# BeagleBone_Blue_3D.net
KiCad netlist of a schematic drawn in EAGLE
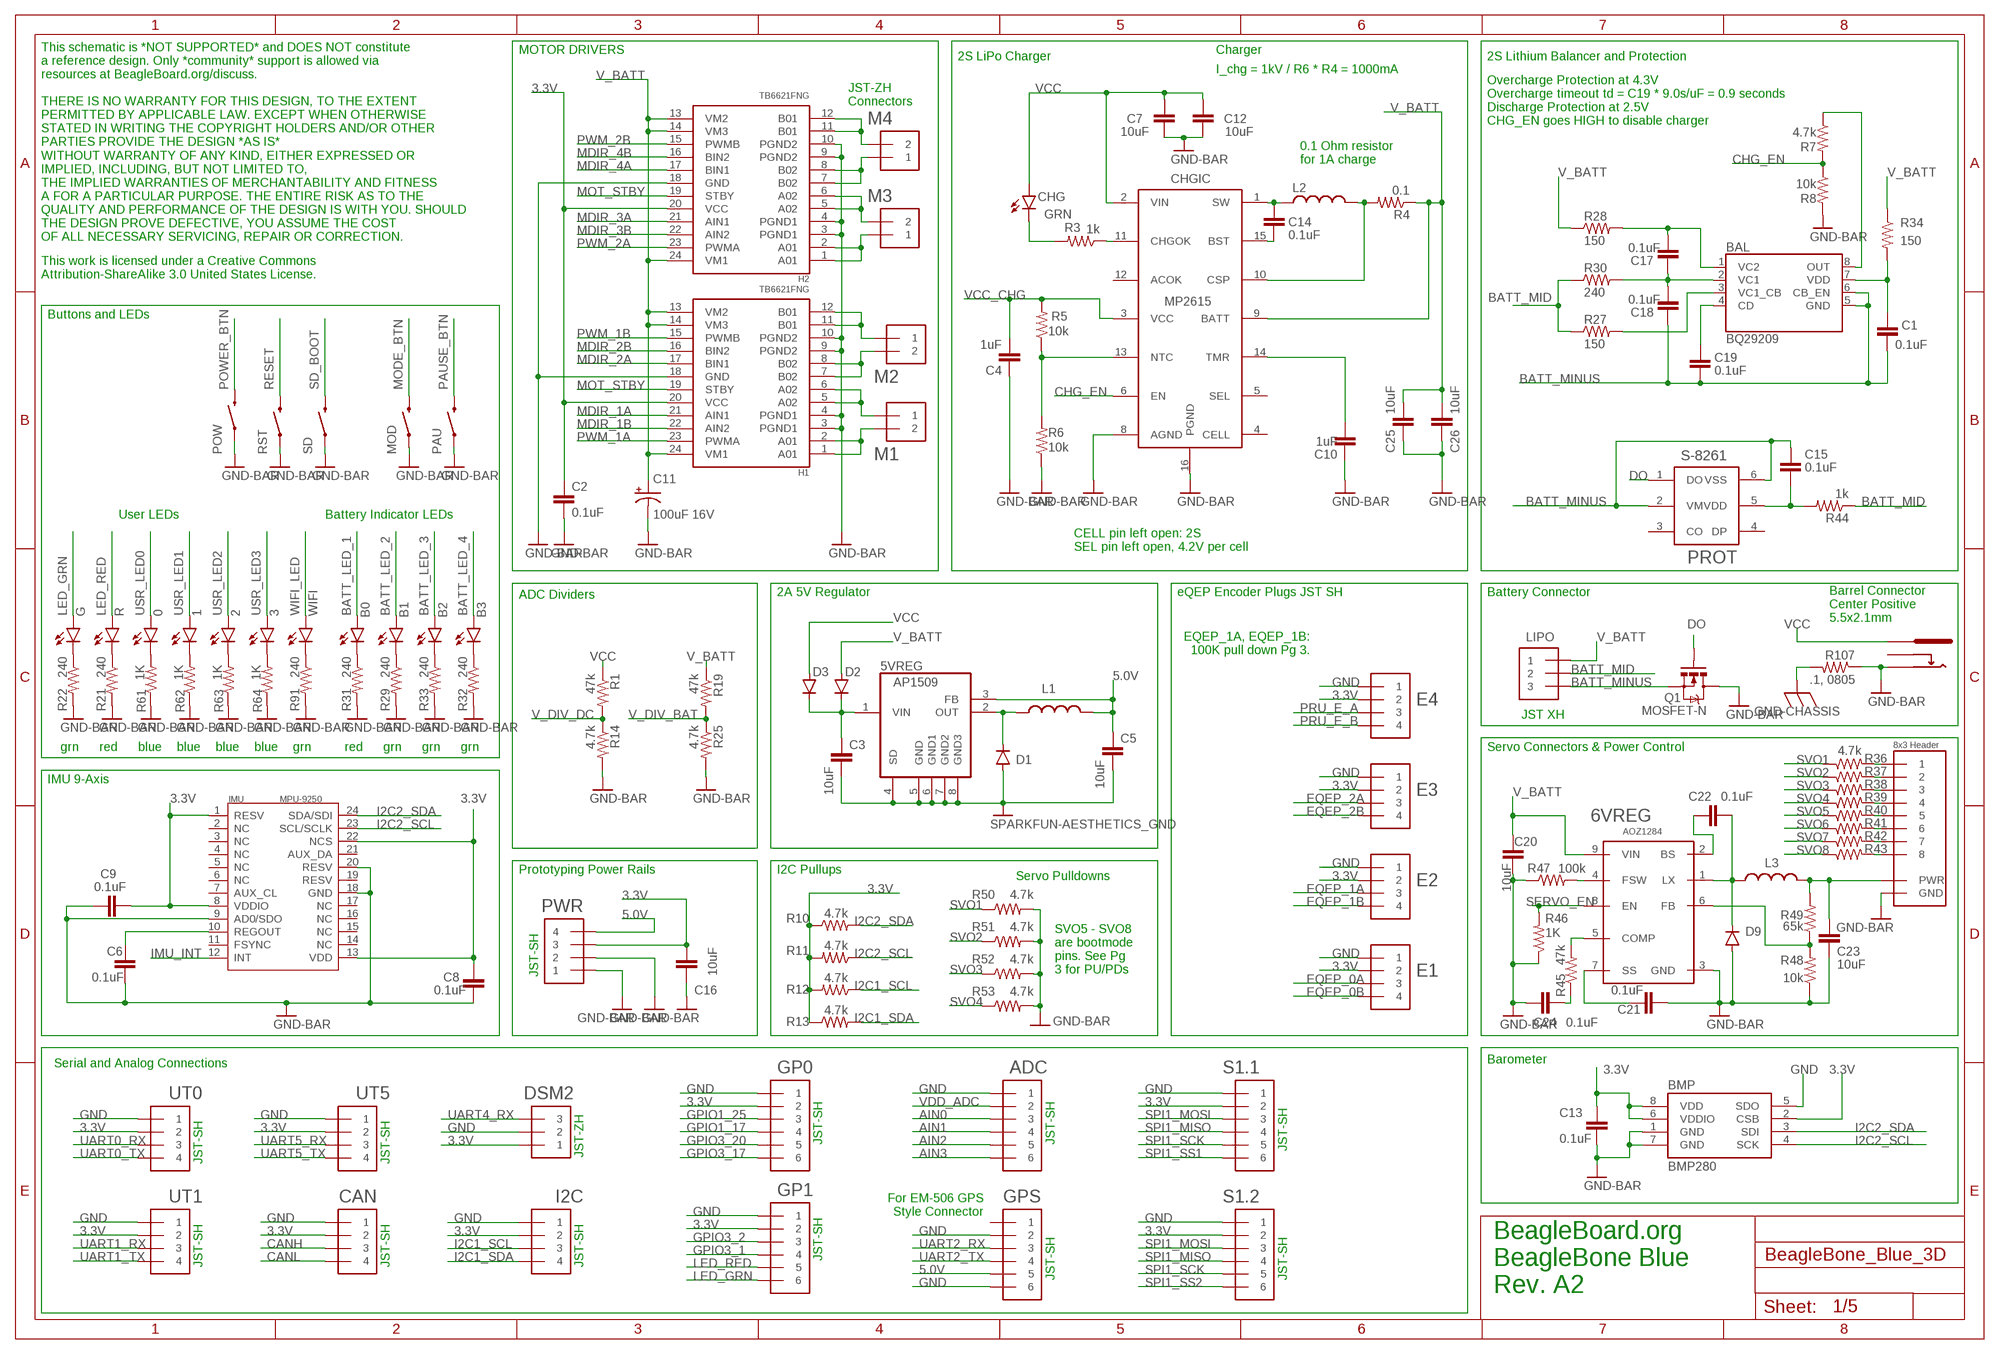
[diagram p0: schematic, sheet 1]
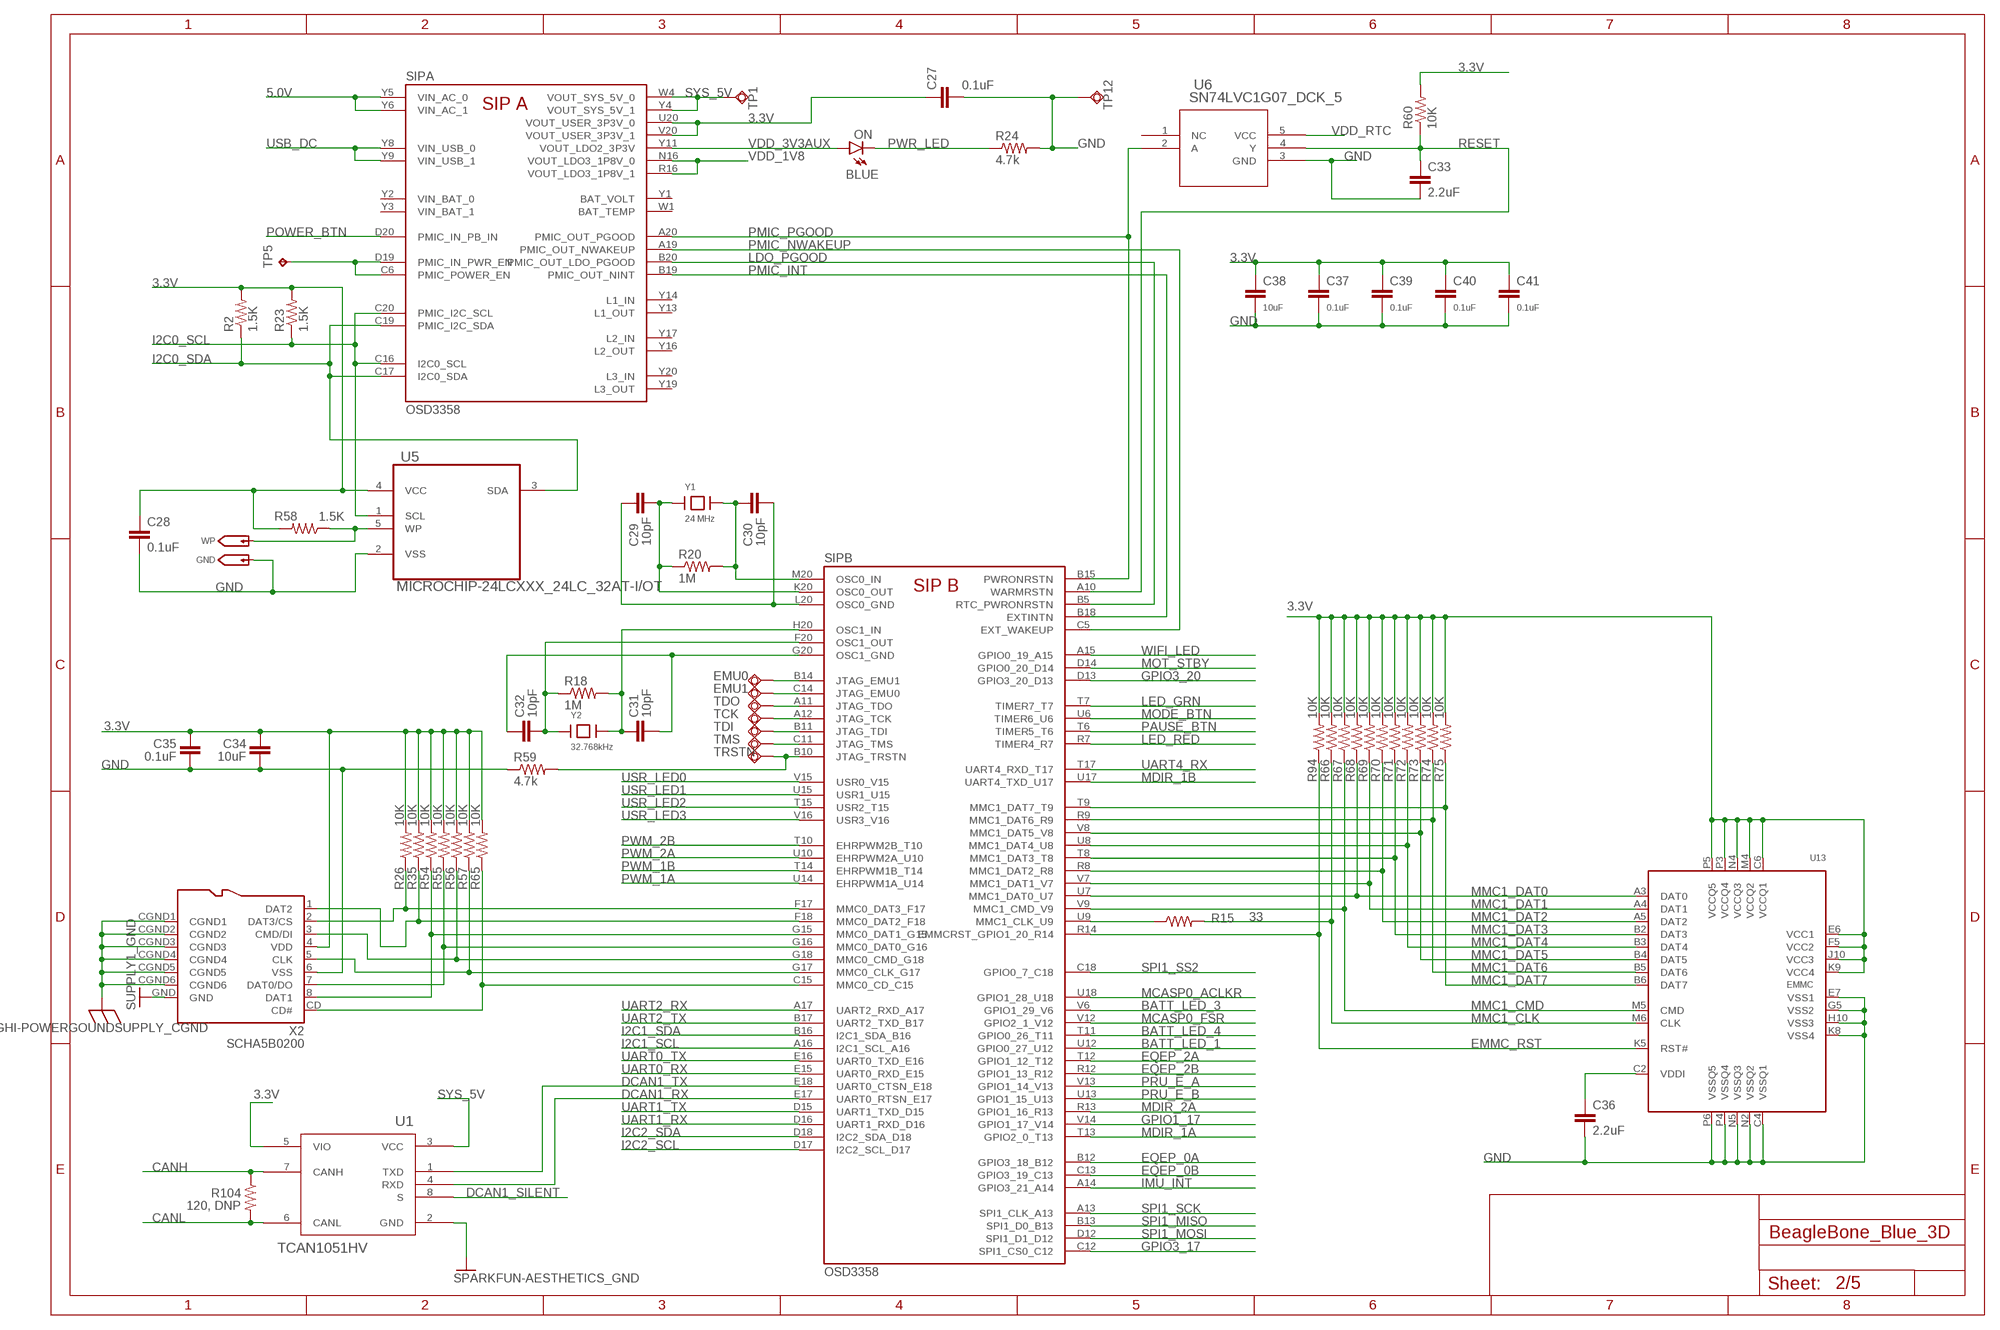
[diagram p1: schematic, sheet 2]
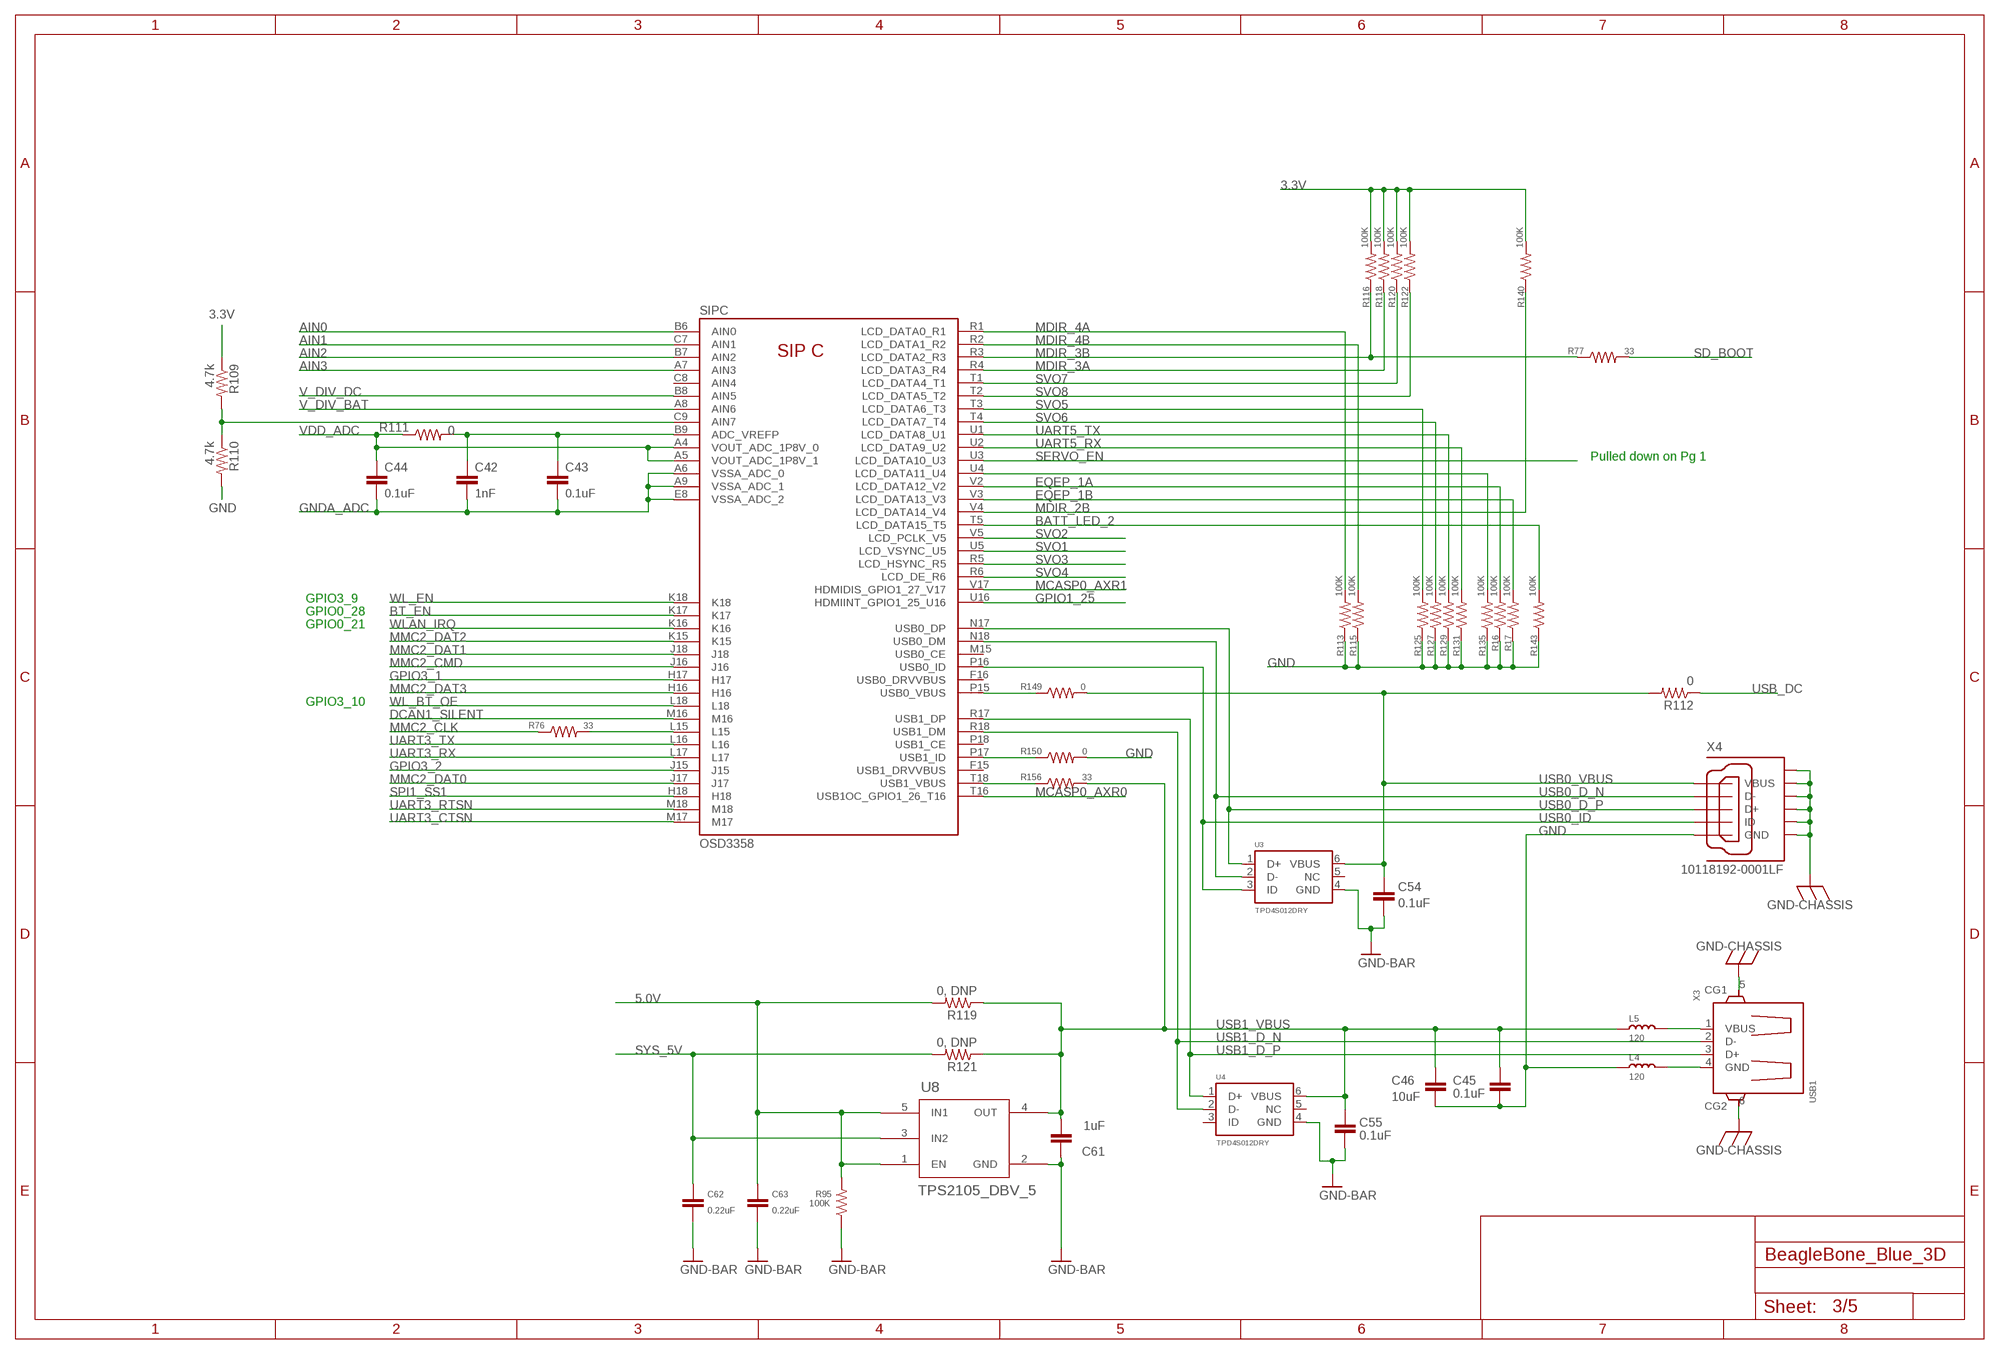
[diagram p2: schematic, sheet 3]
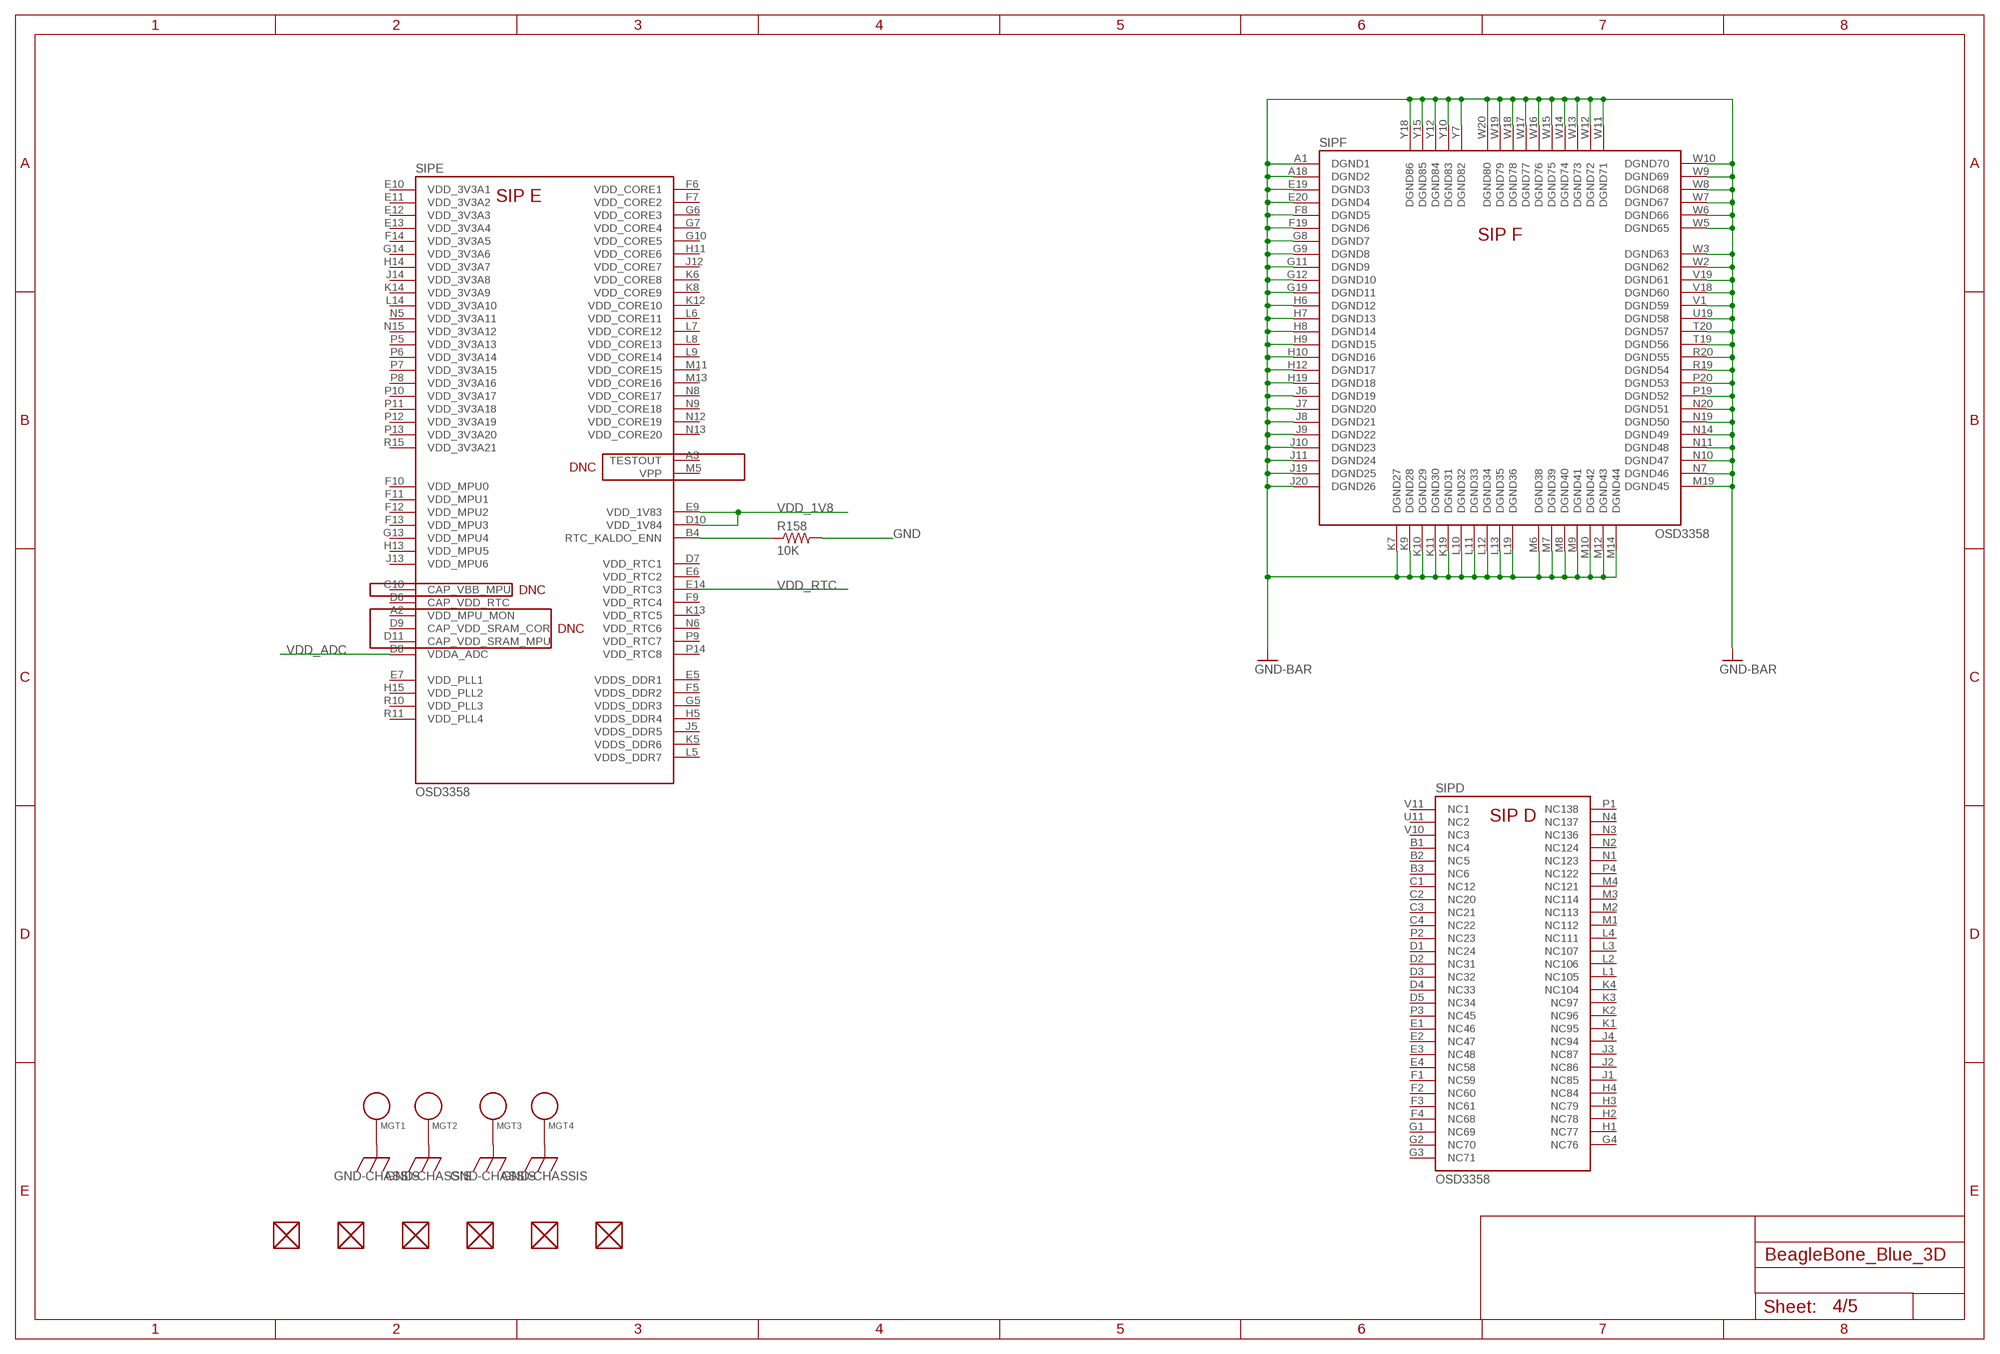
[diagram p3: schematic, sheet 4]
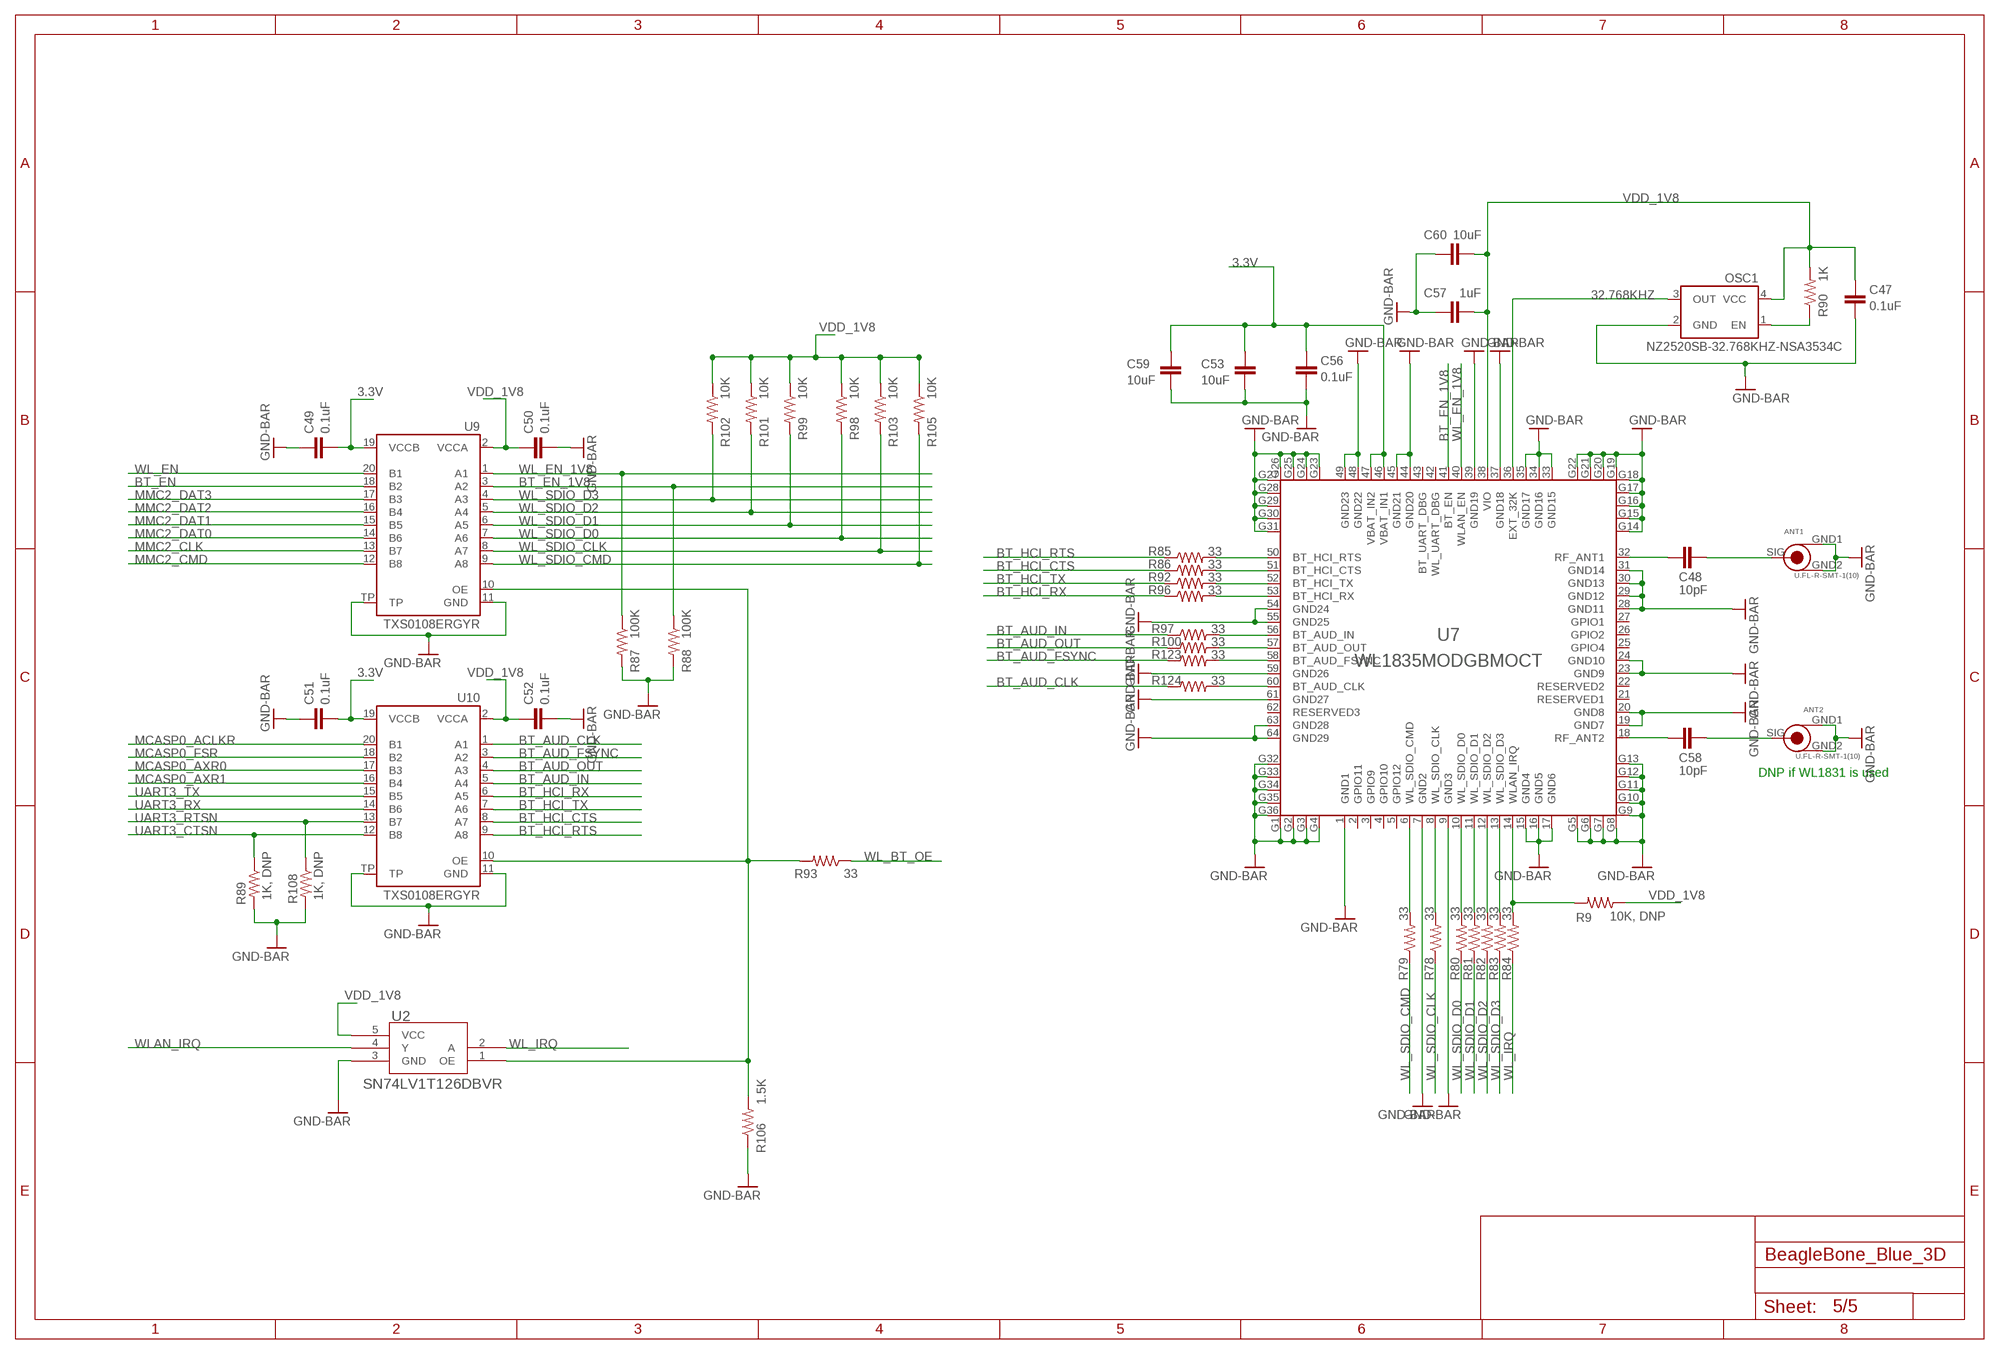
[diagram p4: schematic, sheet 5]

(export (version "E")
  (design (tool "Eeschema 10.0.6"))
  (components
    (comp (ref "ANT1")
      (value "U.FL-R-SMT-1(10)")
      (footprint "eagle-import:GHI-CONNECTORS_U.FL-R-SMT-1")
      (libsource (lib "eagle-import") (part "U.FL-R-SMT-1"))
    )
    (comp (ref "ANT2")
      (value "U.FL-R-SMT-1(10)")
      (footprint "eagle-import:GHI-CONNECTORS_U.FL-R-SMT-1")
      (libsource (lib "eagle-import") (part "U.FL-R-SMT-1"))
    )
    (comp (ref "C47")
      (value "0.1uF")
      (footprint "eagle-import:0402-CAP")
      (libsource (lib "eagle-import") (part "CAPACITOR-N0402"))
    )
    (comp (ref "C48")
      (value "10pF")
      (footprint "eagle-import:0402-CAP")
      (libsource (lib "eagle-import") (part "CAPACITOR-N0402"))
    )
    (comp (ref "C49")
      (value "0.1uF")
      (footprint "eagle-import:0402-CAP")
      (libsource (lib "eagle-import") (part "CAPACITOR-N0402"))
    )
    (comp (ref "C50")
      (value "0.1uF")
      (footprint "eagle-import:0402-CAP")
      (libsource (lib "eagle-import") (part "CAPACITOR-N0402"))
    )
    (comp (ref "C51")
      (value "0.1uF")
      (footprint "eagle-import:0402-CAP")
      (libsource (lib "eagle-import") (part "CAPACITOR-N0402"))
    )
    (comp (ref "C52")
      (value "0.1uF")
      (footprint "eagle-import:0402-CAP")
      (libsource (lib "eagle-import") (part "CAPACITOR-N0402"))
    )
    (comp (ref "C53")
      (value "10uF")
      (footprint "eagle-import:0805")
      (libsource (lib "eagle-import") (part "CAPACITOR-N0805"))
    )
    (comp (ref "C56")
      (value "0.1uF")
      (footprint "eagle-import:0402-CAP")
      (libsource (lib "eagle-import") (part "CAPACITOR-N0402"))
    )
    (comp (ref "C57")
      (value "1uF")
      (footprint "eagle-import:0402-CAP")
      (libsource (lib "eagle-import") (part "CAPACITOR-N0402"))
    )
    (comp (ref "C58")
      (value "10pF")
      (footprint "eagle-import:0402-CAP")
      (libsource (lib "eagle-import") (part "CAPACITOR-N0402"))
    )
    (comp (ref "C59")
      (value "10uF")
      (footprint "eagle-import:0805")
      (libsource (lib "eagle-import") (part "CAPACITOR-N0805"))
    )
    (comp (ref "C60")
      (value "10uF")
      (footprint "eagle-import:0805")
      (libsource (lib "eagle-import") (part "CAPACITOR-N0805"))
    )
    (comp (ref "OSC1")
      (value "NZ2520SB-32.768KHZ-NSA3534C")
      (footprint "eagle-import:NZ2520S")
      (libsource (lib "eagle-import") (part "OSCILLATOR"))
    )
    (comp (ref "R9")
      (value "10K, DNP")
      (footprint "eagle-import:0402-RES")
      (libsource (lib "eagle-import") (part "RESISTOR0402"))
    )
    (comp (ref "R78")
      (value "33")
      (footprint "eagle-import:0402-RES")
      (libsource (lib "eagle-import") (part "RESISTOR0402"))
    )
    (comp (ref "R79")
      (value "33")
      (footprint "eagle-import:0402-RES")
      (libsource (lib "eagle-import") (part "RESISTOR0402"))
    )
    (comp (ref "R80")
      (value "33")
      (footprint "eagle-import:0402-RES")
      (libsource (lib "eagle-import") (part "RESISTOR0402"))
    )
    (comp (ref "R81")
      (value "33")
      (footprint "eagle-import:0402-RES")
      (libsource (lib "eagle-import") (part "RESISTOR0402"))
    )
    (comp (ref "R82")
      (value "33")
      (footprint "eagle-import:0402-RES")
      (libsource (lib "eagle-import") (part "RESISTOR0402"))
    )
    (comp (ref "R83")
      (value "33")
      (footprint "eagle-import:0402-RES")
      (libsource (lib "eagle-import") (part "RESISTOR0402"))
    )
    (comp (ref "R84")
      (value "33")
      (footprint "eagle-import:0402-RES")
      (libsource (lib "eagle-import") (part "RESISTOR0402"))
    )
    (comp (ref "R85")
      (value "33")
      (footprint "eagle-import:0402-RES")
      (libsource (lib "eagle-import") (part "RESISTOR0402"))
    )
    (comp (ref "R86")
      (value "33")
      (footprint "eagle-import:0402-RES")
      (libsource (lib "eagle-import") (part "RESISTOR0402"))
    )
    (comp (ref "R87")
      (value "100K")
      (footprint "eagle-import:0402-RES")
      (libsource (lib "eagle-import") (part "RESISTOR0402"))
    )
    (comp (ref "R88")
      (value "100K")
      (footprint "eagle-import:0402-RES")
      (libsource (lib "eagle-import") (part "RESISTOR0402"))
    )
    (comp (ref "R89")
      (value "1K, DNP")
      (footprint "eagle-import:0402-RES")
      (libsource (lib "eagle-import") (part "RESISTOR0402"))
    )
    (comp (ref "R90")
      (value "1K")
      (footprint "eagle-import:0402-RES")
      (libsource (lib "eagle-import") (part "RESISTOR0402"))
    )
    (comp (ref "R92")
      (value "33")
      (footprint "eagle-import:0402-RES")
      (libsource (lib "eagle-import") (part "RESISTOR0402"))
    )
    (comp (ref "R93")
      (value "33")
      (footprint "eagle-import:0402-RES")
      (libsource (lib "eagle-import") (part "RESISTOR0402"))
    )
    (comp (ref "R96")
      (value "33")
      (footprint "eagle-import:0402-RES")
      (libsource (lib "eagle-import") (part "RESISTOR0402"))
    )
    (comp (ref "R97")
      (value "33")
      (footprint "eagle-import:0402-RES")
      (libsource (lib "eagle-import") (part "RESISTOR0402"))
    )
    (comp (ref "R98")
      (value "10K")
      (footprint "eagle-import:0402-RES")
      (libsource (lib "eagle-import") (part "RESISTOR0402"))
    )
    (comp (ref "R99")
      (value "10K")
      (footprint "eagle-import:0402-RES")
      (libsource (lib "eagle-import") (part "RESISTOR0402"))
    )
    (comp (ref "R100")
      (value "33")
      (footprint "eagle-import:0402-RES")
      (libsource (lib "eagle-import") (part "RESISTOR0402"))
    )
    (comp (ref "R101")
      (value "10K")
      (footprint "eagle-import:0402-RES")
      (libsource (lib "eagle-import") (part "RESISTOR0402"))
    )
    (comp (ref "R102")
      (value "10K")
      (footprint "eagle-import:0402-RES")
      (libsource (lib "eagle-import") (part "RESISTOR0402"))
    )
    (comp (ref "R103")
      (value "10K")
      (footprint "eagle-import:0402-RES")
      (libsource (lib "eagle-import") (part "RESISTOR0402"))
    )
    (comp (ref "R105")
      (value "10K")
      (footprint "eagle-import:0402-RES")
      (libsource (lib "eagle-import") (part "RESISTOR0402"))
    )
    (comp (ref "R106")
      (value "1.5K")
      (footprint "eagle-import:0402-RES")
      (libsource (lib "eagle-import") (part "RESISTOR0402"))
    )
    (comp (ref "R108")
      (value "1K, DNP")
      (footprint "eagle-import:0402-RES")
      (libsource (lib "eagle-import") (part "RESISTOR0402"))
    )
    (comp (ref "R123")
      (value "33")
      (footprint "eagle-import:0402-RES")
      (libsource (lib "eagle-import") (part "RESISTOR0402"))
    )
    (comp (ref "R124")
      (value "33")
      (footprint "eagle-import:0402-RES")
      (libsource (lib "eagle-import") (part "RESISTOR0402"))
    )
    (comp (ref "U2")
      (value "SN74LV1T126DBVR")
      (footprint "eagle-import:SOT95P280X145-5")
      (libsource (lib "eagle-import") (part "SN74LV1T126DBVR"))
    )
    (comp (ref "U7")
      (value "WL1835MODGBMOCT")
      (footprint "eagle-import:MOC-100(TI)")
      (libsource (lib "eagle-import") (part "WL1835MOD"))
    )
    (comp (ref "U9")
      (value "TXS0108ERGYR")
      (footprint "eagle-import:R-PVQFN-N20(TI)")
      (libsource (lib "eagle-import") (part "TXS0108ERGYR"))
    )
    (comp (ref "U10")
      (value "TXS0108ERGYR")
      (footprint "eagle-import:R-PVQFN-N20(TI)")
      (libsource (lib "eagle-import") (part "TXS0108ERGYR"))
    )
    (comp (ref "FUD1")
      (value "FIDUCIAL")
      (footprint "eagle-import:GHI_FIDUCIAL_40MIL")
      (libsource (lib "eagle-import") (part "FIDUCIAL"))
    )
    (comp (ref "FUD2")
      (value "FIDUCIAL")
      (footprint "eagle-import:GHI_FIDUCIAL_40MIL")
      (libsource (lib "eagle-import") (part "FIDUCIAL"))
    )
    (comp (ref "FUD3")
      (value "FIDUCIAL")
      (footprint "eagle-import:GHI_FIDUCIAL_40MIL")
      (libsource (lib "eagle-import") (part "FIDUCIAL"))
    )
    (comp (ref "FUD4")
      (value "FIDUCIAL")
      (footprint "eagle-import:GHI_FIDUCIAL_40MIL")
      (libsource (lib "eagle-import") (part "FIDUCIAL"))
    )
    (comp (ref "FUD5")
      (value "FIDUCIAL")
      (footprint "eagle-import:GHI_FIDUCIAL_40MIL")
      (libsource (lib "eagle-import") (part "FIDUCIAL"))
    )
    (comp (ref "FUD6")
      (value "FIDUCIAL")
      (footprint "eagle-import:GHI_FIDUCIAL_40MIL")
      (libsource (lib "eagle-import") (part "FIDUCIAL"))
    )
    (comp (ref "MGT1")
      (value "MOUNTING_HOLE")
      (footprint "eagle-import:BEAGLEBONEBLACK_MOUNTING_HOLE")
      (libsource (lib "eagle-import") (part "MOUNTING_HOLE"))
    )
    (comp (ref "MGT2")
      (value "MOUNTING_HOLE")
      (footprint "eagle-import:BEAGLEBONEBLACK_MOUNTING_HOLE")
      (libsource (lib "eagle-import") (part "MOUNTING_HOLE"))
    )
    (comp (ref "MGT3")
      (value "MOUNTING_HOLE")
      (footprint "eagle-import:BEAGLEBONEBLACK_MOUNTING_HOLE")
      (libsource (lib "eagle-import") (part "MOUNTING_HOLE"))
    )
    (comp (ref "MGT4")
      (value "MOUNTING_HOLE")
      (footprint "eagle-import:BEAGLEBONEBLACK_MOUNTING_HOLE")
      (libsource (lib "eagle-import") (part "MOUNTING_HOLE"))
    )
    (comp (ref "R158")
      (value "10K")
      (footprint "eagle-import:0402-RES")
      (libsource (lib "eagle-import") (part "RESISTOR0402"))
    )
    (comp (ref "SIP")
      (value "OSD3358")
      (footprint "eagle-import:OSD3358")
      (libsource (lib "eagle-import") (part "OSD3358"))
    )
    (comp (ref "0")
      (value "BLUE")
      (footprint "eagle-import:0603-BLUE")
      (libsource (lib "eagle-import") (part "LED-BLUE0603"))
    )
    (comp (ref "1")
      (value "BLUE")
      (footprint "eagle-import:0603-BLUE")
      (libsource (lib "eagle-import") (part "LED-BLUE0603"))
    )
    (comp (ref "2")
      (value "BLUE")
      (footprint "eagle-import:0603-BLUE")
      (libsource (lib "eagle-import") (part "LED-BLUE0603"))
    )
    (comp (ref "3")
      (value "BLUE")
      (footprint "eagle-import:0603-BLUE")
      (libsource (lib "eagle-import") (part "LED-BLUE0603"))
    )
    (comp (ref "5VREG")
      (value "AP1509SOIC-8-TIGHT")
      (footprint "eagle-import:SO08-H")
      (libsource (lib "eagle-import") (part "AP1509SOIC-8-TIGHT"))
    )
    (comp (ref "6VREG")
      (value "AOZ1284")
      (footprint "eagle-import:SO08-EXPOSED")
      (libsource (lib "eagle-import") (part "AOZ1284"))
    )
    (comp (ref "12V")
      (value "PJ-102B_POWER_CON")
      (footprint "eagle-import:GHI_PJ-102B_POWER_CON")
      (libsource (lib "eagle-import") (part "PJ-102B_POWER_CON"))
    )
    (comp (ref "ADC")
      (value "JST_SH_6")
      (footprint "eagle-import:JST_SH_6")
      (libsource (lib "eagle-import") (part "JST_SH_6"))
    )
    (comp (ref "B0")
      (value "RED")
      (footprint "eagle-import:LED-0603")
      (libsource (lib "eagle-import") (part "BLUE_LED0603"))
    )
    (comp (ref "B1")
      (value "GREEN")
      (footprint "eagle-import:LED-0603")
      (libsource (lib "eagle-import") (part "BLUE_LED0603"))
    )
    (comp (ref "B2")
      (value "GREEN")
      (footprint "eagle-import:LED-0603")
      (libsource (lib "eagle-import") (part "BLUE_LED0603"))
    )
    (comp (ref "B3")
      (value "GREEN")
      (footprint "eagle-import:LED-0603")
      (libsource (lib "eagle-import") (part "BLUE_LED0603"))
    )
    (comp (ref "BAL")
      (value "BQ29209")
      (footprint "eagle-import:8-SON_3X3MM")
      (libsource (lib "eagle-import") (part "BQ29209"))
    )
    (comp (ref "BMP")
      (value "BMP280")
      (footprint "eagle-import:BMP280")
      (libsource (lib "eagle-import") (part "BMP280"))
    )
    (comp (ref "C1")
      (value "0.1uF")
      (footprint "eagle-import:0402-CAP")
      (libsource (lib "eagle-import") (part "CAPACITOR-N0402"))
    )
    (comp (ref "C2")
      (value "0.1uF")
      (footprint "eagle-import:0402-CAP")
      (libsource (lib "eagle-import") (part "CAPACITOR-N0402"))
    )
    (comp (ref "C3")
      (value "10uF")
      (footprint "eagle-import:0805")
      (libsource (lib "eagle-import") (part "CAPACITOR-N0805"))
    )
    (comp (ref "C4")
      (value "1uF")
      (footprint "eagle-import:0402-CAP")
      (libsource (lib "eagle-import") (part "CAPACITOR-N0402"))
    )
    (comp (ref "C5")
      (value "10uF")
      (footprint "eagle-import:0805")
      (libsource (lib "eagle-import") (part "CAPACITOR-N0805"))
    )
    (comp (ref "C6")
      (value "0.1uF")
      (footprint "eagle-import:0402-CAP")
      (libsource (lib "eagle-import") (part "CAPACITOR-N0402"))
    )
    (comp (ref "C7")
      (value "10uF")
      (footprint "eagle-import:0805")
      (libsource (lib "eagle-import") (part "CAPACITOR-N0805"))
    )
    (comp (ref "C8")
      (value "0.1uF")
      (footprint "eagle-import:0402-CAP")
      (libsource (lib "eagle-import") (part "CAPACITOR-N0402"))
    )
    (comp (ref "C9")
      (value "0.1uF")
      (footprint "eagle-import:0402-CAP")
      (libsource (lib "eagle-import") (part "CAPACITOR-N0402"))
    )
    (comp (ref "C10")
      (value "1uF")
      (footprint "eagle-import:0402-CAP")
      (libsource (lib "eagle-import") (part "CAPACITOR-N0402"))
    )
    (comp (ref "C11")
      (value "100uF 16V")
      (footprint "eagle-import:PANASONIC_D")
      (libsource (lib "eagle-import") (part "CAPACITOR-PD"))
    )
    (comp (ref "C12")
      (value "10uF")
      (footprint "eagle-import:0805")
      (libsource (lib "eagle-import") (part "CAPACITOR-N0805"))
    )
    (comp (ref "C13")
      (value "0.1uF")
      (footprint "eagle-import:0402-CAP")
      (libsource (lib "eagle-import") (part "CAPACITOR-N0402"))
    )
    (comp (ref "C14")
      (value "0.1uF")
      (footprint "eagle-import:0402-CAP")
      (libsource (lib "eagle-import") (part "CAPACITOR-N0402"))
    )
    (comp (ref "C15")
      (value "0.1uF")
      (footprint "eagle-import:0402-CAP")
      (libsource (lib "eagle-import") (part "CAPACITOR-N0402"))
    )
    (comp (ref "C16")
      (value "10uF")
      (footprint "eagle-import:0805")
      (libsource (lib "eagle-import") (part "CAPACITOR-N0805"))
    )
    (comp (ref "C17")
      (value "0.1uF")
      (footprint "eagle-import:0402-CAP")
      (libsource (lib "eagle-import") (part "CAPACITOR-N0402"))
    )
    (comp (ref "C18")
      (value "0.1uF")
      (footprint "eagle-import:0402-CAP")
      (libsource (lib "eagle-import") (part "CAPACITOR-N0402"))
    )
    (comp (ref "C19")
      (value "0.1uF")
      (footprint "eagle-import:0402-CAP")
      (libsource (lib "eagle-import") (part "CAPACITOR-N0402"))
    )
    (comp (ref "C20")
      (value "10uF")
      (footprint "eagle-import:0805")
      (libsource (lib "eagle-import") (part "CAPACITOR-N0805"))
    )
    (comp (ref "C21")
      (value "0.1uF")
      (footprint "eagle-import:0402-CAP")
      (libsource (lib "eagle-import") (part "CAPACITOR-N0402"))
    )
    (comp (ref "C22")
      (value "0.1uF")
      (footprint "eagle-import:0402-CAP")
      (libsource (lib "eagle-import") (part "CAPACITOR-N0402"))
    )
    (comp (ref "C23")
      (value "10uF")
      (footprint "eagle-import:0805")
      (libsource (lib "eagle-import") (part "CAPACITOR-N0805"))
    )
    (comp (ref "C24")
      (value "0.1uF")
      (footprint "eagle-import:0402-CAP")
      (libsource (lib "eagle-import") (part "CAPACITOR-N0402"))
    )
    (comp (ref "C25")
      (value "10uF")
      (footprint "eagle-import:0805")
      (libsource (lib "eagle-import") (part "CAPACITOR-N0805"))
    )
    (comp (ref "C26")
      (value "10uF")
      (footprint "eagle-import:0805")
      (libsource (lib "eagle-import") (part "CAPACITOR-N0805"))
    )
    (comp (ref "CAN")
      (value "JST_SH_4")
      (footprint "eagle-import:JST_SH_4_SMD")
      (libsource (lib "eagle-import") (part "JST_SH_4"))
    )
    (comp (ref "CHG")
      (value "GRN")
      (footprint "eagle-import:LED-0603")
      (libsource (lib "eagle-import") (part "BLUE_LED0603"))
    )
    (comp (ref "CHGIC")
      (value "MP2615")
      (footprint "eagle-import:QFN50P300X300X100-16")
      (libsource (lib "eagle-import") (part "MP2615"))
    )
    (comp (ref "D1")
      (value "DIODEDIODE-123FL")
      (footprint "eagle-import:DIODE_SOD-123FL")
      (libsource (lib "eagle-import") (part "DIODEDIODE-123FL"))
    )
    (comp (ref "D2")
      (value "DIODEDIODE-123FL")
      (footprint "eagle-import:DIODE_SOD-123FL")
      (libsource (lib "eagle-import") (part "DIODEDIODE-123FL"))
    )
    (comp (ref "D3")
      (value "DIODEDIODE-123FL")
      (footprint "eagle-import:DIODE_SOD-123FL")
      (libsource (lib "eagle-import") (part "DIODEDIODE-123FL"))
    )
    (comp (ref "D9")
      (value "DIODEDO214AA")
      (footprint "eagle-import:DO-214AA")
      (libsource (lib "eagle-import") (part "DIODEDO214AA"))
    )
    (comp (ref "DSM2")
      (value "JST_ZH_3")
      (footprint "eagle-import:JST_ZH_3")
      (libsource (lib "eagle-import") (part "JST_ZH_3"))
    )
    (comp (ref "E1")
      (value "JST_SH_4")
      (footprint "eagle-import:JST_SH_4_SMD")
      (libsource (lib "eagle-import") (part "JST_SH_4"))
    )
    (comp (ref "E2")
      (value "JST_SH_4")
      (footprint "eagle-import:JST_SH_4_SMD")
      (libsource (lib "eagle-import") (part "JST_SH_4"))
    )
    (comp (ref "E3")
      (value "JST_SH_4")
      (footprint "eagle-import:JST_SH_4_SMD")
      (libsource (lib "eagle-import") (part "JST_SH_4"))
    )
    (comp (ref "E4")
      (value "JST_SH_4")
      (footprint "eagle-import:JST_SH_4_SMD")
      (libsource (lib "eagle-import") (part "JST_SH_4"))
    )
    (comp (ref "G")
      (value "GREEN")
      (footprint "eagle-import:0603-GREEN")
      (libsource (lib "eagle-import") (part "LED-GREEN0603"))
    )
    (comp (ref "GP0")
      (value "JST_SH_6")
      (footprint "eagle-import:JST_SH_6")
      (libsource (lib "eagle-import") (part "JST_SH_6"))
    )
    (comp (ref "GP1")
      (value "JST_SH_6")
      (footprint "eagle-import:JST_SH_6")
      (libsource (lib "eagle-import") (part "JST_SH_6"))
    )
    (comp (ref "GPS")
      (value "JST_SH_6")
      (footprint "eagle-import:JST_SH_6")
      (libsource (lib "eagle-import") (part "JST_SH_6"))
    )
    (comp (ref "H1")
      (value "TB6621FNG")
      (footprint "eagle-import:SOP65P760X140-24")
      (libsource (lib "eagle-import") (part "TB6621FNG"))
    )
    (comp (ref "H2")
      (value "TB6621FNG")
      (footprint "eagle-import:SOP65P760X140-24")
      (libsource (lib "eagle-import") (part "TB6621FNG"))
    )
    (comp (ref "I2C")
      (value "JST_SH_4")
      (footprint "eagle-import:JST_SH_4_SMD")
      (libsource (lib "eagle-import") (part "JST_SH_4"))
    )
    (comp (ref "IMU")
      (value "MPU-9250")
      (footprint "eagle-import:QFN24G-0.4-3X3MM")
      (libsource (lib "eagle-import") (part "MPU-9250"))
    )
    (comp (ref "J2")
      (value "SERVO_HEADERS_8X")
      (footprint "eagle-import:DIODE_3X8_0.1__HEADER")
      (libsource (lib "eagle-import") (part "SERVO_HEADERS_8X"))
    )
    (comp (ref "L1")
      (value "6.8uH")
      (footprint "eagle-import:SRN6045")
      (libsource (lib "eagle-import") (part "INDUCTORSRN6045"))
    )
    (comp (ref "L2")
      (value "6.8uH")
      (footprint "eagle-import:SRN6045")
      (libsource (lib "eagle-import") (part "INDUCTORSRN6045"))
    )
    (comp (ref "L3")
      (value "3.6 uH")
      (footprint "eagle-import:INDUCTOR-8X8MM")
      (libsource (lib "eagle-import") (part "INDUCTOR8X8MM"))
    )
    (comp (ref "LIPO")
      (value "BATTERY")
      (footprint "eagle-import:JST_XH_3-PIN")
      (libsource (lib "eagle-import") (part "JST_XH_3-PIN"))
    )
    (comp (ref "M1")
      (value "JST_ZH_2")
      (footprint "eagle-import:JST_ZH_2")
      (libsource (lib "eagle-import") (part "JST_ZH_2"))
    )
    (comp (ref "M2")
      (value "JST_ZH_2")
      (footprint "eagle-import:JST_ZH_2")
      (libsource (lib "eagle-import") (part "JST_ZH_2"))
    )
    (comp (ref "M3")
      (value "JST_ZH_2")
      (footprint "eagle-import:JST_ZH_2")
      (libsource (lib "eagle-import") (part "JST_ZH_2"))
    )
    (comp (ref "M4")
      (value "JST_ZH_2")
      (footprint "eagle-import:JST_ZH_2")
      (libsource (lib "eagle-import") (part "JST_ZH_2"))
    )
    (comp (ref "MOD")
      (value "RS032G05A3SM-SPST-MOMENTARY-SWSMD-1101NE")
      (footprint "eagle-import:TACTILE-SWITCH-1101NE")
      (libsource (lib "eagle-import") (part "RS032G05A3SM-SPST-MOMENTARY-SWSMD-1101NE"))
    )
    (comp (ref "PAU")
      (value "RS032G05A3SM-SPST-MOMENTARY-SWSMD-1101NE")
      (footprint "eagle-import:TACTILE-SWITCH-1101NE")
      (libsource (lib "eagle-import") (part "RS032G05A3SM-SPST-MOMENTARY-SWSMD-1101NE"))
    )
    (comp (ref "POW")
      (value "RS032G05A3SM-SPST-MOMENTARY-SWSMD-1101NE")
      (footprint "eagle-import:TACTILE-SWITCH-1101NE")
      (libsource (lib "eagle-import") (part "RS032G05A3SM-SPST-MOMENTARY-SWSMD-1101NE"))
    )
    (comp (ref "PROT")
      (value "S-8261")
      (footprint "eagle-import:SOT-236")
      (libsource (lib "eagle-import") (part "S-8261"))
    )
    (comp (ref "PWR")
      (value "JST_SH_4")
      (footprint "eagle-import:JST_SH_4_SMD")
      (libsource (lib "eagle-import") (part "JST_SH_4"))
    )
    (comp (ref "Q1")
      (value "MOSFET-N")
      (footprint "eagle-import:SO08-TIGHT")
      (libsource (lib "eagle-import") (part "MOSFET-NCHANNEL"))
    )
    (comp (ref "R")
      (value "RED")
      (footprint "eagle-import:0603-RED")
      (libsource (lib "eagle-import") (part "LED-RED0603"))
    )
    (comp (ref "R1")
      (value "47k")
      (footprint "eagle-import:0402-RES")
      (libsource (lib "eagle-import") (part "RESISTOR0402"))
    )
    (comp (ref "R3")
      (value "1k")
      (footprint "eagle-import:0402-RES")
      (libsource (lib "eagle-import") (part "RESISTOR0402"))
    )
    (comp (ref "R4")
      (value "0.1")
      (footprint "eagle-import:0402-RES")
      (libsource (lib "eagle-import") (part "RESISTOR0402"))
    )
    (comp (ref "R5")
      (value "10k")
      (footprint "eagle-import:0402-RES")
      (libsource (lib "eagle-import") (part "RESISTOR0402"))
    )
    (comp (ref "R6")
      (value "10k")
      (footprint "eagle-import:0402-RES")
      (libsource (lib "eagle-import") (part "RESISTOR0402"))
    )
    (comp (ref "R7")
      (value "4.7k")
      (footprint "eagle-import:0402-RES")
      (libsource (lib "eagle-import") (part "RESISTOR0402"))
    )
    (comp (ref "R8")
      (value "10k")
      (footprint "eagle-import:0402-RES")
      (libsource (lib "eagle-import") (part "RESISTOR0402"))
    )
    (comp (ref "R10")
      (value "4.7k")
      (footprint "eagle-import:0402-RES")
      (libsource (lib "eagle-import") (part "RESISTOR0402"))
    )
    (comp (ref "R11")
      (value "4.7k")
      (footprint "eagle-import:0402-RES")
      (libsource (lib "eagle-import") (part "RESISTOR0402"))
    )
    (comp (ref "R12")
      (value "4.7k")
      (footprint "eagle-import:0402-RES")
      (libsource (lib "eagle-import") (part "RESISTOR0402"))
    )
    (comp (ref "R13")
      (value "4.7k")
      (footprint "eagle-import:0402-RES")
      (libsource (lib "eagle-import") (part "RESISTOR0402"))
    )
    (comp (ref "R14")
      (value "4.7k")
      (footprint "eagle-import:0402-RES")
      (libsource (lib "eagle-import") (part "RESISTOR0402"))
    )
    (comp (ref "R19")
      (value "47k")
      (footprint "eagle-import:0402-RES")
      (libsource (lib "eagle-import") (part "RESISTOR0402"))
    )
    (comp (ref "R21")
      (value "240")
      (footprint "eagle-import:0402-RES")
      (libsource (lib "eagle-import") (part "RESISTOR0402"))
    )
    (comp (ref "R22")
      (value "240")
      (footprint "eagle-import:0402-RES")
      (libsource (lib "eagle-import") (part "RESISTOR0402"))
    )
    (comp (ref "R25")
      (value "4.7k")
      (footprint "eagle-import:0402-RES")
      (libsource (lib "eagle-import") (part "RESISTOR0402"))
    )
    (comp (ref "R27")
      (value "150")
      (footprint "eagle-import:0402-RES")
      (libsource (lib "eagle-import") (part "RESISTOR0402"))
    )
    (comp (ref "R28")
      (value "150")
      (footprint "eagle-import:0402-RES")
      (libsource (lib "eagle-import") (part "RESISTOR0402"))
    )
    (comp (ref "R29")
      (value "240")
      (footprint "eagle-import:0402-RES")
      (libsource (lib "eagle-import") (part "RESISTOR0402"))
    )
    (comp (ref "R30")
      (value "240")
      (footprint "eagle-import:0402-RES")
      (libsource (lib "eagle-import") (part "RESISTOR0402"))
    )
    (comp (ref "R31")
      (value "240")
      (footprint "eagle-import:0402-RES")
      (libsource (lib "eagle-import") (part "RESISTOR0402"))
    )
    (comp (ref "R32")
      (value "240")
      (footprint "eagle-import:0402-RES")
      (libsource (lib "eagle-import") (part "RESISTOR0402"))
    )
    (comp (ref "R33")
      (value "240")
      (footprint "eagle-import:0402-RES")
      (libsource (lib "eagle-import") (part "RESISTOR0402"))
    )
    (comp (ref "R34")
      (value "150")
      (footprint "eagle-import:0402-RES")
      (libsource (lib "eagle-import") (part "RESISTOR0402"))
    )
    (comp (ref "R36")
      (value "4.7k")
      (footprint "eagle-import:0402-RES")
      (libsource (lib "eagle-import") (part "RESISTOR0402"))
    )
    (comp (ref "R37")
      (value "4.7k")
      (footprint "eagle-import:0402-RES")
      (libsource (lib "eagle-import") (part "RESISTOR0402"))
    )
    (comp (ref "R38")
      (value "4.7k")
      (footprint "eagle-import:0402-RES")
      (libsource (lib "eagle-import") (part "RESISTOR0402"))
    )
    (comp (ref "R39")
      (value "4.7k")
      (footprint "eagle-import:0402-RES")
      (libsource (lib "eagle-import") (part "RESISTOR0402"))
    )
    (comp (ref "R40")
      (value "4.7k")
      (footprint "eagle-import:0402-RES")
      (libsource (lib "eagle-import") (part "RESISTOR0402"))
    )
    (comp (ref "R41")
      (value "4.7k")
      (footprint "eagle-import:0402-RES")
      (libsource (lib "eagle-import") (part "RESISTOR0402"))
    )
    (comp (ref "R42")
      (value "4.7k")
      (footprint "eagle-import:0402-RES")
      (libsource (lib "eagle-import") (part "RESISTOR0402"))
    )
    (comp (ref "R43")
      (value "4.7k")
      (footprint "eagle-import:0402-RES")
      (libsource (lib "eagle-import") (part "RESISTOR0402"))
    )
    (comp (ref "R44")
      (value "1k")
      (footprint "eagle-import:0402-RES")
      (libsource (lib "eagle-import") (part "RESISTOR0402"))
    )
    (comp (ref "R45")
      (value "47k")
      (footprint "eagle-import:0402-RES")
      (libsource (lib "eagle-import") (part "RESISTOR0402"))
    )
    (comp (ref "R46")
      (value "1K")
      (footprint "eagle-import:0402-RES")
      (libsource (lib "eagle-import") (part "RESISTOR0402"))
    )
    (comp (ref "R47")
      (value "100k")
      (footprint "eagle-import:0402-RES")
      (libsource (lib "eagle-import") (part "RESISTOR0402"))
    )
    (comp (ref "R48")
      (value "10k")
      (footprint "eagle-import:0402-RES")
      (libsource (lib "eagle-import") (part "RESISTOR0402"))
    )
    (comp (ref "R49")
      (value "65k")
      (footprint "eagle-import:0402-RES")
      (libsource (lib "eagle-import") (part "RESISTOR0402"))
    )
    (comp (ref "R50")
      (value "4.7k")
      (footprint "eagle-import:0402-RES")
      (libsource (lib "eagle-import") (part "RESISTOR0402"))
    )
    (comp (ref "R51")
      (value "4.7k")
      (footprint "eagle-import:0402-RES")
      (libsource (lib "eagle-import") (part "RESISTOR0402"))
    )
    (comp (ref "R52")
      (value "4.7k")
      (footprint "eagle-import:0402-RES")
      (libsource (lib "eagle-import") (part "RESISTOR0402"))
    )
    (comp (ref "R53")
      (value "4.7k")
      (footprint "eagle-import:0402-RES")
      (libsource (lib "eagle-import") (part "RESISTOR0402"))
    )
    (comp (ref "R61")
      (value "1K")
      (footprint "eagle-import:0402-RES")
      (libsource (lib "eagle-import") (part "RESISTOR0402"))
    )
    (comp (ref "R62")
      (value "1K")
      (footprint "eagle-import:0402-RES")
      (libsource (lib "eagle-import") (part "RESISTOR0402"))
    )
    (comp (ref "R63")
      (value "1K")
      (footprint "eagle-import:0402-RES")
      (libsource (lib "eagle-import") (part "RESISTOR0402"))
    )
    (comp (ref "R64")
      (value "1K")
      (footprint "eagle-import:0402-RES")
      (libsource (lib "eagle-import") (part "RESISTOR0402"))
    )
    (comp (ref "R91")
      (value "240")
      (footprint "eagle-import:0402-RES")
      (libsource (lib "eagle-import") (part "RESISTOR0402"))
    )
    (comp (ref "R107")
      (value ".1, 0805")
      (footprint "eagle-import:R0805")
      (libsource (lib "eagle-import") (part "RESISTOR0805"))
    )
    (comp (ref "RST")
      (value "RS032G05A3SM-SPST-MOMENTARY-SWSMD-1101NE")
      (footprint "eagle-import:TACTILE-SWITCH-1101NE")
      (libsource (lib "eagle-import") (part "RS032G05A3SM-SPST-MOMENTARY-SWSMD-1101NE"))
    )
    (comp (ref "S1.1")
      (value "JST_SH_6")
      (footprint "eagle-import:JST_SH_6")
      (libsource (lib "eagle-import") (part "JST_SH_6"))
    )
    (comp (ref "S1.2")
      (value "JST_SH_6")
      (footprint "eagle-import:JST_SH_6")
      (libsource (lib "eagle-import") (part "JST_SH_6"))
    )
    (comp (ref "SD")
      (value "RS032G05A3SM-SPST-MOMENTARY-SWSMD-1101NE")
      (footprint "eagle-import:TACTILE-SWITCH-1101NE")
      (libsource (lib "eagle-import") (part "RS032G05A3SM-SPST-MOMENTARY-SWSMD-1101NE"))
    )
    (comp (ref "UT0")
      (value "JST_SH_4")
      (footprint "eagle-import:JST_SH_4_SMD")
      (libsource (lib "eagle-import") (part "JST_SH_4"))
    )
    (comp (ref "UT1")
      (value "JST_SH_4")
      (footprint "eagle-import:JST_SH_4_SMD")
      (libsource (lib "eagle-import") (part "JST_SH_4"))
    )
    (comp (ref "UT5")
      (value "JST_SH_4")
      (footprint "eagle-import:JST_SH_4_SMD")
      (libsource (lib "eagle-import") (part "JST_SH_4"))
    )
    (comp (ref "WIFI")
      (value "GREEN")
      (footprint "eagle-import:0603-GREEN")
      (libsource (lib "eagle-import") (part "LED-GREEN0603"))
    )
    (comp (ref "C27")
      (value "0.1uF")
      (footprint "eagle-import:0402-CAP")
      (libsource (lib "eagle-import") (part "CAPACITOR-N0402"))
    )
    (comp (ref "C28")
      (value "0.1uF")
      (footprint "eagle-import:0402-CAP")
      (libsource (lib "eagle-import") (part "CAPACITOR-N0402"))
    )
    (comp (ref "C29")
      (value "10pF")
      (footprint "eagle-import:0402-CAP")
      (libsource (lib "eagle-import") (part "CAPACITOR-N0402"))
    )
    (comp (ref "C30")
      (value "10pF")
      (footprint "eagle-import:0402-CAP")
      (libsource (lib "eagle-import") (part "CAPACITOR-N0402"))
    )
    (comp (ref "C31")
      (value "10pF")
      (footprint "eagle-import:0402-CAP")
      (libsource (lib "eagle-import") (part "CAPACITOR-N0402"))
    )
    (comp (ref "C32")
      (value "10pF")
      (footprint "eagle-import:0402-CAP")
      (libsource (lib "eagle-import") (part "CAPACITOR-N0402"))
    )
    (comp (ref "C33")
      (value "2.2uF")
      (footprint "eagle-import:0402-CAP")
      (libsource (lib "eagle-import") (part "CAPACITOR-N0402"))
    )
    (comp (ref "C34")
      (value "10uF")
      (footprint "eagle-import:0805")
      (libsource (lib "eagle-import") (part "CAPACITOR-N0805"))
    )
    (comp (ref "C35")
      (value "0.1uF")
      (footprint "eagle-import:0402-CAP")
      (libsource (lib "eagle-import") (part "CAPACITOR-N0402"))
    )
    (comp (ref "C36")
      (value "2.2uF")
      (footprint "eagle-import:0402-CAP")
      (libsource (lib "eagle-import") (part "CAPACITOR-N0402"))
    )
    (comp (ref "C37")
      (value "0.1uF")
      (footprint "eagle-import:0402-CAP")
      (libsource (lib "eagle-import") (part "CAPACITOR-N0402"))
    )
    (comp (ref "C38")
      (value "10uF")
      (footprint "eagle-import:0805")
      (libsource (lib "eagle-import") (part "CAPACITOR-N0805"))
    )
    (comp (ref "C39")
      (value "0.1uF")
      (footprint "eagle-import:0402-CAP")
      (libsource (lib "eagle-import") (part "CAPACITOR-N0402"))
    )
    (comp (ref "C40")
      (value "0.1uF")
      (footprint "eagle-import:0402-CAP")
      (libsource (lib "eagle-import") (part "CAPACITOR-N0402"))
    )
    (comp (ref "C41")
      (value "0.1uF")
      (footprint "eagle-import:0402-CAP")
      (libsource (lib "eagle-import") (part "CAPACITOR-N0402"))
    )
    (comp (ref "EMU0")
      (value "TESTPAD_TPSQB1,27")
      (footprint "eagle-import:TESTPAD_B1,27")
      (libsource (lib "eagle-import") (part "TESTPAD_TPSQB1,27"))
    )
    (comp (ref "EMU1")
      (value "TESTPAD_TPSQB1,27")
      (footprint "eagle-import:TESTPAD_B1,27")
      (libsource (lib "eagle-import") (part "TESTPAD_TPSQB1,27"))
    )
    (comp (ref "GND")
      (value "TESTPAD/W_HOLE_1X1")
      (footprint "eagle-import:DIODE_GHI2_TESTPAD_W_HOLE_1X1")
      (libsource (lib "eagle-import") (part "TESTPAD/W_HOLE_1X1"))
    )
    (comp (ref "ON")
      (value "BLUE")
      (footprint "eagle-import:BEAGLEBONE_BLUE_BEAGLEBONE_BLUE_LED-0603")
      (libsource (lib "eagle-import") (part "BEAGLEBONE_BLUE_LED0603"))
    )
    (comp (ref "R2")
      (value "1.5K")
      (footprint "eagle-import:0402-RES")
      (libsource (lib "eagle-import") (part "RESISTOR0402"))
    )
    (comp (ref "R15")
      (value "33")
      (footprint "eagle-import:0402-RES")
      (libsource (lib "eagle-import") (part "RESISTOR0402"))
    )
    (comp (ref "R18")
      (value "1M")
      (footprint "eagle-import:0402-RES")
      (libsource (lib "eagle-import") (part "RESISTOR0402"))
    )
    (comp (ref "R20")
      (value "1M")
      (footprint "eagle-import:0402-RES")
      (libsource (lib "eagle-import") (part "RESISTOR0402"))
    )
    (comp (ref "R23")
      (value "1.5K")
      (footprint "eagle-import:0402-RES")
      (libsource (lib "eagle-import") (part "RESISTOR0402"))
    )
    (comp (ref "R24")
      (value "4.7k")
      (footprint "eagle-import:0402-RES")
      (libsource (lib "eagle-import") (part "RESISTOR0402"))
    )
    (comp (ref "R26")
      (value "10K")
      (footprint "eagle-import:0402-RES")
      (libsource (lib "eagle-import") (part "RESISTOR0402"))
    )
    (comp (ref "R35")
      (value "10K")
      (footprint "eagle-import:0402-RES")
      (libsource (lib "eagle-import") (part "RESISTOR0402"))
    )
    (comp (ref "R54")
      (value "10K")
      (footprint "eagle-import:0402-RES")
      (libsource (lib "eagle-import") (part "RESISTOR0402"))
    )
    (comp (ref "R55")
      (value "10K")
      (footprint "eagle-import:0402-RES")
      (libsource (lib "eagle-import") (part "RESISTOR0402"))
    )
    (comp (ref "R56")
      (value "10K")
      (footprint "eagle-import:0402-RES")
      (libsource (lib "eagle-import") (part "RESISTOR0402"))
    )
    (comp (ref "R57")
      (value "10K")
      (footprint "eagle-import:0402-RES")
      (libsource (lib "eagle-import") (part "RESISTOR0402"))
    )
    (comp (ref "R58")
      (value "1.5K")
      (footprint "eagle-import:0402-RES")
      (libsource (lib "eagle-import") (part "RESISTOR0402"))
    )
    (comp (ref "R59")
      (value "4.7k")
      (footprint "eagle-import:0402-RES")
      (libsource (lib "eagle-import") (part "RESISTOR0402"))
    )
    (comp (ref "R60")
      (value "10K")
      (footprint "eagle-import:0402-RES")
      (libsource (lib "eagle-import") (part "RESISTOR0402"))
    )
    (comp (ref "R65")
      (value "10K")
      (footprint "eagle-import:0402-RES")
      (libsource (lib "eagle-import") (part "RESISTOR0402"))
    )
    (comp (ref "R66")
      (value "10K")
      (footprint "eagle-import:0402-RES")
      (libsource (lib "eagle-import") (part "RESISTOR0402"))
    )
    (comp (ref "R67")
      (value "10K")
      (footprint "eagle-import:0402-RES")
      (libsource (lib "eagle-import") (part "RESISTOR0402"))
    )
    (comp (ref "R68")
      (value "10K")
      (footprint "eagle-import:0402-RES")
      (libsource (lib "eagle-import") (part "RESISTOR0402"))
    )
    (comp (ref "R69")
      (value "10K")
      (footprint "eagle-import:0402-RES")
      (libsource (lib "eagle-import") (part "RESISTOR0402"))
    )
    (comp (ref "R70")
      (value "10K")
      (footprint "eagle-import:0402-RES")
      (libsource (lib "eagle-import") (part "RESISTOR0402"))
    )
    (comp (ref "R71")
      (value "10K")
      (footprint "eagle-import:0402-RES")
      (libsource (lib "eagle-import") (part "RESISTOR0402"))
    )
    (comp (ref "R72")
      (value "10K")
      (footprint "eagle-import:0402-RES")
      (libsource (lib "eagle-import") (part "RESISTOR0402"))
    )
    (comp (ref "R73")
      (value "10K")
      (footprint "eagle-import:0402-RES")
      (libsource (lib "eagle-import") (part "RESISTOR0402"))
    )
    (comp (ref "R74")
      (value "10K")
      (footprint "eagle-import:0402-RES")
      (libsource (lib "eagle-import") (part "RESISTOR0402"))
    )
    (comp (ref "R75")
      (value "10K")
      (footprint "eagle-import:0402-RES")
      (libsource (lib "eagle-import") (part "RESISTOR0402"))
    )
    (comp (ref "R94")
      (value "10K")
      (footprint "eagle-import:0402-RES")
      (libsource (lib "eagle-import") (part "RESISTOR0402"))
    )
    (comp (ref "R104")
      (value "120, DNP")
      (footprint "eagle-import:R0603")
      (libsource (lib "eagle-import") (part "RESISTOR0603"))
    )
    (comp (ref "TCK")
      (value "TESTPAD_TPSQB1,27")
      (footprint "eagle-import:TESTPAD_B1,27")
      (libsource (lib "eagle-import") (part "TESTPAD_TPSQB1,27"))
    )
    (comp (ref "TDI")
      (value "TESTPAD_TPSQB1,27")
      (footprint "eagle-import:TESTPAD_B1,27")
      (libsource (lib "eagle-import") (part "TESTPAD_TPSQB1,27"))
    )
    (comp (ref "TDO")
      (value "TESTPAD_TPSQB1,27")
      (footprint "eagle-import:TESTPAD_B1,27")
      (libsource (lib "eagle-import") (part "TESTPAD_TPSQB1,27"))
    )
    (comp (ref "TMS")
      (value "TESTPAD_TPSQB1,27")
      (footprint "eagle-import:TESTPAD_B1,27")
      (libsource (lib "eagle-import") (part "TESTPAD_TPSQB1,27"))
    )
    (comp (ref "TP1")
      (value "TESTPAD_TPSQB1,27")
      (footprint "eagle-import:TESTPAD_B1,27")
      (libsource (lib "eagle-import") (part "TESTPAD_TPSQB1,27"))
    )
    (comp (ref "TP5")
      (value "TPB0,65")
      (footprint "eagle-import:B0,65")
      (libsource (lib "eagle-import") (part "TPB0,65"))
    )
    (comp (ref "TP12")
      (value "TESTPAD_TPSQB1,27")
      (footprint "eagle-import:TESTPAD_B1,27")
      (libsource (lib "eagle-import") (part "TESTPAD_TPSQB1,27"))
    )
    (comp (ref "TRSTN")
      (value "TESTPAD_TPSQB1,27")
      (footprint "eagle-import:TESTPAD_B1,27")
      (libsource (lib "eagle-import") (part "TESTPAD_TPSQB1,27"))
    )
    (comp (ref "U1")
      (value "TCAN1051HV")
      (footprint "eagle-import:D8")
      (fields
        (field (name "MANUFACTURER") "Texas Instruments")
        (field (name "MANUFACTURER_PART_NUMBER") "TCAN1051HVD")
      )
      (libsource (lib "eagle-import") (part "TCAN1051HV"))
    )
    (comp (ref "U5")
      (value "MICROCHIP-24LCXXX_24LC_32AT-I/OT")
      (footprint "eagle-import:MICROCHIP-24LCXXX_SOT95P290X145-5N")
      (fields (field (name "MPN") "24LC32AT-I/OT"))
      (libsource (lib "eagle-import") (part "MICROCHIP-24LCXXX_24LC_32AT-I/OT"))
    )
    (comp (ref "U6")
      (value "SN74LVC1G07_DCK_5")
      (footprint "eagle-import:DCK5")
      (fields
        (field (name "GENERIC_PART_NUMBER") "SN74LVC1G07")
        (field (name "MANUFACTURER") "Texas Instruments")
        (field (name "MANUFACTURER_PART_NUMBER") "sn74lvc1g07_dck_5")
      )
      (libsource (lib "eagle-import") (part "SN74LVC1G07_DCK_5"))
    )
    (comp (ref "U13")
      (value "EMMC")
      (footprint "eagle-import:MICRON_EMMC_153")
      (libsource (lib "eagle-import") (part "EMMC04G-S100-B08U"))
    )
    (comp (ref "WP")
      (value "TESTPAD/W_HOLE_1X1")
      (footprint "eagle-import:DIODE_GHI2_TESTPAD_W_HOLE_1X1")
      (libsource (lib "eagle-import") (part "TESTPAD/W_HOLE_1X1"))
    )
    (comp (ref "X2")
      (value "SCHA5B0200")
      (footprint "eagle-import:GHI-CONNECTORS_SCHA5B0200")
      (libsource (lib "eagle-import") (part "SCHA5B0200(ALPS_USD)"))
    )
    (comp (ref "Y1")
      (value "24 MHz")
      (footprint "eagle-import:GHI2_CRYSTAL_5X3.2MM")
      (libsource (lib "eagle-import") (part "CRYSTAL_5X3.2MM"))
    )
    (comp (ref "Y2")
      (value "32.768kHz")
      (footprint "eagle-import:GHI2_CRYSTAL_3.2X1.5")
      (libsource (lib "eagle-import") (part "CRYSTAL_3.2X1.5"))
    )
    (comp (ref "C42")
      (value "1nF")
      (footprint "eagle-import:0402-CAP")
      (libsource (lib "eagle-import") (part "CAPACITOR-N0402"))
    )
    (comp (ref "C43")
      (value "0.1uF")
      (footprint "eagle-import:0402-CAP")
      (libsource (lib "eagle-import") (part "CAPACITOR-N0402"))
    )
    (comp (ref "C44")
      (value "0.1uF")
      (footprint "eagle-import:0402-CAP")
      (libsource (lib "eagle-import") (part "CAPACITOR-N0402"))
    )
    (comp (ref "C45")
      (value "0.1uF")
      (footprint "eagle-import:0402-CAP")
      (libsource (lib "eagle-import") (part "CAPACITOR-N0402"))
    )
    (comp (ref "C46")
      (value "10uF")
      (footprint "eagle-import:0805")
      (libsource (lib "eagle-import") (part "CAPACITOR-N0805"))
    )
    (comp (ref "C54")
      (value "0.1uF")
      (footprint "eagle-import:0402-CAP")
      (libsource (lib "eagle-import") (part "CAPACITOR-N0402"))
    )
    (comp (ref "C55")
      (value "0.1uF")
      (footprint "eagle-import:0402-CAP")
      (libsource (lib "eagle-import") (part "CAPACITOR-N0402"))
    )
    (comp (ref "C61")
      (value "1uF")
      (footprint "eagle-import:0402-CAP")
      (libsource (lib "eagle-import") (part "CAPACITOR-N0402"))
    )
    (comp (ref "C62")
      (value "0.22uF")
      (footprint "eagle-import:0402-CAP")
      (libsource (lib "eagle-import") (part "CAPACITOR-N0402"))
    )
    (comp (ref "C63")
      (value "0.22uF")
      (footprint "eagle-import:0402-CAP")
      (libsource (lib "eagle-import") (part "CAPACITOR-N0402"))
    )
    (comp (ref "L4")
      (value "120")
      (footprint "eagle-import:INDUCTOR_L0603")
      (libsource (lib "eagle-import") (part "INDUCTOR/FERRITE-BEAD0603"))
    )
    (comp (ref "L5")
      (value "120")
      (footprint "eagle-import:INDUCTOR_L0603")
      (libsource (lib "eagle-import") (part "INDUCTOR/FERRITE-BEAD0603"))
    )
    (comp (ref "R16")
      (value "100K")
      (footprint "eagle-import:0402-RES")
      (libsource (lib "eagle-import") (part "RESISTOR0402"))
    )
    (comp (ref "R17")
      (value "100K")
      (footprint "eagle-import:0402-RES")
      (libsource (lib "eagle-import") (part "RESISTOR0402"))
    )
    (comp (ref "R76")
      (value "33")
      (footprint "eagle-import:0402-RES")
      (libsource (lib "eagle-import") (part "RESISTOR0402"))
    )
    (comp (ref "R77")
      (value "33")
      (footprint "eagle-import:0402-RES")
      (libsource (lib "eagle-import") (part "RESISTOR0402"))
    )
    (comp (ref "R95")
      (value "100K")
      (footprint "eagle-import:0402-RES")
      (libsource (lib "eagle-import") (part "RESISTOR0402"))
    )
    (comp (ref "R109")
      (value "4.7k")
      (footprint "eagle-import:0402-RES")
      (libsource (lib "eagle-import") (part "RESISTOR0402"))
    )
    (comp (ref "R110")
      (value "4.7k")
      (footprint "eagle-import:0402-RES")
      (libsource (lib "eagle-import") (part "RESISTOR0402"))
    )
    (comp (ref "R111")
      (value "0")
      (footprint "eagle-import:0402-RES")
      (libsource (lib "eagle-import") (part "RESISTOR0402"))
    )
    (comp (ref "R112")
      (value "0")
      (footprint "eagle-import:R0603")
      (libsource (lib "eagle-import") (part "RESISTOR0603"))
    )
    (comp (ref "R113")
      (value "100K")
      (footprint "eagle-import:0402-RES")
      (libsource (lib "eagle-import") (part "RESISTOR0402"))
    )
    (comp (ref "R115")
      (value "100K")
      (footprint "eagle-import:0402-RES")
      (libsource (lib "eagle-import") (part "RESISTOR0402"))
    )
    (comp (ref "R116")
      (value "100K")
      (footprint "eagle-import:0402-RES")
      (libsource (lib "eagle-import") (part "RESISTOR0402"))
    )
    (comp (ref "R118")
      (value "100K")
      (footprint "eagle-import:0402-RES")
      (libsource (lib "eagle-import") (part "RESISTOR0402"))
    )
    (comp (ref "R119")
      (value "0, DNP")
      (footprint "eagle-import:R0603")
      (libsource (lib "eagle-import") (part "RESISTOR0603"))
    )
    (comp (ref "R120")
      (value "100K")
      (footprint "eagle-import:0402-RES")
      (libsource (lib "eagle-import") (part "RESISTOR0402"))
    )
    (comp (ref "R121")
      (value "0, DNP")
      (footprint "eagle-import:R0603")
      (libsource (lib "eagle-import") (part "RESISTOR0603"))
    )
    (comp (ref "R122")
      (value "100K")
      (footprint "eagle-import:0402-RES")
      (libsource (lib "eagle-import") (part "RESISTOR0402"))
    )
    (comp (ref "R125")
      (value "100K")
      (footprint "eagle-import:0402-RES")
      (libsource (lib "eagle-import") (part "RESISTOR0402"))
    )
    (comp (ref "R127")
      (value "100K")
      (footprint "eagle-import:0402-RES")
      (libsource (lib "eagle-import") (part "RESISTOR0402"))
    )
    (comp (ref "R129")
      (value "100K")
      (footprint "eagle-import:0402-RES")
      (libsource (lib "eagle-import") (part "RESISTOR0402"))
    )
    (comp (ref "R131")
      (value "100K")
      (footprint "eagle-import:0402-RES")
      (libsource (lib "eagle-import") (part "RESISTOR0402"))
    )
    (comp (ref "R135")
      (value "100K")
      (footprint "eagle-import:0402-RES")
      (libsource (lib "eagle-import") (part "RESISTOR0402"))
    )
    (comp (ref "R140")
      (value "100K")
      (footprint "eagle-import:0402-RES")
      (libsource (lib "eagle-import") (part "RESISTOR0402"))
    )
    (comp (ref "R143")
      (value "100K")
      (footprint "eagle-import:0402-RES")
      (libsource (lib "eagle-import") (part "RESISTOR0402"))
    )
    (comp (ref "R149")
      (value "0")
      (footprint "eagle-import:0402-RES")
      (libsource (lib "eagle-import") (part "RESISTOR0402"))
    )
    (comp (ref "R150")
      (value "0")
      (footprint "eagle-import:0402-RES")
      (libsource (lib "eagle-import") (part "RESISTOR0402"))
    )
    (comp (ref "R156")
      (value "33")
      (footprint "eagle-import:0402-RES")
      (libsource (lib "eagle-import") (part "RESISTOR0402"))
    )
    (comp (ref "U3")
      (value "TPD4S012DRY")
      (footprint "eagle-import:SON-6(TI)-DRY")
      (libsource (lib "eagle-import") (part "TPD4S012DRYR"))
    )
    (comp (ref "U4")
      (value "TPD4S012DRY")
      (footprint "eagle-import:SON-6(TI)-DRY")
      (libsource (lib "eagle-import") (part "TPD4S012DRYR"))
    )
    (comp (ref "U8")
      (value "TPS2105_DBV_5")
      (footprint "eagle-import:DIODE_DBV5")
      (fields
        (field (name "GENERIC_PART_NUMBER") "TPS2105")
        (field (name "MANUFACTURER") "Texas Instruments")
        (field (name "MANUFACTURER_PART_NUMBER") "tps2105_dbv_5")
      )
      (libsource (lib "eagle-import") (part "TPS2105_DBV_5"))
    )
    (comp (ref "X3")
      (value "USB1")
      (footprint "eagle-import:GHI2_USB_HOST_HORIZONTAL_W_CHASSIS_GND")
      (libsource (lib "eagle-import") (part "USB_HOST_W/CHASSIS_GND"))
    )
    (comp (ref "X4")
      (value "10118192-0001LF")
      (footprint "eagle-import:GHI-CONNECTORS_10118192-0001LF(MICRO-USB-B-AMPHENOL-FCI)")
      (libsource (lib "eagle-import") (part "10118192-0001LF"))
    )
  )
  (nets
    (net (code "1") (name "3.3V") (class "Default")
      (node (ref "BMP") (pin "2") (pinfunction "CSB_2") (pintype "input"))
      (node (ref "BMP") (pin "6") (pinfunction "VDDIO_6") (pintype "input"))
      (node (ref "BMP") (pin "8") (pinfunction "VDD_8") (pintype "power_in"))
      (node (ref "C13") (pin "1") (pinfunction "1_1") (pintype "passive"))
      (node (ref "C16") (pin "1") (pinfunction "1_1") (pintype "passive"))
      (node (ref "C2") (pin "2") (pinfunction "2_2") (pintype "passive"))
      (node (ref "C27") (pin "1") (pinfunction "1_1") (pintype "passive"))
      (node (ref "C28") (pin "1") (pinfunction "1_1") (pintype "passive"))
      (node (ref "C34") (pin "2") (pinfunction "2_2") (pintype "passive"))
      (node (ref "C35") (pin "2") (pinfunction "2_2") (pintype "passive"))
      (node (ref "C37") (pin "1") (pinfunction "1_1") (pintype "passive"))
      (node (ref "C38") (pin "1") (pinfunction "1_1") (pintype "passive"))
      (node (ref "C39") (pin "1") (pinfunction "1_1") (pintype "passive"))
      (node (ref "C40") (pin "1") (pinfunction "1_1") (pintype "passive"))
      (node (ref "C41") (pin "1") (pinfunction "1_1") (pintype "passive"))
      (node (ref "C49") (pin "2") (pinfunction "2_2") (pintype "passive"))
      (node (ref "C51") (pin "2") (pinfunction "2_2") (pintype "passive"))
      (node (ref "C53") (pin "1") (pinfunction "1_1") (pintype "passive"))
      (node (ref "C56") (pin "1") (pinfunction "1_1") (pintype "passive"))
      (node (ref "C59") (pin "1") (pinfunction "1_1") (pintype "passive"))
      (node (ref "C8") (pin "1") (pinfunction "1_1") (pintype "passive"))
      (node (ref "C9") (pin "2") (pinfunction "2_2") (pintype "passive"))
      (node (ref "CAN") (pin "2") (pinfunction "2_2") (pintype "bidirectional"))
      (node (ref "DSM2") (pin "P$1") (pinfunction "1_P$1") (pintype "bidirectional"))
      (node (ref "E1") (pin "2") (pinfunction "2_2") (pintype "bidirectional"))
      (node (ref "E2") (pin "2") (pinfunction "2_2") (pintype "bidirectional"))
      (node (ref "E3") (pin "2") (pinfunction "2_2") (pintype "bidirectional"))
      (node (ref "E4") (pin "2") (pinfunction "2_2") (pintype "bidirectional"))
      (node (ref "GP0") (pin "2") (pinfunction "2_2") (pintype "bidirectional"))
      (node (ref "GP1") (pin "2") (pinfunction "2_2") (pintype "bidirectional"))
      (node (ref "H1") (pin "20") (pinfunction "VCC_20") (pintype "bidirectional"))
      (node (ref "H2") (pin "20") (pinfunction "VCC_20") (pintype "bidirectional"))
      (node (ref "I2C") (pin "2") (pinfunction "2_2") (pintype "bidirectional"))
      (node (ref "IMU") (pin "1") (pinfunction "RESV_1") (pintype "bidirectional"))
      (node (ref "IMU") (pin "13") (pinfunction "VDD_13") (pintype "bidirectional"))
      (node (ref "IMU") (pin "22") (pinfunction "NCS_22") (pintype "bidirectional"))
      (node (ref "IMU") (pin "8") (pinfunction "VDDIO_8") (pintype "bidirectional"))
      (node (ref "PWR") (pin "3") (pinfunction "3_3") (pintype "bidirectional"))
      (node (ref "R10") (pin "1") (pinfunction "1_1") (pintype "passive"))
      (node (ref "R109") (pin "1") (pinfunction "1_1") (pintype "passive"))
      (node (ref "R11") (pin "2") (pinfunction "2_2") (pintype "passive"))
      (node (ref "R116") (pin "2") (pinfunction "2_2") (pintype "passive"))
      (node (ref "R118") (pin "2") (pinfunction "2_2") (pintype "passive"))
      (node (ref "R12") (pin "2") (pinfunction "2_2") (pintype "passive"))
      (node (ref "R120") (pin "2") (pinfunction "2_2") (pintype "passive"))
      (node (ref "R122") (pin "2") (pinfunction "2_2") (pintype "passive"))
      (node (ref "R13") (pin "1") (pinfunction "1_1") (pintype "passive"))
      (node (ref "R140") (pin "2") (pinfunction "2_2") (pintype "passive"))
      (node (ref "R2") (pin "2") (pinfunction "2_2") (pintype "passive"))
      (node (ref "R23") (pin "2") (pinfunction "2_2") (pintype "passive"))
      (node (ref "R26") (pin "2") (pinfunction "2_2") (pintype "passive"))
      (node (ref "R35") (pin "2") (pinfunction "2_2") (pintype "passive"))
      (node (ref "R54") (pin "2") (pinfunction "2_2") (pintype "passive"))
      (node (ref "R55") (pin "2") (pinfunction "2_2") (pintype "passive"))
      (node (ref "R56") (pin "2") (pinfunction "2_2") (pintype "passive"))
      (node (ref "R57") (pin "2") (pinfunction "2_2") (pintype "passive"))
      (node (ref "R58") (pin "2") (pinfunction "2_2") (pintype "passive"))
      (node (ref "R60") (pin "2") (pinfunction "2_2") (pintype "passive"))
      (node (ref "R65") (pin "2") (pinfunction "2_2") (pintype "passive"))
      (node (ref "R66") (pin "2") (pinfunction "2_2") (pintype "passive"))
      (node (ref "R67") (pin "2") (pinfunction "2_2") (pintype "passive"))
      (node (ref "R68") (pin "2") (pinfunction "2_2") (pintype "passive"))
      (node (ref "R69") (pin "2") (pinfunction "2_2") (pintype "passive"))
      (node (ref "R70") (pin "2") (pinfunction "2_2") (pintype "passive"))
      (node (ref "R71") (pin "2") (pinfunction "2_2") (pintype "passive"))
      (node (ref "R72") (pin "2") (pinfunction "2_2") (pintype "passive"))
      (node (ref "R73") (pin "2") (pinfunction "2_2") (pintype "passive"))
      (node (ref "R74") (pin "2") (pinfunction "2_2") (pintype "passive"))
      (node (ref "R75") (pin "2") (pinfunction "2_2") (pintype "passive"))
      (node (ref "R94") (pin "2") (pinfunction "2_2") (pintype "passive"))
      (node (ref "S1.1") (pin "2") (pinfunction "2_2") (pintype "bidirectional"))
      (node (ref "S1.2") (pin "2") (pinfunction "2_2") (pintype "bidirectional"))
      (node (ref "SIP") (pin "U20") (pinfunction "VOUT_USER_3P3V_0_U20") (pintype "power_in"))
      (node (ref "SIP") (pin "V20") (pinfunction "VOUT_USER_3P3V_1_V20") (pintype "power_in"))
      (node (ref "U1") (pin "5") (pinfunction "VIO_5") (pintype "power_in"))
      (node (ref "U10") (pin "19") (pinfunction "VCCB_19") (pintype "bidirectional"))
      (node (ref "U13") (pin "C6") (pinfunction "VCCQ1_C6") (pintype "bidirectional"))
      (node (ref "U13") (pin "E6") (pinfunction "VCC1_E6") (pintype "bidirectional"))
      (node (ref "U13") (pin "F5") (pinfunction "VCC2_F5") (pintype "bidirectional"))
      (node (ref "U13") (pin "J10") (pinfunction "VCC3_J10") (pintype "bidirectional"))
      (node (ref "U13") (pin "K9") (pinfunction "VCC4_K9") (pintype "bidirectional"))
      (node (ref "U13") (pin "M4") (pinfunction "VCCQ2_M4") (pintype "bidirectional"))
      (node (ref "U13") (pin "N4") (pinfunction "VCCQ3_N4") (pintype "bidirectional"))
      (node (ref "U13") (pin "P3") (pinfunction "VCCQ4_P3") (pintype "bidirectional"))
      (node (ref "U13") (pin "P5") (pinfunction "VCCQ5_P5") (pintype "bidirectional"))
      (node (ref "U5") (pin "4") (pinfunction "VCC_4") (pintype "power_in"))
      (node (ref "U7") (pin "46") (pinfunction "VBAT_IN1_46") (pintype "bidirectional"))
      (node (ref "U7") (pin "47") (pinfunction "VBAT_IN2_47") (pintype "bidirectional"))
      (node (ref "U9") (pin "19") (pinfunction "VCCB_19") (pintype "bidirectional"))
      (node (ref "UT0") (pin "2") (pinfunction "2_2") (pintype "bidirectional"))
      (node (ref "UT1") (pin "2") (pinfunction "2_2") (pintype "bidirectional"))
      (node (ref "UT5") (pin "2") (pinfunction "2_2") (pintype "bidirectional"))
      (node (ref "X2") (pin "4") (pinfunction "VDD_4") (pintype "bidirectional"))
    )
    (net (code "2") (name "5.0V") (class "Default")
      (node (ref "5VREG") (pin "3") (pinfunction "FB_3") (pintype "power_in"))
      (node (ref "C5") (pin "1") (pinfunction "1_1") (pintype "passive"))
      (node (ref "C63") (pin "1") (pinfunction "1_1") (pintype "passive"))
      (node (ref "GPS") (pin "5") (pinfunction "5_5") (pintype "bidirectional"))
      (node (ref "L1") (pin "2") (pinfunction "2_2") (pintype "passive"))
      (node (ref "PWR") (pin "4") (pinfunction "4_4") (pintype "bidirectional"))
      (node (ref "R119") (pin "2") (pinfunction "2_2") (pintype "passive"))
      (node (ref "R95") (pin "2") (pinfunction "2_2") (pintype "passive"))
      (node (ref "SIP") (pin "Y5") (pinfunction "VIN_AC_0_Y5") (pintype "power_in"))
      (node (ref "SIP") (pin "Y6") (pinfunction "VIN_AC_1_Y6") (pintype "power_in"))
      (node (ref "U8") (pin "1") (pinfunction "EN_1") (pintype "input"))
      (node (ref "U8") (pin "5") (pinfunction "IN1_5") (pintype "input"))
    )
    (net (code "3") (name "32.768KHZ") (class "Default")
      (node (ref "OSC1") (pin "3") (pinfunction "OUT_3") (pintype "bidirectional"))
      (node (ref "U7") (pin "36") (pinfunction "EXT_32K_36") (pintype "bidirectional"))
    )
    (net (code "4") (name "AIN0") (class "Default")
      (node (ref "ADC") (pin "3") (pinfunction "3_3") (pintype "bidirectional"))
      (node (ref "SIP") (pin "B6") (pinfunction "AIN0_B6") (pintype "bidirectional"))
    )
    (net (code "5") (name "AIN1") (class "Default")
      (node (ref "ADC") (pin "4") (pinfunction "4_4") (pintype "bidirectional"))
      (node (ref "SIP") (pin "C7") (pinfunction "AIN1_C7") (pintype "bidirectional"))
    )
    (net (code "6") (name "AIN2") (class "Default")
      (node (ref "ADC") (pin "5") (pinfunction "5_5") (pintype "bidirectional"))
      (node (ref "SIP") (pin "B7") (pinfunction "AIN2_B7") (pintype "bidirectional"))
    )
    (net (code "7") (name "AIN3") (class "Default")
      (node (ref "ADC") (pin "6") (pinfunction "6_6") (pintype "bidirectional"))
      (node (ref "SIP") (pin "A7") (pinfunction "AIN3_A7") (pintype "bidirectional"))
    )
    (net (code "8") (name "BATT_LED_1") (class "Default")
      (node (ref "B0") (pin "A") (pinfunction "A_A") (pintype "passive"))
      (node (ref "SIP") (pin "U12") (pinfunction "GPIO0_27_U12_U12") (pintype "bidirectional"))
    )
    (net (code "9") (name "BATT_LED_2") (class "Default")
      (node (ref "B1") (pin "A") (pinfunction "A_A") (pintype "passive"))
      (node (ref "R143") (pin "2") (pinfunction "2_2") (pintype "passive"))
      (node (ref "SIP") (pin "T5") (pinfunction "LCD_DATA15_T5_T5") (pintype "bidirectional"))
    )
    (net (code "10") (name "BATT_LED_3") (class "Default")
      (node (ref "B2") (pin "A") (pinfunction "A_A") (pintype "passive"))
      (node (ref "SIP") (pin "V6") (pinfunction "GPIO1_29_V6_V6") (pintype "bidirectional"))
    )
    (net (code "11") (name "BATT_LED_4") (class "Default")
      (node (ref "B3") (pin "A") (pinfunction "A_A") (pintype "passive"))
      (node (ref "SIP") (pin "T11") (pinfunction "GPIO0_26_T11_T11") (pintype "bidirectional"))
    )
    (net (code "12") (name "BATT_MID") (class "Default")
      (node (ref "LIPO") (pin "P$2") (pinfunction "2_P$2") (pintype "passive"))
      (node (ref "R27") (pin "1") (pinfunction "1_1") (pintype "passive"))
      (node (ref "R30") (pin "1") (pinfunction "1_1") (pintype "passive"))
      (node (ref "R44") (pin "1") (pinfunction "1_1") (pintype "passive"))
    )
    (net (code "13") (name "BATT_MINUS") (class "Default")
      (node (ref "BAL") (pin "5") (pinfunction "GND_5") (pintype "bidirectional"))
      (node (ref "BAL") (pin "6") (pinfunction "CB_EN_6") (pintype "bidirectional"))
      (node (ref "C1") (pin "2") (pinfunction "2_2") (pintype "passive"))
      (node (ref "C15") (pin "1") (pinfunction "1_1") (pintype "passive"))
      (node (ref "C18") (pin "1") (pinfunction "1_1") (pintype "passive"))
      (node (ref "C19") (pin "2") (pinfunction "2_2") (pintype "passive"))
      (node (ref "LIPO") (pin "P$3") (pinfunction "3_P$3") (pintype "passive"))
      (node (ref "PROT") (pin "2") (pinfunction "VM_2") (pintype "bidirectional"))
      (node (ref "PROT") (pin "6") (pinfunction "VSS_6") (pintype "bidirectional"))
      (node (ref "Q1") (pin "1") (pinfunction "S_1") (pintype "passive"))
      (node (ref "Q1") (pin "2") (pinfunction "S_2") (pintype "passive"))
      (node (ref "Q1") (pin "3") (pinfunction "S_3") (pintype "passive"))
    )
    (net (code "14") (name "BT_AUD_CLK") (class "Default")
      (node (ref "R124") (pin "1") (pinfunction "1_1") (pintype "passive"))
      (node (ref "U10") (pin "1") (pinfunction "A1_1") (pintype "bidirectional"))
    )
    (net (code "15") (name "BT_AUD_FSYNC") (class "Default")
      (node (ref "R123") (pin "1") (pinfunction "1_1") (pintype "passive"))
      (node (ref "U10") (pin "3") (pinfunction "A2_3") (pintype "bidirectional"))
    )
    (net (code "16") (name "BT_AUD_IN") (class "Default")
      (node (ref "R97") (pin "1") (pinfunction "1_1") (pintype "passive"))
      (node (ref "U10") (pin "5") (pinfunction "A4_5") (pintype "bidirectional"))
    )
    (net (code "17") (name "BT_AUD_OUT") (class "Default")
      (node (ref "R100") (pin "1") (pinfunction "1_1") (pintype "passive"))
      (node (ref "U10") (pin "4") (pinfunction "A3_4") (pintype "bidirectional"))
    )
    (net (code "18") (name "BT_EN") (class "Default")
      (node (ref "SIP") (pin "K17") (pinfunction "K17_K17") (pintype "bidirectional"))
      (node (ref "U9") (pin "18") (pinfunction "B2_18") (pintype "bidirectional"))
    )
    (net (code "19") (name "BT_EN_1V8") (class "Default")
      (node (ref "R88") (pin "1") (pinfunction "1_1") (pintype "passive"))
      (node (ref "U7") (pin "41") (pinfunction "BT_EN_41") (pintype "bidirectional"))
      (node (ref "U9") (pin "3") (pinfunction "A2_3") (pintype "bidirectional"))
    )
    (net (code "20") (name "BT_HCI_CTS") (class "Default")
      (node (ref "R86") (pin "1") (pinfunction "1_1") (pintype "passive"))
      (node (ref "U10") (pin "8") (pinfunction "A7_8") (pintype "bidirectional"))
    )
    (net (code "21") (name "BT_HCI_RTS") (class "Default")
      (node (ref "R85") (pin "1") (pinfunction "1_1") (pintype "passive"))
      (node (ref "U10") (pin "9") (pinfunction "A8_9") (pintype "bidirectional"))
    )
    (net (code "22") (name "BT_HCI_RX") (class "Default")
      (node (ref "R96") (pin "1") (pinfunction "1_1") (pintype "passive"))
      (node (ref "U10") (pin "6") (pinfunction "A5_6") (pintype "bidirectional"))
    )
    (net (code "23") (name "BT_HCI_TX") (class "Default")
      (node (ref "R92") (pin "1") (pinfunction "1_1") (pintype "passive"))
      (node (ref "U10") (pin "7") (pinfunction "A6_7") (pintype "bidirectional"))
    )
    (net (code "24") (name "CANH") (class "Default")
      (node (ref "CAN") (pin "3") (pinfunction "3_3") (pintype "bidirectional"))
      (node (ref "R104") (pin "1") (pinfunction "1_1") (pintype "passive"))
      (node (ref "U1") (pin "7") (pinfunction "CANH_7") (pintype "bidirectional"))
    )
    (net (code "25") (name "CANL") (class "Default")
      (node (ref "CAN") (pin "4") (pinfunction "4_4") (pintype "bidirectional"))
      (node (ref "R104") (pin "2") (pinfunction "2_2") (pintype "passive"))
      (node (ref "U1") (pin "6") (pinfunction "CANL_6") (pintype "bidirectional"))
    )
    (net (code "26") (name "CGND") (class "Default")
      (node (ref "MGT1") (pin "P$1") (pinfunction "P$1_P$1") (pintype "bidirectional"))
      (node (ref "MGT2") (pin "P$1") (pinfunction "P$1_P$1") (pintype "bidirectional"))
      (node (ref "MGT3") (pin "P$1") (pinfunction "P$1_P$1") (pintype "bidirectional"))
      (node (ref "MGT4") (pin "P$1") (pinfunction "P$1_P$1") (pintype "bidirectional"))
      (node (ref "R107") (pin "2") (pinfunction "2_2") (pintype "passive"))
      (node (ref "X2") (pin "CGND1") (pinfunction "CGND1_CGND1") (pintype "bidirectional"))
      (node (ref "X2") (pin "CGND2") (pinfunction "CGND2_CGND2") (pintype "bidirectional"))
      (node (ref "X2") (pin "CGND3") (pinfunction "CGND3_CGND3") (pintype "bidirectional"))
      (node (ref "X2") (pin "CGND4") (pinfunction "CGND4_CGND4") (pintype "bidirectional"))
      (node (ref "X2") (pin "CGND5") (pinfunction "CGND5_CGND5") (pintype "bidirectional"))
      (node (ref "X2") (pin "CGND6") (pinfunction "CGND6_CGND6") (pintype "bidirectional"))
      (node (ref "X3") (pin "5") (pinfunction "CG1_5") (pintype "bidirectional"))
      (node (ref "X3") (pin "6") (pinfunction "CG2_6") (pintype "bidirectional"))
      (node (ref "X4") (pin "CGND1") (pinfunction "SGND1_CGND1") (pintype "bidirectional"))
      (node (ref "X4") (pin "CGND2") (pinfunction "SGND2_CGND2") (pintype "bidirectional"))
      (node (ref "X4") (pin "CGND3") (pinfunction "SGND3_CGND3") (pintype "bidirectional"))
      (node (ref "X4") (pin "CGND4") (pinfunction "SGND4_CGND4") (pintype "bidirectional"))
      (node (ref "X4") (pin "CGND5") (pinfunction "SGND5_CGND5") (pintype "bidirectional"))
      (node (ref "X4") (pin "CGND6") (pinfunction "SGND6_CGND6") (pintype "bidirectional"))
    )
    (net (code "27") (name "CHG_EN") (class "Default")
      (node (ref "CHGIC") (pin "6") (pinfunction "EN_6") (pintype "bidirectional"))
      (node (ref "R7") (pin "2") (pinfunction "2_2") (pintype "passive"))
      (node (ref "R8") (pin "1") (pinfunction "1_1") (pintype "passive"))
    )
    (net (code "28") (name "DCAN1_RX") (class "Default")
      (node (ref "SIP") (pin "E17") (pinfunction "UART0_RTSN_E17_E17") (pintype "bidirectional"))
      (node (ref "U1") (pin "4") (pinfunction "RXD_4") (pintype "output"))
    )
    (net (code "29") (name "DCAN1_SILENT") (class "Default")
      (node (ref "SIP") (pin "M16") (pinfunction "M16_M16") (pintype "bidirectional"))
      (node (ref "U1") (pin "8") (pinfunction "S_8") (pintype "input"))
    )
    (net (code "30") (name "DCAN1_TX") (class "Default")
      (node (ref "SIP") (pin "E18") (pinfunction "UART0_CTSN_E18_E18") (pintype "bidirectional"))
      (node (ref "U1") (pin "1") (pinfunction "TXD_1") (pintype "input"))
    )
    (net (code "31") (name "DO") (class "Default")
      (node (ref "PROT") (pin "1") (pinfunction "DO_1") (pintype "bidirectional"))
      (node (ref "Q1") (pin "4") (pinfunction "G_4") (pintype "passive"))
    )
    (net (code "32") (name "EMMC_RST") (class "Default")
      (node (ref "R94") (pin "1") (pinfunction "1_1") (pintype "passive"))
      (node (ref "SIP") (pin "R14") (pinfunction "EMMCRST_GPIO1_20_R14_R14") (pintype "bidirectional"))
      (node (ref "U13") (pin "K5") (pinfunction "RST#_K5") (pintype "bidirectional"))
    )
    (net (code "33") (name "EQEP_0A") (class "Default")
      (node (ref "E1") (pin "3") (pinfunction "3_3") (pintype "bidirectional"))
      (node (ref "SIP") (pin "B12") (pinfunction "GPIO3_18_B12_B12") (pintype "bidirectional"))
    )
    (net (code "34") (name "EQEP_0B") (class "Default")
      (node (ref "E1") (pin "4") (pinfunction "4_4") (pintype "bidirectional"))
      (node (ref "SIP") (pin "C13") (pinfunction "GPIO3_19_C13_C13") (pintype "bidirectional"))
    )
    (net (code "35") (name "EQEP_1A") (class "Default")
      (node (ref "E2") (pin "3") (pinfunction "3_3") (pintype "bidirectional"))
      (node (ref "R16") (pin "2") (pinfunction "2_2") (pintype "passive"))
      (node (ref "SIP") (pin "V2") (pinfunction "LCD_DATA12_V2_V2") (pintype "bidirectional"))
    )
    (net (code "36") (name "EQEP_1B") (class "Default")
      (node (ref "E2") (pin "4") (pinfunction "4_4") (pintype "bidirectional"))
      (node (ref "R17") (pin "2") (pinfunction "2_2") (pintype "passive"))
      (node (ref "SIP") (pin "V3") (pinfunction "LCD_DATA13_V3_V3") (pintype "bidirectional"))
    )
    (net (code "37") (name "EQEP_2A") (class "Default")
      (node (ref "E3") (pin "3") (pinfunction "3_3") (pintype "bidirectional"))
      (node (ref "SIP") (pin "T12") (pinfunction "GPIO1_12_T12_T12") (pintype "bidirectional"))
    )
    (net (code "38") (name "EQEP_2B") (class "Default")
      (node (ref "E3") (pin "4") (pinfunction "4_4") (pintype "bidirectional"))
      (node (ref "SIP") (pin "R12") (pinfunction "GPIO1_13_R12_R12") (pintype "bidirectional"))
    )
    (net (code "39") (name "GND") (class "Default")
      (node (ref "12V") (pin "OUT") (pinfunction "OUT_OUT") (pintype "bidirectional"))
      (node (ref "5VREG") (pin "4") (pinfunction "SD_4") (pintype "input"))
      (node (ref "5VREG") (pin "5") (pinfunction "GND_5") (pintype "power_in"))
      (node (ref "5VREG") (pin "6") (pinfunction "GND1_6") (pintype "input"))
      (node (ref "5VREG") (pin "7") (pinfunction "GND2_7") (pintype "passive"))
      (node (ref "5VREG") (pin "8") (pinfunction "GND3_8") (pintype "power_in"))
      (node (ref "6VREG") (pin "3") (pinfunction "GND_3") (pintype "bidirectional"))
      (node (ref "ADC") (pin "1") (pinfunction "1_1") (pintype "bidirectional"))
      (node (ref "ANT1") (pin "GND1") (pinfunction "GND1_GND1") (pintype "bidirectional"))
      (node (ref "ANT1") (pin "GND2") (pinfunction "GND2_GND2") (pintype "bidirectional"))
      (node (ref "ANT2") (pin "GND1") (pinfunction "GND1_GND1") (pintype "bidirectional"))
      (node (ref "ANT2") (pin "GND2") (pinfunction "GND2_GND2") (pintype "bidirectional"))
      (node (ref "BMP") (pin "1") (pinfunction "GND_1") (pintype "power_in"))
      (node (ref "BMP") (pin "5") (pinfunction "SDO_5") (pintype "bidirectional"))
      (node (ref "BMP") (pin "7") (pinfunction "GND_7") (pintype "power_in"))
      (node (ref "C10") (pin "1") (pinfunction "1_1") (pintype "passive"))
      (node (ref "C11") (pin "-") (pinfunction "-_-") (pintype "passive"))
      (node (ref "C12") (pin "2") (pinfunction "2_2") (pintype "passive"))
      (node (ref "C13") (pin "2") (pinfunction "2_2") (pintype "passive"))
      (node (ref "C16") (pin "2") (pinfunction "2_2") (pintype "passive"))
      (node (ref "C2") (pin "1") (pinfunction "1_1") (pintype "passive"))
      (node (ref "C20") (pin "1") (pinfunction "1_1") (pintype "passive"))
      (node (ref "C21") (pin "1") (pinfunction "1_1") (pintype "passive"))
      (node (ref "C23") (pin "1") (pinfunction "1_1") (pintype "passive"))
      (node (ref "C24") (pin "1") (pinfunction "1_1") (pintype "passive"))
      (node (ref "C25") (pin "2") (pinfunction "2_2") (pintype "passive"))
      (node (ref "C26") (pin "2") (pinfunction "2_2") (pintype "passive"))
      (node (ref "C27") (pin "2") (pinfunction "2_2") (pintype "passive"))
      (node (ref "C28") (pin "2") (pinfunction "2_2") (pintype "passive"))
      (node (ref "C3") (pin "2") (pinfunction "2_2") (pintype "passive"))
      (node (ref "C33") (pin "2") (pinfunction "2_2") (pintype "passive"))
      (node (ref "C34") (pin "1") (pinfunction "1_1") (pintype "passive"))
      (node (ref "C35") (pin "1") (pinfunction "1_1") (pintype "passive"))
      (node (ref "C36") (pin "2") (pinfunction "2_2") (pintype "passive"))
      (node (ref "C37") (pin "2") (pinfunction "2_2") (pintype "passive"))
      (node (ref "C38") (pin "2") (pinfunction "2_2") (pintype "passive"))
      (node (ref "C39") (pin "2") (pinfunction "2_2") (pintype "passive"))
      (node (ref "C4") (pin "1") (pinfunction "1_1") (pintype "passive"))
      (node (ref "C40") (pin "2") (pinfunction "2_2") (pintype "passive"))
      (node (ref "C41") (pin "2") (pinfunction "2_2") (pintype "passive"))
      (node (ref "C45") (pin "2") (pinfunction "2_2") (pintype "passive"))
      (node (ref "C46") (pin "2") (pinfunction "2_2") (pintype "passive"))
      (node (ref "C47") (pin "2") (pinfunction "2_2") (pintype "passive"))
      (node (ref "C49") (pin "1") (pinfunction "1_1") (pintype "passive"))
      (node (ref "C5") (pin "2") (pinfunction "2_2") (pintype "passive"))
      (node (ref "C50") (pin "2") (pinfunction "2_2") (pintype "passive"))
      (node (ref "C51") (pin "1") (pinfunction "1_1") (pintype "passive"))
      (node (ref "C52") (pin "2") (pinfunction "2_2") (pintype "passive"))
      (node (ref "C53") (pin "2") (pinfunction "2_2") (pintype "passive"))
      (node (ref "C54") (pin "2") (pinfunction "2_2") (pintype "passive"))
      (node (ref "C55") (pin "2") (pinfunction "2_2") (pintype "passive"))
      (node (ref "C56") (pin "2") (pinfunction "2_2") (pintype "passive"))
      (node (ref "C57") (pin "1") (pinfunction "1_1") (pintype "passive"))
      (node (ref "C59") (pin "2") (pinfunction "2_2") (pintype "passive"))
      (node (ref "C6") (pin "2") (pinfunction "2_2") (pintype "passive"))
      (node (ref "C60") (pin "1") (pinfunction "1_1") (pintype "passive"))
      (node (ref "C61") (pin "1") (pinfunction "1_1") (pintype "passive"))
      (node (ref "C62") (pin "2") (pinfunction "2_2") (pintype "passive"))
      (node (ref "C63") (pin "2") (pinfunction "2_2") (pintype "passive"))
      (node (ref "C7") (pin "2") (pinfunction "2_2") (pintype "passive"))
      (node (ref "C8") (pin "2") (pinfunction "2_2") (pintype "passive"))
      (node (ref "C9") (pin "1") (pinfunction "1_1") (pintype "passive"))
      (node (ref "CAN") (pin "1") (pinfunction "1_1") (pintype "bidirectional"))
      (node (ref "CHGIC") (pin "16") (pinfunction "PGND_16") (pintype "bidirectional"))
      (node (ref "CHGIC") (pin "8") (pinfunction "AGND_8") (pintype "bidirectional"))
      (node (ref "D1") (pin "A") (pinfunction "A_A") (pintype "passive"))
      (node (ref "D9") (pin "A") (pinfunction "A_A") (pintype "passive"))
      (node (ref "DSM2") (pin "P$2") (pinfunction "2_P$2") (pintype "bidirectional"))
      (node (ref "E1") (pin "1") (pinfunction "1_1") (pintype "bidirectional"))
      (node (ref "E2") (pin "1") (pinfunction "1_1") (pintype "bidirectional"))
      (node (ref "E3") (pin "1") (pinfunction "1_1") (pintype "bidirectional"))
      (node (ref "E4") (pin "1") (pinfunction "1_1") (pintype "bidirectional"))
      (node (ref "GND") (pin "P$1") (pinfunction "TP_P$1") (pintype "bidirectional"))
      (node (ref "GP0") (pin "1") (pinfunction "1_1") (pintype "bidirectional"))
      (node (ref "GP1") (pin "1") (pinfunction "1_1") (pintype "bidirectional"))
      (node (ref "GPS") (pin "2") (pinfunction "2_2") (pintype "bidirectional"))
      (node (ref "GPS") (pin "6") (pinfunction "6_6") (pintype "bidirectional"))
      (node (ref "H1") (pin "10") (pinfunction "PGND2_10") (pintype "bidirectional"))
      (node (ref "H1") (pin "18") (pinfunction "GND_18") (pintype "bidirectional"))
      (node (ref "H1") (pin "3") (pinfunction "PGND1_3") (pintype "bidirectional"))
      (node (ref "H1") (pin "4") (pinfunction "PGND1_4") (pintype "bidirectional"))
      (node (ref "H1") (pin "9") (pinfunction "PGND2_9") (pintype "bidirectional"))
      (node (ref "H2") (pin "10") (pinfunction "PGND2_10") (pintype "bidirectional"))
      (node (ref "H2") (pin "18") (pinfunction "GND_18") (pintype "bidirectional"))
      (node (ref "H2") (pin "3") (pinfunction "PGND1_3") (pintype "bidirectional"))
      (node (ref "H2") (pin "4") (pinfunction "PGND1_4") (pintype "bidirectional"))
      (node (ref "H2") (pin "9") (pinfunction "PGND2_9") (pintype "bidirectional"))
      (node (ref "I2C") (pin "1") (pinfunction "1_1") (pintype "bidirectional"))
      (node (ref "IMU") (pin "18") (pinfunction "GND_18") (pintype "bidirectional"))
      (node (ref "IMU") (pin "20") (pinfunction "RESV_20") (pintype "bidirectional"))
      (node (ref "IMU") (pin "9") (pinfunction "AD0/SDO_9") (pintype "bidirectional"))
      (node (ref "J2") (pin "P$13") (pinfunction "GND_P$13") (pintype "bidirectional"))
      (node (ref "J2") (pin "P$14") (pinfunction "GND_P$14") (pintype "bidirectional"))
      (node (ref "J2") (pin "P$15") (pinfunction "GND_P$15") (pintype "bidirectional"))
      (node (ref "J2") (pin "P$16") (pinfunction "GND_P$16") (pintype "bidirectional"))
      (node (ref "J2") (pin "P$17") (pinfunction "GND_P$17") (pintype "bidirectional"))
      (node (ref "J2") (pin "P$18") (pinfunction "GND_P$18") (pintype "bidirectional"))
      (node (ref "J2") (pin "P$23") (pinfunction "GND_P$23") (pintype "bidirectional"))
      (node (ref "J2") (pin "P$24") (pinfunction "GND_P$24") (pintype "bidirectional"))
      (node (ref "L4") (pin "1") (pinfunction "1_1") (pintype "passive"))
      (node (ref "MOD") (pin "1") (pinfunction "1_1") (pintype "passive"))
      (node (ref "OSC1") (pin "2") (pinfunction "GND_2") (pintype "bidirectional"))
      (node (ref "PAU") (pin "1") (pinfunction "1_1") (pintype "passive"))
      (node (ref "POW") (pin "1") (pinfunction "1_1") (pintype "passive"))
      (node (ref "PWR") (pin "1") (pinfunction "1_1") (pintype "bidirectional"))
      (node (ref "PWR") (pin "2") (pinfunction "2_2") (pintype "bidirectional"))
      (node (ref "Q1") (pin "5") (pinfunction "D_5") (pintype "passive"))
      (node (ref "Q1") (pin "6") (pinfunction "D_6") (pintype "passive"))
      (node (ref "Q1") (pin "7") (pinfunction "D_7") (pintype "passive"))
      (node (ref "Q1") (pin "8") (pinfunction "D_8") (pintype "passive"))
      (node (ref "R106") (pin "1") (pinfunction "1_1") (pintype "passive"))
      (node (ref "R107") (pin "1") (pinfunction "1_1") (pintype "passive"))
      (node (ref "R108") (pin "2") (pinfunction "2_2") (pintype "passive"))
      (node (ref "R110") (pin "2") (pinfunction "2_2") (pintype "passive"))
      (node (ref "R113") (pin "1") (pinfunction "1_1") (pintype "passive"))
      (node (ref "R115") (pin "1") (pinfunction "1_1") (pintype "passive"))
      (node (ref "R125") (pin "1") (pinfunction "1_1") (pintype "passive"))
      (node (ref "R127") (pin "1") (pinfunction "1_1") (pintype "passive"))
      (node (ref "R129") (pin "1") (pinfunction "1_1") (pintype "passive"))
      (node (ref "R131") (pin "1") (pinfunction "1_1") (pintype "passive"))
      (node (ref "R135") (pin "1") (pinfunction "1_1") (pintype "passive"))
      (node (ref "R14") (pin "2") (pinfunction "2_2") (pintype "passive"))
      (node (ref "R143") (pin "1") (pinfunction "1_1") (pintype "passive"))
      (node (ref "R150") (pin "2") (pinfunction "2_2") (pintype "passive"))
      (node (ref "R158") (pin "2") (pinfunction "2_2") (pintype "passive"))
      (node (ref "R16") (pin "1") (pinfunction "1_1") (pintype "passive"))
      (node (ref "R17") (pin "1") (pinfunction "1_1") (pintype "passive"))
      (node (ref "R21") (pin "2") (pinfunction "2_2") (pintype "passive"))
      (node (ref "R22") (pin "2") (pinfunction "2_2") (pintype "passive"))
      (node (ref "R24") (pin "2") (pinfunction "2_2") (pintype "passive"))
      (node (ref "R25") (pin "2") (pinfunction "2_2") (pintype "passive"))
      (node (ref "R29") (pin "2") (pinfunction "2_2") (pintype "passive"))
      (node (ref "R31") (pin "2") (pinfunction "2_2") (pintype "passive"))
      (node (ref "R32") (pin "2") (pinfunction "2_2") (pintype "passive"))
      (node (ref "R33") (pin "2") (pinfunction "2_2") (pintype "passive"))
      (node (ref "R46") (pin "1") (pinfunction "1_1") (pintype "passive"))
      (node (ref "R47") (pin "1") (pinfunction "1_1") (pintype "passive"))
      (node (ref "R48") (pin "1") (pinfunction "1_1") (pintype "passive"))
      (node (ref "R50") (pin "2") (pinfunction "2_2") (pintype "passive"))
      (node (ref "R51") (pin "2") (pinfunction "2_2") (pintype "passive"))
      (node (ref "R52") (pin "2") (pinfunction "2_2") (pintype "passive"))
      (node (ref "R53") (pin "2") (pinfunction "2_2") (pintype "passive"))
      (node (ref "R59") (pin "1") (pinfunction "1_1") (pintype "passive"))
      (node (ref "R6") (pin "1") (pinfunction "1_1") (pintype "passive"))
      (node (ref "R61") (pin "1") (pinfunction "1_1") (pintype "passive"))
      (node (ref "R62") (pin "1") (pinfunction "1_1") (pintype "passive"))
      (node (ref "R63") (pin "1") (pinfunction "1_1") (pintype "passive"))
      (node (ref "R64") (pin "1") (pinfunction "1_1") (pintype "passive"))
      (node (ref "R8") (pin "2") (pinfunction "2_2") (pintype "passive"))
      (node (ref "R87") (pin "2") (pinfunction "2_2") (pintype "passive"))
      (node (ref "R88") (pin "2") (pinfunction "2_2") (pintype "passive"))
      (node (ref "R89") (pin "2") (pinfunction "2_2") (pintype "passive"))
      (node (ref "R91") (pin "2") (pinfunction "2_2") (pintype "passive"))
      (node (ref "R95") (pin "1") (pinfunction "1_1") (pintype "passive"))
      (node (ref "RST") (pin "1") (pinfunction "1_1") (pintype "passive"))
      (node (ref "S1.1") (pin "1") (pinfunction "1_1") (pintype "bidirectional"))
      (node (ref "S1.2") (pin "1") (pinfunction "1_1") (pintype "bidirectional"))
      (node (ref "SD") (pin "1") (pinfunction "1_1") (pintype "passive"))
      (node (ref "SIP") (pin "A1") (pinfunction "DGND1_A1") (pintype "bidirectional"))
      (node (ref "SIP") (pin "A18") (pinfunction "DGND2_A18") (pintype "bidirectional"))
      (node (ref "SIP") (pin "E19") (pinfunction "DGND3_E19") (pintype "bidirectional"))
      (node (ref "SIP") (pin "E20") (pinfunction "DGND4_E20") (pintype "bidirectional"))
      (node (ref "SIP") (pin "F19") (pinfunction "DGND6_F19") (pintype "bidirectional"))
      (node (ref "SIP") (pin "F8") (pinfunction "DGND5_F8") (pintype "bidirectional"))
      (node (ref "SIP") (pin "G11") (pinfunction "DGND9_G11") (pintype "bidirectional"))
      (node (ref "SIP") (pin "G12") (pinfunction "DGND10_G12") (pintype "bidirectional"))
      (node (ref "SIP") (pin "G19") (pinfunction "DGND11_G19") (pintype "bidirectional"))
      (node (ref "SIP") (pin "G8") (pinfunction "DGND7_G8") (pintype "bidirectional"))
      (node (ref "SIP") (pin "G9") (pinfunction "DGND8_G9") (pintype "bidirectional"))
      (node (ref "SIP") (pin "H10") (pinfunction "DGND16_H10") (pintype "bidirectional"))
      (node (ref "SIP") (pin "H12") (pinfunction "DGND17_H12") (pintype "bidirectional"))
      (node (ref "SIP") (pin "H19") (pinfunction "DGND18_H19") (pintype "bidirectional"))
      (node (ref "SIP") (pin "H6") (pinfunction "DGND12_H6") (pintype "bidirectional"))
      (node (ref "SIP") (pin "H7") (pinfunction "DGND13_H7") (pintype "bidirectional"))
      (node (ref "SIP") (pin "H8") (pinfunction "DGND14_H8") (pintype "bidirectional"))
      (node (ref "SIP") (pin "H9") (pinfunction "DGND15_H9") (pintype "bidirectional"))
      (node (ref "SIP") (pin "J10") (pinfunction "DGND23_J10") (pintype "bidirectional"))
      (node (ref "SIP") (pin "J11") (pinfunction "DGND24_J11") (pintype "bidirectional"))
      (node (ref "SIP") (pin "J19") (pinfunction "DGND25_J19") (pintype "bidirectional"))
      (node (ref "SIP") (pin "J20") (pinfunction "DGND26_J20") (pintype "bidirectional"))
      (node (ref "SIP") (pin "J6") (pinfunction "DGND19_J6") (pintype "bidirectional"))
      (node (ref "SIP") (pin "J7") (pinfunction "DGND20_J7") (pintype "bidirectional"))
      (node (ref "SIP") (pin "J8") (pinfunction "DGND21_J8") (pintype "bidirectional"))
      (node (ref "SIP") (pin "J9") (pinfunction "DGND22_J9") (pintype "bidirectional"))
      (node (ref "SIP") (pin "K10") (pinfunction "DGND29_K10") (pintype "bidirectional"))
      (node (ref "SIP") (pin "K11") (pinfunction "DGND30_K11") (pintype "bidirectional"))
      (node (ref "SIP") (pin "K19") (pinfunction "DGND31_K19") (pintype "bidirectional"))
      (node (ref "SIP") (pin "K7") (pinfunction "DGND27_K7") (pintype "bidirectional"))
      (node (ref "SIP") (pin "K9") (pinfunction "DGND28_K9") (pintype "bidirectional"))
      (node (ref "SIP") (pin "L10") (pinfunction "DGND32_L10") (pintype "bidirectional"))
      (node (ref "SIP") (pin "L11") (pinfunction "DGND33_L11") (pintype "bidirectional"))
      (node (ref "SIP") (pin "L12") (pinfunction "DGND34_L12") (pintype "bidirectional"))
      (node (ref "SIP") (pin "L13") (pinfunction "DGND35_L13") (pintype "bidirectional"))
      (node (ref "SIP") (pin "L19") (pinfunction "DGND36_L19") (pintype "bidirectional"))
      (node (ref "SIP") (pin "M10") (pinfunction "DGND42_M10") (pintype "bidirectional"))
      (node (ref "SIP") (pin "M12") (pinfunction "DGND43_M12") (pintype "bidirectional"))
      (node (ref "SIP") (pin "M14") (pinfunction "DGND44_M14") (pintype "bidirectional"))
      (node (ref "SIP") (pin "M19") (pinfunction "DGND45_M19") (pintype "bidirectional"))
      (node (ref "SIP") (pin "M6") (pinfunction "DGND38_M6") (pintype "bidirectional"))
      (node (ref "SIP") (pin "M7") (pinfunction "DGND39_M7") (pintype "bidirectional"))
      (node (ref "SIP") (pin "M8") (pinfunction "DGND40_M8") (pintype "bidirectional"))
      (node (ref "SIP") (pin "M9") (pinfunction "DGND41_M9") (pintype "bidirectional"))
      (node (ref "SIP") (pin "N10") (pinfunction "DGND47_N10") (pintype "bidirectional"))
      (node (ref "SIP") (pin "N11") (pinfunction "DGND48_N11") (pintype "bidirectional"))
      (node (ref "SIP") (pin "N14") (pinfunction "DGND49_N14") (pintype "bidirectional"))
      (node (ref "SIP") (pin "N19") (pinfunction "DGND50_N19") (pintype "bidirectional"))
      (node (ref "SIP") (pin "N20") (pinfunction "DGND51_N20") (pintype "bidirectional"))
      (node (ref "SIP") (pin "N7") (pinfunction "DGND46_N7") (pintype "bidirectional"))
      (node (ref "SIP") (pin "P19") (pinfunction "DGND52_P19") (pintype "bidirectional"))
      (node (ref "SIP") (pin "P20") (pinfunction "DGND53_P20") (pintype "bidirectional"))
      (node (ref "SIP") (pin "R19") (pinfunction "DGND54_R19") (pintype "bidirectional"))
      (node (ref "SIP") (pin "R20") (pinfunction "DGND55_R20") (pintype "bidirectional"))
      (node (ref "SIP") (pin "T19") (pinfunction "DGND56_T19") (pintype "bidirectional"))
      (node (ref "SIP") (pin "T20") (pinfunction "DGND57_T20") (pintype "bidirectional"))
      (node (ref "SIP") (pin "U19") (pinfunction "DGND58_U19") (pintype "bidirectional"))
      (node (ref "SIP") (pin "V1") (pinfunction "DGND59_V1") (pintype "bidirectional"))
      (node (ref "SIP") (pin "V18") (pinfunction "DGND60_V18") (pintype "bidirectional"))
      (node (ref "SIP") (pin "V19") (pinfunction "DGND61_V19") (pintype "bidirectional"))
      (node (ref "SIP") (pin "W10") (pinfunction "DGND70_W10") (pintype "bidirectional"))
      (node (ref "SIP") (pin "W11") (pinfunction "DGND71_W11") (pintype "bidirectional"))
      (node (ref "SIP") (pin "W12") (pinfunction "DGND72_W12") (pintype "bidirectional"))
      (node (ref "SIP") (pin "W13") (pinfunction "DGND73_W13") (pintype "bidirectional"))
      (node (ref "SIP") (pin "W14") (pinfunction "DGND74_W14") (pintype "bidirectional"))
      (node (ref "SIP") (pin "W15") (pinfunction "DGND75_W15") (pintype "bidirectional"))
      (node (ref "SIP") (pin "W16") (pinfunction "DGND76_W16") (pintype "bidirectional"))
      (node (ref "SIP") (pin "W17") (pinfunction "DGND77_W17") (pintype "bidirectional"))
      (node (ref "SIP") (pin "W18") (pinfunction "DGND78_W18") (pintype "bidirectional"))
      (node (ref "SIP") (pin "W19") (pinfunction "DGND79_W19") (pintype "bidirectional"))
      (node (ref "SIP") (pin "W2") (pinfunction "DGND62_W2") (pintype "bidirectional"))
      (node (ref "SIP") (pin "W20") (pinfunction "DGND80_W20") (pintype "bidirectional"))
      (node (ref "SIP") (pin "W3") (pinfunction "DGND63_W3") (pintype "bidirectional"))
      (node (ref "SIP") (pin "W5") (pinfunction "DGND65_W5") (pintype "bidirectional"))
      (node (ref "SIP") (pin "W6") (pinfunction "DGND66_W6") (pintype "bidirectional"))
      (node (ref "SIP") (pin "W7") (pinfunction "DGND67_W7") (pintype "bidirectional"))
      (node (ref "SIP") (pin "W8") (pinfunction "DGND68_W8") (pintype "bidirectional"))
      (node (ref "SIP") (pin "W9") (pinfunction "DGND69_W9") (pintype "bidirectional"))
      (node (ref "SIP") (pin "Y10") (pinfunction "DGND83_Y10") (pintype "bidirectional"))
      (node (ref "SIP") (pin "Y12") (pinfunction "DGND84_Y12") (pintype "bidirectional"))
      (node (ref "SIP") (pin "Y15") (pinfunction "DGND85_Y15") (pintype "bidirectional"))
      (node (ref "SIP") (pin "Y18") (pinfunction "DGND86_Y18") (pintype "bidirectional"))
      (node (ref "SIP") (pin "Y7") (pinfunction "DGND82_Y7") (pintype "bidirectional"))
      (node (ref "TP12") (pin "TP") (pinfunction "TP_TP") (pintype "input"))
      (node (ref "U1") (pin "2") (pinfunction "GND_2") (pintype "power_in"))
      (node (ref "U10") (pin "11") (pinfunction "GND_11") (pintype "bidirectional"))
      (node (ref "U10") (pin "TP") (pinfunction "TP_TP") (pintype "bidirectional"))
      (node (ref "U13") (pin "C4") (pinfunction "VSSQ1_C4") (pintype "bidirectional"))
      (node (ref "U13") (pin "E7") (pinfunction "VSS1_E7") (pintype "bidirectional"))
      (node (ref "U13") (pin "G5") (pinfunction "VSS2_G5") (pintype "bidirectional"))
      (node (ref "U13") (pin "H10") (pinfunction "VSS3_H10") (pintype "bidirectional"))
      (node (ref "U13") (pin "K8") (pinfunction "VSS4_K8") (pintype "bidirectional"))
      (node (ref "U13") (pin "N2") (pinfunction "VSSQ2_N2") (pintype "bidirectional"))
      (node (ref "U13") (pin "N5") (pinfunction "VSSQ3_N5") (pintype "bidirectional"))
      (node (ref "U13") (pin "P4") (pinfunction "VSSQ4_P4") (pintype "bidirectional"))
      (node (ref "U13") (pin "P6") (pinfunction "VSSQ5_P6") (pintype "bidirectional"))
      (node (ref "U2") (pin "3") (pinfunction "GND_3") (pintype "power_in"))
      (node (ref "U3") (pin "4") (pinfunction "GND_4") (pintype "bidirectional"))
      (node (ref "U4") (pin "4") (pinfunction "GND_4") (pintype "bidirectional"))
      (node (ref "U5") (pin "2") (pinfunction "VSS_2") (pintype "passive"))
      (node (ref "U6") (pin "3") (pinfunction "GND_3") (pintype "power_in"))
      (node (ref "U7") (pin "1") (pinfunction "GND1_1") (pintype "bidirectional"))
      (node (ref "U7") (pin "15") (pinfunction "GND4_15") (pintype "bidirectional"))
      (node (ref "U7") (pin "16") (pinfunction "GND5_16") (pintype "bidirectional"))
      (node (ref "U7") (pin "17") (pinfunction "GND6_17") (pintype "bidirectional"))
      (node (ref "U7") (pin "19") (pinfunction "GND7_19") (pintype "bidirectional"))
      (node (ref "U7") (pin "20") (pinfunction "GND8_20") (pintype "bidirectional"))
      (node (ref "U7") (pin "23") (pinfunction "GND9_23") (pintype "bidirectional"))
      (node (ref "U7") (pin "24") (pinfunction "GND10_24") (pintype "bidirectional"))
      (node (ref "U7") (pin "28") (pinfunction "GND11_28") (pintype "bidirectional"))
      (node (ref "U7") (pin "29") (pinfunction "GND12_29") (pintype "bidirectional"))
      (node (ref "U7") (pin "30") (pinfunction "GND13_30") (pintype "bidirectional"))
      (node (ref "U7") (pin "31") (pinfunction "GND14_31") (pintype "bidirectional"))
      (node (ref "U7") (pin "33") (pinfunction "GND15_33") (pintype "bidirectional"))
      (node (ref "U7") (pin "34") (pinfunction "GND16_34") (pintype "bidirectional"))
      (node (ref "U7") (pin "35") (pinfunction "GND17_35") (pintype "bidirectional"))
      (node (ref "U7") (pin "37") (pinfunction "GND18_37") (pintype "bidirectional"))
      (node (ref "U7") (pin "39") (pinfunction "GND19_39") (pintype "bidirectional"))
      (node (ref "U7") (pin "44") (pinfunction "GND20_44") (pintype "bidirectional"))
      (node (ref "U7") (pin "45") (pinfunction "GND21_45") (pintype "bidirectional"))
      (node (ref "U7") (pin "48") (pinfunction "GND22_48") (pintype "bidirectional"))
      (node (ref "U7") (pin "49") (pinfunction "GND23_49") (pintype "bidirectional"))
      (node (ref "U7") (pin "54") (pinfunction "GND24_54") (pintype "bidirectional"))
      (node (ref "U7") (pin "55") (pinfunction "GND25_55") (pintype "bidirectional"))
      (node (ref "U7") (pin "59") (pinfunction "GND26_59") (pintype "bidirectional"))
      (node (ref "U7") (pin "61") (pinfunction "GND27_61") (pintype "bidirectional"))
      (node (ref "U7") (pin "63") (pinfunction "GND28_63") (pintype "bidirectional"))
      (node (ref "U7") (pin "64") (pinfunction "GND29_64") (pintype "bidirectional"))
      (node (ref "U7") (pin "7") (pinfunction "GND2_7") (pintype "bidirectional"))
      (node (ref "U7") (pin "9") (pinfunction "GND3_9") (pintype "bidirectional"))
      (node (ref "U7") (pin "G1") (pinfunction "G1_G1") (pintype "bidirectional"))
      (node (ref "U7") (pin "G10") (pinfunction "G10_G10") (pintype "bidirectional"))
      (node (ref "U7") (pin "G11") (pinfunction "G11_G11") (pintype "bidirectional"))
      (node (ref "U7") (pin "G12") (pinfunction "G12_G12") (pintype "bidirectional"))
      (node (ref "U7") (pin "G13") (pinfunction "G13_G13") (pintype "bidirectional"))
      (node (ref "U7") (pin "G14") (pinfunction "G14_G14") (pintype "bidirectional"))
      (node (ref "U7") (pin "G15") (pinfunction "G15_G15") (pintype "bidirectional"))
      (node (ref "U7") (pin "G16") (pinfunction "G16_G16") (pintype "bidirectional"))
      (node (ref "U7") (pin "G17") (pinfunction "G17_G17") (pintype "bidirectional"))
      (node (ref "U7") (pin "G18") (pinfunction "G18_G18") (pintype "bidirectional"))
      (node (ref "U7") (pin "G19") (pinfunction "G19_G19") (pintype "bidirectional"))
      (node (ref "U7") (pin "G2") (pinfunction "G2_G2") (pintype "bidirectional"))
      (node (ref "U7") (pin "G20") (pinfunction "G20_G20") (pintype "bidirectional"))
      (node (ref "U7") (pin "G21") (pinfunction "G21_G21") (pintype "bidirectional"))
      (node (ref "U7") (pin "G22") (pinfunction "G22_G22") (pintype "bidirectional"))
      (node (ref "U7") (pin "G23") (pinfunction "G23_G23") (pintype "bidirectional"))
      (node (ref "U7") (pin "G24") (pinfunction "G24_G24") (pintype "bidirectional"))
      (node (ref "U7") (pin "G25") (pinfunction "G25_G25") (pintype "bidirectional"))
      (node (ref "U7") (pin "G26") (pinfunction "G26_G26") (pintype "bidirectional"))
      (node (ref "U7") (pin "G27") (pinfunction "G27_G27") (pintype "bidirectional"))
      (node (ref "U7") (pin "G28") (pinfunction "G28_G28") (pintype "bidirectional"))
      (node (ref "U7") (pin "G29") (pinfunction "G29_G29") (pintype "bidirectional"))
      (node (ref "U7") (pin "G3") (pinfunction "G3_G3") (pintype "bidirectional"))
      (node (ref "U7") (pin "G30") (pinfunction "G30_G30") (pintype "bidirectional"))
      (node (ref "U7") (pin "G31") (pinfunction "G31_G31") (pintype "bidirectional"))
      (node (ref "U7") (pin "G32") (pinfunction "G32_G32") (pintype "bidirectional"))
      (node (ref "U7") (pin "G33") (pinfunction "G33_G33") (pintype "bidirectional"))
      (node (ref "U7") (pin "G34") (pinfunction "G34_G34") (pintype "bidirectional"))
      (node (ref "U7") (pin "G35") (pinfunction "G35_G35") (pintype "bidirectional"))
      (node (ref "U7") (pin "G36") (pinfunction "G36_G36") (pintype "bidirectional"))
      (node (ref "U7") (pin "G4") (pinfunction "G4_G4") (pintype "bidirectional"))
      (node (ref "U7") (pin "G5") (pinfunction "G5_G5") (pintype "bidirectional"))
      (node (ref "U7") (pin "G6") (pinfunction "G6_G6") (pintype "bidirectional"))
      (node (ref "U7") (pin "G7") (pinfunction "G7_G7") (pintype "bidirectional"))
      (node (ref "U7") (pin "G8") (pinfunction "G8_G8") (pintype "bidirectional"))
      (node (ref "U7") (pin "G9") (pinfunction "G9_G9") (pintype "bidirectional"))
      (node (ref "U8") (pin "2") (pinfunction "GND_2") (pintype "power_in"))
      (node (ref "U9") (pin "11") (pinfunction "GND_11") (pintype "bidirectional"))
      (node (ref "U9") (pin "TP") (pinfunction "TP_TP") (pintype "bidirectional"))
      (node (ref "UT0") (pin "1") (pinfunction "1_1") (pintype "bidirectional"))
      (node (ref "UT1") (pin "1") (pinfunction "1_1") (pintype "bidirectional"))
      (node (ref "UT5") (pin "1") (pinfunction "1_1") (pintype "bidirectional"))
      (node (ref "X2") (pin "6") (pinfunction "VSS_6") (pintype "bidirectional"))
      (node (ref "X2") (pin "GND") (pinfunction "GND_GND") (pintype "bidirectional"))
      (node (ref "X4") (pin "GND") (pinfunction "GND_GND") (pintype "input"))
    )
    (net (code "40") (name "GNDA_ADC") (class "Default")
      (node (ref "C42") (pin "2") (pinfunction "2_2") (pintype "passive"))
      (node (ref "C43") (pin "2") (pinfunction "2_2") (pintype "passive"))
      (node (ref "C44") (pin "2") (pinfunction "2_2") (pintype "passive"))
      (node (ref "SIP") (pin "A6") (pinfunction "VSSA_ADC_0_A6") (pintype "bidirectional"))
      (node (ref "SIP") (pin "A9") (pinfunction "VSSA_ADC_1_A9") (pintype "bidirectional"))
      (node (ref "SIP") (pin "E8") (pinfunction "VSSA_ADC_2_E8") (pintype "bidirectional"))
    )
    (net (code "41") (name "GPIO1_17") (class "Default")
      (node (ref "GP0") (pin "4") (pinfunction "4_4") (pintype "bidirectional"))
      (node (ref "SIP") (pin "V14") (pinfunction "GPIO1_17_V14_V14") (pintype "bidirectional"))
    )
    (net (code "42") (name "GPIO1_25") (class "Default")
      (node (ref "GP0") (pin "3") (pinfunction "3_3") (pintype "bidirectional"))
      (node (ref "SIP") (pin "U16") (pinfunction "HDMIINT_GPIO1_25_U16_U16") (pintype "bidirectional"))
    )
    (net (code "43") (name "GPIO3_1") (class "Default")
      (node (ref "GP1") (pin "4") (pinfunction "4_4") (pintype "bidirectional"))
      (node (ref "SIP") (pin "H17") (pinfunction "H17_H17") (pintype "bidirectional"))
    )
    (net (code "44") (name "GPIO3_2") (class "Default")
      (node (ref "GP1") (pin "3") (pinfunction "3_3") (pintype "bidirectional"))
      (node (ref "SIP") (pin "J15") (pinfunction "J15_J15") (pintype "bidirectional"))
    )
    (net (code "45") (name "GPIO3_17") (class "Default")
      (node (ref "GP0") (pin "6") (pinfunction "6_6") (pintype "bidirectional"))
      (node (ref "SIP") (pin "C12") (pinfunction "SPI1_CS0_C12_C12") (pintype "bidirectional"))
    )
    (net (code "46") (name "GPIO3_20") (class "Default")
      (node (ref "GP0") (pin "5") (pinfunction "5_5") (pintype "bidirectional"))
      (node (ref "SIP") (pin "D13") (pinfunction "GPIO3_20_D13_D13") (pintype "bidirectional"))
    )
    (net (code "47") (name "I2C0_SCL") (class "Default")
      (node (ref "R23") (pin "1") (pinfunction "1_1") (pintype "passive"))
      (node (ref "SIP") (pin "C16") (pinfunction "I2C0_SCL_C16") (pintype "bidirectional"))
      (node (ref "SIP") (pin "C20") (pinfunction "PMIC_I2C_SCL_C20") (pintype "bidirectional"))
      (node (ref "U5") (pin "1") (pinfunction "SCL_1") (pintype "input"))
    )
    (net (code "48") (name "I2C0_SDA") (class "Default")
      (node (ref "R2") (pin "1") (pinfunction "1_1") (pintype "passive"))
      (node (ref "SIP") (pin "C17") (pinfunction "I2C0_SDA_C17") (pintype "bidirectional"))
      (node (ref "SIP") (pin "C19") (pinfunction "PMIC_I2C_SDA_C19") (pintype "bidirectional"))
      (node (ref "U5") (pin "3") (pinfunction "SDA_3") (pintype "bidirectional"))
    )
    (net (code "49") (name "I2C1_SCL") (class "Default")
      (node (ref "I2C") (pin "3") (pinfunction "3_3") (pintype "bidirectional"))
      (node (ref "R12") (pin "1") (pinfunction "1_1") (pintype "passive"))
      (node (ref "SIP") (pin "A16") (pinfunction "I2C1_SCL_A16_A16") (pintype "bidirectional"))
    )
    (net (code "50") (name "I2C1_SDA") (class "Default")
      (node (ref "I2C") (pin "4") (pinfunction "4_4") (pintype "bidirectional"))
      (node (ref "R13") (pin "2") (pinfunction "2_2") (pintype "passive"))
      (node (ref "SIP") (pin "B16") (pinfunction "I2C1_SDA_B16_B16") (pintype "bidirectional"))
    )
    (net (code "51") (name "I2C2_SCL") (class "Default")
      (node (ref "BMP") (pin "4") (pinfunction "SCK_4") (pintype "input"))
      (node (ref "IMU") (pin "23") (pinfunction "SCL/SCLK_23") (pintype "bidirectional"))
      (node (ref "R11") (pin "1") (pinfunction "1_1") (pintype "passive"))
      (node (ref "SIP") (pin "D17") (pinfunction "I2C2_SCL_D17_D17") (pintype "bidirectional"))
    )
    (net (code "52") (name "I2C2_SDA") (class "Default")
      (node (ref "BMP") (pin "3") (pinfunction "SDI_3") (pintype "bidirectional"))
      (node (ref "IMU") (pin "24") (pinfunction "SDA/SDI_24") (pintype "bidirectional"))
      (node (ref "R10") (pin "2") (pinfunction "2_2") (pintype "passive"))
      (node (ref "SIP") (pin "D18") (pinfunction "I2C2_SDA_D18_D18") (pintype "bidirectional"))
    )
    (net (code "53") (name "IMU_INT") (class "Default")
      (node (ref "IMU") (pin "12") (pinfunction "INT_12") (pintype "bidirectional"))
      (node (ref "SIP") (pin "A14") (pinfunction "GPIO3_21_A14_A14") (pintype "bidirectional"))
    )
    (net (code "54") (name "LDO_PGOOD") (class "Default")
      (node (ref "SIP") (pin "B20") (pinfunction "PMIC_OUT_LDO_PGOOD_B20") (pintype "output"))
      (node (ref "SIP") (pin "B5") (pinfunction "RTC_PWRONRSTN_B5") (pintype "bidirectional"))
    )
    (net (code "55") (name "LED_GRN") (class "Default")
      (node (ref "G") (pin "A") (pinfunction "A_A") (pintype "passive"))
      (node (ref "GP1") (pin "6") (pinfunction "6_6") (pintype "bidirectional"))
      (node (ref "SIP") (pin "T7") (pinfunction "TIMER7_T7_T7") (pintype "bidirectional"))
    )
    (net (code "56") (name "LED_RED") (class "Default")
      (node (ref "GP1") (pin "5") (pinfunction "5_5") (pintype "bidirectional"))
      (node (ref "R") (pin "A") (pinfunction "A_A") (pintype "passive"))
      (node (ref "SIP") (pin "R7") (pinfunction "TIMER4_R7_R7") (pintype "bidirectional"))
    )
    (net (code "57") (name "MCASP0_ACLKR") (class "Default")
      (node (ref "SIP") (pin "U18") (pinfunction "GPIO1_28_U18_U18") (pintype "bidirectional"))
      (node (ref "U10") (pin "20") (pinfunction "B1_20") (pintype "bidirectional"))
    )
    (net (code "58") (name "MCASP0_AXR0") (class "Default")
      (node (ref "SIP") (pin "T16") (pinfunction "USB1OC_GPIO1_26_T16_T16") (pintype "bidirectional"))
      (node (ref "U10") (pin "17") (pinfunction "B3_17") (pintype "bidirectional"))
    )
    (net (code "59") (name "MCASP0_AXR1") (class "Default")
      (node (ref "SIP") (pin "V17") (pinfunction "HDMIDIS_GPIO1_27_V17_V17") (pintype "bidirectional"))
      (node (ref "U10") (pin "16") (pinfunction "B4_16") (pintype "bidirectional"))
    )
    (net (code "60") (name "MCASP0_FSR") (class "Default")
      (node (ref "SIP") (pin "V12") (pinfunction "GPIO2_1_V12_V12") (pintype "bidirectional"))
      (node (ref "U10") (pin "18") (pinfunction "B2_18") (pintype "bidirectional"))
    )
    (net (code "61") (name "MDIR_1A") (class "Default")
      (node (ref "H1") (pin "21") (pinfunction "AIN1_21") (pintype "bidirectional"))
      (node (ref "SIP") (pin "T13") (pinfunction "GPIO2_0_T13_T13") (pintype "bidirectional"))
    )
    (net (code "62") (name "MDIR_1B") (class "Default")
      (node (ref "H1") (pin "22") (pinfunction "AIN2_22") (pintype "bidirectional"))
      (node (ref "SIP") (pin "U17") (pinfunction "UART4_TXD_U17_U17") (pintype "bidirectional"))
    )
    (net (code "63") (name "MDIR_2A") (class "Default")
      (node (ref "H1") (pin "17") (pinfunction "BIN1_17") (pintype "bidirectional"))
      (node (ref "SIP") (pin "R13") (pinfunction "GPIO1_16_R13_R13") (pintype "bidirectional"))
    )
    (net (code "64") (name "MDIR_2B") (class "Default")
      (node (ref "H1") (pin "16") (pinfunction "BIN2_16") (pintype "bidirectional"))
      (node (ref "R140") (pin "1") (pinfunction "1_1") (pintype "passive"))
      (node (ref "SIP") (pin "V4") (pinfunction "LCD_DATA14_V4_V4") (pintype "bidirectional"))
    )
    (net (code "65") (name "MDIR_3A") (class "Default")
      (node (ref "H2") (pin "21") (pinfunction "AIN1_21") (pintype "bidirectional"))
      (node (ref "R118") (pin "1") (pinfunction "1_1") (pintype "passive"))
      (node (ref "SIP") (pin "R4") (pinfunction "LCD_DATA3_R4_R4") (pintype "bidirectional"))
    )
    (net (code "66") (name "MDIR_3B") (class "Default")
      (node (ref "H2") (pin "22") (pinfunction "AIN2_22") (pintype "bidirectional"))
      (node (ref "R116") (pin "1") (pinfunction "1_1") (pintype "passive"))
      (node (ref "R77") (pin "1") (pinfunction "1_1") (pintype "passive"))
      (node (ref "SIP") (pin "R3") (pinfunction "LCD_DATA2_R3_R3") (pintype "bidirectional"))
    )
    (net (code "67") (name "MDIR_4A") (class "Default")
      (node (ref "H2") (pin "17") (pinfunction "BIN1_17") (pintype "bidirectional"))
      (node (ref "R113") (pin "2") (pinfunction "2_2") (pintype "passive"))
      (node (ref "SIP") (pin "R1") (pinfunction "LCD_DATA0_R1_R1") (pintype "bidirectional"))
    )
    (net (code "68") (name "MDIR_4B") (class "Default")
      (node (ref "H2") (pin "16") (pinfunction "BIN2_16") (pintype "bidirectional"))
      (node (ref "R115") (pin "2") (pinfunction "2_2") (pintype "passive"))
      (node (ref "SIP") (pin "R2") (pinfunction "LCD_DATA1_R2_R2") (pintype "bidirectional"))
    )
    (net (code "69") (name "MMC1_CLK") (class "Default")
      (node (ref "R15") (pin "2") (pinfunction "2_2") (pintype "passive"))
      (node (ref "R66") (pin "1") (pinfunction "1_1") (pintype "passive"))
      (node (ref "U13") (pin "M6") (pinfunction "CLK_M6") (pintype "bidirectional"))
    )
    (net (code "70") (name "MMC1_CMD") (class "Default")
      (node (ref "R67") (pin "1") (pinfunction "1_1") (pintype "passive"))
      (node (ref "SIP") (pin "V9") (pinfunction "MMC1_CMD_V9_V9") (pintype "bidirectional"))
      (node (ref "U13") (pin "M5") (pinfunction "CMD_M5") (pintype "bidirectional"))
    )
    (net (code "71") (name "MMC1_DAT0") (class "Default")
      (node (ref "R68") (pin "1") (pinfunction "1_1") (pintype "passive"))
      (node (ref "SIP") (pin "U7") (pinfunction "MMC1_DAT0_U7_U7") (pintype "bidirectional"))
      (node (ref "U13") (pin "A3") (pinfunction "DAT0_A3") (pintype "bidirectional"))
    )
    (net (code "72") (name "MMC1_DAT1") (class "Default")
      (node (ref "R69") (pin "1") (pinfunction "1_1") (pintype "passive"))
      (node (ref "SIP") (pin "V7") (pinfunction "MMC1_DAT1_V7_V7") (pintype "bidirectional"))
      (node (ref "U13") (pin "A4") (pinfunction "DAT1_A4") (pintype "bidirectional"))
    )
    (net (code "73") (name "MMC1_DAT2") (class "Default")
      (node (ref "R70") (pin "1") (pinfunction "1_1") (pintype "passive"))
      (node (ref "SIP") (pin "R8") (pinfunction "MMC1_DAT2_R8_R8") (pintype "bidirectional"))
      (node (ref "U13") (pin "A5") (pinfunction "DAT2_A5") (pintype "bidirectional"))
    )
    (net (code "74") (name "MMC1_DAT3") (class "Default")
      (node (ref "R71") (pin "1") (pinfunction "1_1") (pintype "passive"))
      (node (ref "SIP") (pin "T8") (pinfunction "MMC1_DAT3_T8_T8") (pintype "bidirectional"))
      (node (ref "U13") (pin "B2") (pinfunction "DAT3_B2") (pintype "bidirectional"))
    )
    (net (code "75") (name "MMC1_DAT4") (class "Default")
      (node (ref "R72") (pin "1") (pinfunction "1_1") (pintype "passive"))
      (node (ref "SIP") (pin "U8") (pinfunction "MMC1_DAT4_U8_U8") (pintype "bidirectional"))
      (node (ref "U13") (pin "B3") (pinfunction "DAT4_B3") (pintype "bidirectional"))
    )
    (net (code "76") (name "MMC1_DAT5") (class "Default")
      (node (ref "R73") (pin "1") (pinfunction "1_1") (pintype "passive"))
      (node (ref "SIP") (pin "V8") (pinfunction "MMC1_DAT5_V8_V8") (pintype "bidirectional"))
      (node (ref "U13") (pin "B4") (pinfunction "DAT5_B4") (pintype "bidirectional"))
    )
    (net (code "77") (name "MMC1_DAT6") (class "Default")
      (node (ref "R74") (pin "1") (pinfunction "1_1") (pintype "passive"))
      (node (ref "SIP") (pin "R9") (pinfunction "MMC1_DAT6_R9_R9") (pintype "bidirectional"))
      (node (ref "U13") (pin "B5") (pinfunction "DAT6_B5") (pintype "bidirectional"))
    )
    (net (code "78") (name "MMC1_DAT7") (class "Default")
      (node (ref "R75") (pin "1") (pinfunction "1_1") (pintype "passive"))
      (node (ref "SIP") (pin "T9") (pinfunction "MMC1_DAT7_T9_T9") (pintype "bidirectional"))
      (node (ref "U13") (pin "B6") (pinfunction "DAT7_B6") (pintype "bidirectional"))
    )
    (net (code "79") (name "MMC2_CLK") (class "Default")
      (node (ref "R76") (pin "1") (pinfunction "1_1") (pintype "passive"))
      (node (ref "U9") (pin "13") (pinfunction "B7_13") (pintype "bidirectional"))
    )
    (net (code "80") (name "MMC2_CMD") (class "Default")
      (node (ref "SIP") (pin "J16") (pinfunction "J16_J16") (pintype "bidirectional"))
      (node (ref "U9") (pin "12") (pinfunction "B8_12") (pintype "bidirectional"))
    )
    (net (code "81") (name "MMC2_DAT0") (class "Default")
      (node (ref "SIP") (pin "J17") (pinfunction "J17_J17") (pintype "bidirectional"))
      (node (ref "U9") (pin "14") (pinfunction "B6_14") (pintype "bidirectional"))
    )
    (net (code "82") (name "MMC2_DAT1") (class "Default")
      (node (ref "SIP") (pin "J18") (pinfunction "J18_J18") (pintype "bidirectional"))
      (node (ref "U9") (pin "15") (pinfunction "B5_15") (pintype "bidirectional"))
    )
    (net (code "83") (name "MMC2_DAT2") (class "Default")
      (node (ref "SIP") (pin "K15") (pinfunction "K15_K15") (pintype "bidirectional"))
      (node (ref "U9") (pin "16") (pinfunction "B4_16") (pintype "bidirectional"))
    )
    (net (code "84") (name "MMC2_DAT3") (class "Default")
      (node (ref "SIP") (pin "H16") (pinfunction "H16_H16") (pintype "bidirectional"))
      (node (ref "U9") (pin "17") (pinfunction "B3_17") (pintype "bidirectional"))
    )
    (net (code "85") (name "MODE_BTN") (class "Default")
      (node (ref "MOD") (pin "2") (pinfunction "2_2") (pintype "passive"))
      (node (ref "SIP") (pin "U6") (pinfunction "TIMER6_U6_U6") (pintype "bidirectional"))
    )
    (net (code "86") (name "MOT_STBY") (class "Default")
      (node (ref "H1") (pin "19") (pinfunction "STBY_19") (pintype "bidirectional"))
      (node (ref "H2") (pin "19") (pinfunction "STBY_19") (pintype "bidirectional"))
      (node (ref "SIP") (pin "D14") (pinfunction "GPIO0_20_D14_D14") (pintype "bidirectional"))
    )
    (net (code "87") (name "Net-(0-PadC)") (class "Default")
      (node (ref "0") (pin "C") (pinfunction "C_C") (pintype "passive"))
      (node (ref "R61") (pin "2") (pinfunction "2_2") (pintype "passive"))
    )
    (net (code "88") (name "Net-(1-PadC)") (class "Default")
      (node (ref "1") (pin "C") (pinfunction "C_C") (pintype "passive"))
      (node (ref "R62") (pin "2") (pinfunction "2_2") (pintype "passive"))
    )
    (net (code "89") (name "Net-(2-PadC)") (class "Default")
      (node (ref "2") (pin "C") (pinfunction "C_C") (pintype "passive"))
      (node (ref "R63") (pin "2") (pinfunction "2_2") (pintype "passive"))
    )
    (net (code "90") (name "Net-(3-PadC)") (class "Default")
      (node (ref "3") (pin "C") (pinfunction "C_C") (pintype "passive"))
      (node (ref "R64") (pin "2") (pinfunction "2_2") (pintype "passive"))
    )
    (net (code "91") (name "Net-(5VREG-OUT)") (class "Default")
      (node (ref "5VREG") (pin "2") (pinfunction "OUT_2") (pintype "power_in"))
      (node (ref "D1") (pin "C") (pinfunction "C_C") (pintype "passive"))
      (node (ref "L1") (pin "1") (pinfunction "1_1") (pintype "passive"))
    )
    (net (code "92") (name "Net-(5VREG-VIN)") (class "Default")
      (node (ref "5VREG") (pin "1") (pinfunction "VIN_1") (pintype "input"))
      (node (ref "C3") (pin "1") (pinfunction "1_1") (pintype "passive"))
      (node (ref "D2") (pin "C") (pinfunction "C_C") (pintype "passive"))
      (node (ref "D3") (pin "C") (pinfunction "C_C") (pintype "passive"))
    )
    (net (code "93") (name "Net-(6VREG-BS)") (class "Default")
      (node (ref "6VREG") (pin "2") (pinfunction "BS_2") (pintype "bidirectional"))
      (node (ref "C22") (pin "1") (pinfunction "1_1") (pintype "passive"))
    )
    (net (code "94") (name "Net-(6VREG-COMP)") (class "Default")
      (node (ref "6VREG") (pin "5") (pinfunction "COMP_5") (pintype "bidirectional"))
      (node (ref "R45") (pin "2") (pinfunction "2_2") (pintype "passive"))
    )
    (net (code "95") (name "Net-(6VREG-FB)") (class "Default")
      (node (ref "6VREG") (pin "6") (pinfunction "FB_6") (pintype "bidirectional"))
      (node (ref "R48") (pin "2") (pinfunction "2_2") (pintype "passive"))
      (node (ref "R49") (pin "1") (pinfunction "1_1") (pintype "passive"))
    )
    (net (code "96") (name "Net-(6VREG-FSW)") (class "Default")
      (node (ref "6VREG") (pin "4") (pinfunction "FSW_4") (pintype "bidirectional"))
      (node (ref "R47") (pin "2") (pinfunction "2_2") (pintype "passive"))
    )
    (net (code "97") (name "Net-(6VREG-LX)") (class "Default")
      (node (ref "6VREG") (pin "1") (pinfunction "LX_1") (pintype "bidirectional"))
      (node (ref "C22") (pin "2") (pinfunction "2_2") (pintype "passive"))
      (node (ref "D9") (pin "C") (pinfunction "C_C") (pintype "passive"))
      (node (ref "L3") (pin "1") (pinfunction "1_1") (pintype "passive"))
    )
    (net (code "98") (name "Net-(6VREG-SS)") (class "Default")
      (node (ref "6VREG") (pin "7") (pinfunction "SS_7") (pintype "bidirectional"))
      (node (ref "C21") (pin "2") (pinfunction "2_2") (pintype "passive"))
    )
    (net (code "99") (name "Net-(ANT1-PadSIG)") (class "Default")
      (node (ref "ANT1") (pin "SIG") (pinfunction "SIG_SIG") (pintype "bidirectional"))
      (node (ref "C48") (pin "1") (pinfunction "1_1") (pintype "passive"))
    )
    (net (code "100") (name "Net-(ANT2-PadSIG)") (class "Default")
      (node (ref "ANT2") (pin "SIG") (pinfunction "SIG_SIG") (pintype "bidirectional"))
      (node (ref "C58") (pin "1") (pinfunction "1_1") (pintype "passive"))
    )
    (net (code "101") (name "Net-(B0-PadC)") (class "Default")
      (node (ref "B0") (pin "C") (pinfunction "C_C") (pintype "passive"))
      (node (ref "R31") (pin "1") (pinfunction "1_1") (pintype "passive"))
    )
    (net (code "102") (name "Net-(B1-PadC)") (class "Default")
      (node (ref "B1") (pin "C") (pinfunction "C_C") (pintype "passive"))
      (node (ref "R29") (pin "1") (pinfunction "1_1") (pintype "passive"))
    )
    (net (code "103") (name "Net-(B2-PadC)") (class "Default")
      (node (ref "B2") (pin "C") (pinfunction "C_C") (pintype "passive"))
      (node (ref "R33") (pin "1") (pinfunction "1_1") (pintype "passive"))
    )
    (net (code "104") (name "Net-(B3-PadC)") (class "Default")
      (node (ref "B3") (pin "C") (pinfunction "C_C") (pintype "passive"))
      (node (ref "R32") (pin "1") (pinfunction "1_1") (pintype "passive"))
    )
    (net (code "105") (name "Net-(BAL-CD)") (class "Default")
      (node (ref "BAL") (pin "4") (pinfunction "CD_4") (pintype "bidirectional"))
      (node (ref "C19") (pin "1") (pinfunction "1_1") (pintype "passive"))
    )
    (net (code "106") (name "Net-(BAL-OUT)") (class "Default")
      (node (ref "BAL") (pin "8") (pinfunction "OUT_8") (pintype "bidirectional"))
      (node (ref "R7") (pin "1") (pinfunction "1_1") (pintype "passive"))
    )
    (net (code "107") (name "Net-(BAL-VC1)") (class "Default")
      (node (ref "BAL") (pin "2") (pinfunction "VC1_2") (pintype "bidirectional"))
      (node (ref "C17") (pin "1") (pinfunction "1_1") (pintype "passive"))
      (node (ref "C18") (pin "2") (pinfunction "2_2") (pintype "passive"))
      (node (ref "R30") (pin "2") (pinfunction "2_2") (pintype "passive"))
    )
    (net (code "108") (name "Net-(BAL-VC1_CB)") (class "Default")
      (node (ref "BAL") (pin "3") (pinfunction "VC1_CB_3") (pintype "bidirectional"))
      (node (ref "R27") (pin "2") (pinfunction "2_2") (pintype "passive"))
    )
    (net (code "109") (name "Net-(BAL-VC2)") (class "Default")
      (node (ref "BAL") (pin "1") (pinfunction "VC2_1") (pintype "bidirectional"))
      (node (ref "C17") (pin "2") (pinfunction "2_2") (pintype "passive"))
      (node (ref "R28") (pin "2") (pinfunction "2_2") (pintype "passive"))
    )
    (net (code "110") (name "Net-(BAL-VDD)") (class "Default")
      (node (ref "BAL") (pin "7") (pinfunction "VDD_7") (pintype "bidirectional"))
      (node (ref "C1") (pin "1") (pinfunction "1_1") (pintype "passive"))
      (node (ref "R34") (pin "2") (pinfunction "2_2") (pintype "passive"))
    )
    (net (code "111") (name "Net-(C23-Pad2)") (class "Default")
      (node (ref "C23") (pin "2") (pinfunction "2_2") (pintype "passive"))
      (node (ref "J2") (pin "P$10") (pinfunction "PWR_P$10") (pintype "bidirectional"))
      (node (ref "J2") (pin "P$11") (pinfunction "PWR_P$11") (pintype "bidirectional"))
      (node (ref "J2") (pin "P$12") (pinfunction "PWR_P$12") (pintype "bidirectional"))
      (node (ref "J2") (pin "P$21") (pinfunction "PWR_P$21") (pintype "bidirectional"))
      (node (ref "J2") (pin "P$22") (pinfunction "PWR_P$22") (pintype "bidirectional"))
      (node (ref "J2") (pin "P$7") (pinfunction "PWR_P$7") (pintype "bidirectional"))
      (node (ref "J2") (pin "P$8") (pinfunction "PWR_P$8") (pintype "bidirectional"))
      (node (ref "J2") (pin "P$9") (pinfunction "PWR_P$9") (pintype "bidirectional"))
      (node (ref "L3") (pin "2") (pinfunction "2_2") (pintype "passive"))
      (node (ref "R49") (pin "2") (pinfunction "2_2") (pintype "passive"))
    )
    (net (code "112") (name "Net-(C24-Pad2)") (class "Default")
      (node (ref "C24") (pin "2") (pinfunction "2_2") (pintype "passive"))
      (node (ref "R45") (pin "1") (pinfunction "1_1") (pintype "passive"))
    )
    (net (code "113") (name "Net-(CHG-PadC)") (class "Default")
      (node (ref "CHG") (pin "C") (pinfunction "C_C") (pintype "passive"))
      (node (ref "R3") (pin "2") (pinfunction "2_2") (pintype "passive"))
    )
    (net (code "114") (name "Net-(CHGIC-BST)") (class "Default")
      (node (ref "C14") (pin "1") (pinfunction "1_1") (pintype "passive"))
      (node (ref "CHGIC") (pin "15") (pinfunction "BST_15") (pintype "bidirectional"))
    )
    (net (code "115") (name "Net-(CHGIC-CHGOK)") (class "Default")
      (node (ref "CHGIC") (pin "11") (pinfunction "CHGOK_11") (pintype "bidirectional"))
      (node (ref "R3") (pin "1") (pinfunction "1_1") (pintype "passive"))
    )
    (net (code "116") (name "Net-(CHGIC-CSP)") (class "Default")
      (node (ref "CHGIC") (pin "10") (pinfunction "CSP_10") (pintype "bidirectional"))
      (node (ref "L2") (pin "2") (pinfunction "2_2") (pintype "passive"))
      (node (ref "R4") (pin "2") (pinfunction "2_2") (pintype "passive"))
    )
    (net (code "117") (name "Net-(CHGIC-NTC)") (class "Default")
      (node (ref "CHGIC") (pin "13") (pinfunction "NTC_13") (pintype "bidirectional"))
      (node (ref "R5") (pin "1") (pinfunction "1_1") (pintype "passive"))
      (node (ref "R6") (pin "2") (pinfunction "2_2") (pintype "passive"))
    )
    (net (code "118") (name "Net-(CHGIC-SW)") (class "Default")
      (node (ref "C14") (pin "2") (pinfunction "2_2") (pintype "passive"))
      (node (ref "CHGIC") (pin "1") (pinfunction "SW_1") (pintype "bidirectional"))
      (node (ref "L2") (pin "1") (pinfunction "1_1") (pintype "passive"))
    )
    (net (code "119") (name "Net-(CHGIC-TMR)") (class "Default")
      (node (ref "C10") (pin "2") (pinfunction "2_2") (pintype "passive"))
      (node (ref "CHGIC") (pin "14") (pinfunction "TMR_14") (pintype "bidirectional"))
    )
    (net (code "120") (name "Net-(G-PadC)") (class "Default")
      (node (ref "G") (pin "C") (pinfunction "C_C") (pintype "passive"))
      (node (ref "R22") (pin "1") (pinfunction "1_1") (pintype "passive"))
    )
    (net (code "121") (name "Net-(IMU-REGOUT)") (class "Default")
      (node (ref "C6") (pin "1") (pinfunction "1_1") (pintype "passive"))
      (node (ref "IMU") (pin "10") (pinfunction "REGOUT_10") (pintype "bidirectional"))
    )
    (net (code "122") (name "Net-(J2-1)") (class "Default")
      (node (ref "J2") (pin "P$1") (pinfunction "1_P$1") (pintype "bidirectional"))
      (node (ref "R36") (pin "2") (pinfunction "2_2") (pintype "passive"))
    )
    (net (code "123") (name "Net-(J2-2)") (class "Default")
      (node (ref "J2") (pin "P$2") (pinfunction "2_P$2") (pintype "bidirectional"))
      (node (ref "R37") (pin "2") (pinfunction "2_2") (pintype "passive"))
    )
    (net (code "124") (name "Net-(J2-3)") (class "Default")
      (node (ref "J2") (pin "P$3") (pinfunction "3_P$3") (pintype "bidirectional"))
      (node (ref "R38") (pin "2") (pinfunction "2_2") (pintype "passive"))
    )
    (net (code "125") (name "Net-(J2-4)") (class "Default")
      (node (ref "J2") (pin "P$4") (pinfunction "4_P$4") (pintype "bidirectional"))
      (node (ref "R39") (pin "2") (pinfunction "2_2") (pintype "passive"))
    )
    (net (code "126") (name "Net-(J2-5)") (class "Default")
      (node (ref "J2") (pin "P$5") (pinfunction "5_P$5") (pintype "bidirectional"))
      (node (ref "R40") (pin "2") (pinfunction "2_2") (pintype "passive"))
    )
    (net (code "127") (name "Net-(J2-6)") (class "Default")
      (node (ref "J2") (pin "P$6") (pinfunction "6_P$6") (pintype "bidirectional"))
      (node (ref "R41") (pin "2") (pinfunction "2_2") (pintype "passive"))
    )
    (net (code "128") (name "Net-(J2-7)") (class "Default")
      (node (ref "J2") (pin "P$19") (pinfunction "7_P$19") (pintype "bidirectional"))
      (node (ref "R42") (pin "2") (pinfunction "2_2") (pintype "passive"))
    )
    (net (code "129") (name "Net-(J2-8)") (class "Default")
      (node (ref "J2") (pin "P$20") (pinfunction "8_P$20") (pintype "bidirectional"))
      (node (ref "R43") (pin "2") (pinfunction "2_2") (pintype "passive"))
    )
    (net (code "130") (name "Net-(M1-1)") (class "Default")
      (node (ref "H1") (pin "5") (pinfunction "A02_5") (pintype "bidirectional"))
      (node (ref "H1") (pin "6") (pinfunction "A02_6") (pintype "bidirectional"))
      (node (ref "M1") (pin "P$1") (pinfunction "1_P$1") (pintype "bidirectional"))
    )
    (net (code "131") (name "Net-(M1-2)") (class "Default")
      (node (ref "H1") (pin "1") (pinfunction "A01_1") (pintype "bidirectional"))
      (node (ref "H1") (pin "2") (pinfunction "A01_2") (pintype "bidirectional"))
      (node (ref "M1") (pin "P$2") (pinfunction "2_P$2") (pintype "bidirectional"))
    )
    (net (code "132") (name "Net-(M2-1)") (class "Default")
      (node (ref "H1") (pin "11") (pinfunction "B01_11") (pintype "bidirectional"))
      (node (ref "H1") (pin "12") (pinfunction "B01_12") (pintype "bidirectional"))
      (node (ref "M2") (pin "P$1") (pinfunction "1_P$1") (pintype "bidirectional"))
    )
    (net (code "133") (name "Net-(M2-2)") (class "Default")
      (node (ref "H1") (pin "7") (pinfunction "B02_7") (pintype "bidirectional"))
      (node (ref "H1") (pin "8") (pinfunction "B02_8") (pintype "bidirectional"))
      (node (ref "M2") (pin "P$2") (pinfunction "2_P$2") (pintype "bidirectional"))
    )
    (net (code "134") (name "Net-(M3-1)") (class "Default")
      (node (ref "H2") (pin "1") (pinfunction "A01_1") (pintype "bidirectional"))
      (node (ref "H2") (pin "2") (pinfunction "A01_2") (pintype "bidirectional"))
      (node (ref "M3") (pin "P$1") (pinfunction "1_P$1") (pintype "bidirectional"))
    )
    (net (code "135") (name "Net-(M3-2)") (class "Default")
      (node (ref "H2") (pin "5") (pinfunction "A02_5") (pintype "bidirectional"))
      (node (ref "H2") (pin "6") (pinfunction "A02_6") (pintype "bidirectional"))
      (node (ref "M3") (pin "P$2") (pinfunction "2_P$2") (pintype "bidirectional"))
    )
    (net (code "136") (name "Net-(M4-1)") (class "Default")
      (node (ref "H2") (pin "7") (pinfunction "B02_7") (pintype "bidirectional"))
      (node (ref "H2") (pin "8") (pinfunction "B02_8") (pintype "bidirectional"))
      (node (ref "M4") (pin "P$1") (pinfunction "1_P$1") (pintype "bidirectional"))
    )
    (net (code "137") (name "Net-(M4-2)") (class "Default")
      (node (ref "H2") (pin "11") (pinfunction "B01_11") (pintype "bidirectional"))
      (node (ref "H2") (pin "12") (pinfunction "B01_12") (pintype "bidirectional"))
      (node (ref "M4") (pin "P$2") (pinfunction "2_P$2") (pintype "bidirectional"))
    )
    (net (code "138") (name "Net-(OSC1-EN)") (class "Default")
      (node (ref "OSC1") (pin "1") (pinfunction "EN_1") (pintype "bidirectional"))
      (node (ref "R90") (pin "1") (pinfunction "1_1") (pintype "passive"))
    )
    (net (code "139") (name "Net-(PROT-VDD)") (class "Default")
      (node (ref "C15") (pin "2") (pinfunction "2_2") (pintype "passive"))
      (node (ref "PROT") (pin "5") (pinfunction "VDD_5") (pintype "bidirectional"))
      (node (ref "R44") (pin "2") (pinfunction "2_2") (pintype "passive"))
    )
    (net (code "140") (name "Net-(R-PadC)") (class "Default")
      (node (ref "R") (pin "C") (pinfunction "C_C") (pintype "passive"))
      (node (ref "R21") (pin "1") (pinfunction "1_1") (pintype "passive"))
    )
    (net (code "141") (name "Net-(R76-Pad2)") (class "Default")
      (node (ref "R76") (pin "2") (pinfunction "2_2") (pintype "passive"))
      (node (ref "SIP") (pin "L15") (pinfunction "L15_L15") (pintype "bidirectional"))
    )
    (net (code "142") (name "Net-(R91-Pad1)") (class "Default")
      (node (ref "R91") (pin "1") (pinfunction "1_1") (pintype "passive"))
      (node (ref "WIFI") (pin "C") (pinfunction "C_C") (pintype "passive"))
    )
    (net (code "143") (name "Net-(SIPA-PMIC_IN_PWR_EN)") (class "Default")
      (node (ref "SIP") (pin "C6") (pinfunction "PMIC_POWER_EN_C6") (pintype "output"))
      (node (ref "SIP") (pin "D19") (pinfunction "PMIC_IN_PWR_EN_D19") (pintype "input"))
      (node (ref "TP5") (pin "TP") (pinfunction "TP_TP") (pintype "input"))
    )
    (net (code "144") (name "Net-(SIPB-JTAG_EMU0)") (class "Default")
      (node (ref "EMU1") (pin "TP") (pinfunction "TP_TP") (pintype "input"))
      (node (ref "SIP") (pin "C14") (pinfunction "JTAG_EMU0_C14") (pintype "bidirectional"))
    )
    (net (code "145") (name "Net-(SIPB-JTAG_EMU1)") (class "Default")
      (node (ref "EMU0") (pin "TP") (pinfunction "TP_TP") (pintype "input"))
      (node (ref "SIP") (pin "B14") (pinfunction "JTAG_EMU1_B14") (pintype "bidirectional"))
    )
    (net (code "146") (name "Net-(SIPB-JTAG_TCK)") (class "Default")
      (node (ref "SIP") (pin "A12") (pinfunction "JTAG_TCK_A12") (pintype "bidirectional"))
      (node (ref "TCK") (pin "TP") (pinfunction "TP_TP") (pintype "input"))
    )
    (net (code "147") (name "Net-(SIPB-JTAG_TDI)") (class "Default")
      (node (ref "SIP") (pin "B11") (pinfunction "JTAG_TDI_B11") (pintype "bidirectional"))
      (node (ref "TDI") (pin "TP") (pinfunction "TP_TP") (pintype "input"))
    )
    (net (code "148") (name "Net-(SIPB-JTAG_TDO)") (class "Default")
      (node (ref "SIP") (pin "A11") (pinfunction "JTAG_TDO_A11") (pintype "bidirectional"))
      (node (ref "TDO") (pin "TP") (pinfunction "TP_TP") (pintype "input"))
    )
    (net (code "149") (name "Net-(SIPB-JTAG_TMS)") (class "Default")
      (node (ref "SIP") (pin "C11") (pinfunction "JTAG_TMS_C11") (pintype "bidirectional"))
      (node (ref "TMS") (pin "TP") (pinfunction "TP_TP") (pintype "input"))
    )
    (net (code "150") (name "Net-(SIPB-JTAG_TRSTN)") (class "Default")
      (node (ref "R59") (pin "2") (pinfunction "2_2") (pintype "passive"))
      (node (ref "SIP") (pin "B10") (pinfunction "JTAG_TRSTN_B10") (pintype "bidirectional"))
      (node (ref "TRSTN") (pin "TP") (pinfunction "TP_TP") (pintype "input"))
    )
    (net (code "151") (name "Net-(SIPB-MMC0_CD_C15)") (class "Default")
      (node (ref "R65") (pin "1") (pinfunction "1_1") (pintype "passive"))
      (node (ref "SIP") (pin "C15") (pinfunction "MMC0_CD_C15_C15") (pintype "bidirectional"))
      (node (ref "X2") (pin "CD") (pinfunction "CD#_CD") (pintype "bidirectional"))
    )
    (net (code "152") (name "Net-(SIPB-MMC0_CLK_G17)") (class "Default")
      (node (ref "R57") (pin "1") (pinfunction "1_1") (pintype "passive"))
      (node (ref "SIP") (pin "G17") (pinfunction "MMC0_CLK_G17_G17") (pintype "bidirectional"))
      (node (ref "X2") (pin "5") (pinfunction "CLK_5") (pintype "bidirectional"))
    )
    (net (code "153") (name "Net-(SIPB-MMC0_CMD_G18)") (class "Default")
      (node (ref "R56") (pin "1") (pinfunction "1_1") (pintype "passive"))
      (node (ref "SIP") (pin "G18") (pinfunction "MMC0_CMD_G18_G18") (pintype "bidirectional"))
      (node (ref "X2") (pin "3") (pinfunction "CMD/DI_3") (pintype "bidirectional"))
    )
    (net (code "154") (name "Net-(SIPB-MMC0_DAT0_G16)") (class "Default")
      (node (ref "R55") (pin "1") (pinfunction "1_1") (pintype "passive"))
      (node (ref "SIP") (pin "G16") (pinfunction "MMC0_DAT0_G16_G16") (pintype "bidirectional"))
      (node (ref "X2") (pin "7") (pinfunction "DAT0/DO_7") (pintype "bidirectional"))
    )
    (net (code "155") (name "Net-(SIPB-MMC0_DAT1_G15)") (class "Default")
      (node (ref "R54") (pin "1") (pinfunction "1_1") (pintype "passive"))
      (node (ref "SIP") (pin "G15") (pinfunction "MMC0_DAT1_G15_G15") (pintype "bidirectional"))
      (node (ref "X2") (pin "8") (pinfunction "DAT1_8") (pintype "bidirectional"))
    )
    (net (code "156") (name "Net-(SIPB-MMC0_DAT2_F18)") (class "Default")
      (node (ref "R35") (pin "1") (pinfunction "1_1") (pintype "passive"))
      (node (ref "SIP") (pin "F18") (pinfunction "MMC0_DAT2_F18_F18") (pintype "bidirectional"))
      (node (ref "X2") (pin "1") (pinfunction "DAT2_1") (pintype "bidirectional"))
    )
    (net (code "157") (name "Net-(SIPB-MMC0_DAT3_F17)") (class "Default")
      (node (ref "R26") (pin "1") (pinfunction "1_1") (pintype "passive"))
      (node (ref "SIP") (pin "F17") (pinfunction "MMC0_DAT3_F17_F17") (pintype "bidirectional"))
      (node (ref "X2") (pin "2") (pinfunction "DAT3/CS_2") (pintype "bidirectional"))
    )
    (net (code "158") (name "Net-(SIPB-MMC1_CLK_U9)") (class "Default")
      (node (ref "R15") (pin "1") (pinfunction "1_1") (pintype "passive"))
      (node (ref "SIP") (pin "U9") (pinfunction "MMC1_CLK_U9_U9") (pintype "bidirectional"))
    )
    (net (code "159") (name "Net-(SIPB-OSC0_GND)") (class "Default")
      (node (ref "C29") (pin "2") (pinfunction "2_2") (pintype "passive"))
      (node (ref "C30") (pin "2") (pinfunction "2_2") (pintype "passive"))
      (node (ref "SIP") (pin "L20") (pinfunction "OSC0_GND_L20") (pintype "bidirectional"))
    )
    (net (code "160") (name "Net-(SIPB-OSC0_IN)") (class "Default")
      (node (ref "C30") (pin "1") (pinfunction "1_1") (pintype "passive"))
      (node (ref "R20") (pin "2") (pinfunction "2_2") (pintype "passive"))
      (node (ref "SIP") (pin "M20") (pinfunction "OSC0_IN_M20") (pintype "bidirectional"))
      (node (ref "Y1") (pin "2") (pinfunction "P$2_2") (pintype "passive"))
    )
    (net (code "161") (name "Net-(SIPB-OSC0_OUT)") (class "Default")
      (node (ref "C29") (pin "1") (pinfunction "1_1") (pintype "passive"))
      (node (ref "R20") (pin "1") (pinfunction "1_1") (pintype "passive"))
      (node (ref "SIP") (pin "K20") (pinfunction "OSC0_OUT_K20") (pintype "bidirectional"))
      (node (ref "Y1") (pin "1") (pinfunction "P$1_1") (pintype "passive"))
    )
    (net (code "162") (name "Net-(SIPB-OSC1_GND)") (class "Default")
      (node (ref "C31") (pin "2") (pinfunction "2_2") (pintype "passive"))
      (node (ref "C32") (pin "1") (pinfunction "1_1") (pintype "passive"))
      (node (ref "SIP") (pin "G20") (pinfunction "OSC1_GND_G20") (pintype "bidirectional"))
    )
    (net (code "163") (name "Net-(SIPB-OSC1_IN)") (class "Default")
      (node (ref "C31") (pin "1") (pinfunction "1_1") (pintype "passive"))
      (node (ref "R18") (pin "2") (pinfunction "2_2") (pintype "passive"))
      (node (ref "SIP") (pin "H20") (pinfunction "OSC1_IN_H20") (pintype "bidirectional"))
      (node (ref "Y2") (pin "P$2") (pinfunction "P$2_P$2") (pintype "passive"))
    )
    (net (code "164") (name "Net-(SIPB-OSC1_OUT)") (class "Default")
      (node (ref "C32") (pin "2") (pinfunction "2_2") (pintype "passive"))
      (node (ref "R18") (pin "1") (pinfunction "1_1") (pintype "passive"))
      (node (ref "SIP") (pin "F20") (pinfunction "OSC1_OUT_F20") (pintype "bidirectional"))
      (node (ref "Y2") (pin "P$1") (pinfunction "P$1_P$1") (pintype "passive"))
    )
    (net (code "165") (name "Net-(SIPC-ADC_VREFP)") (class "Default")
      (node (ref "C42") (pin "1") (pinfunction "1_1") (pintype "passive"))
      (node (ref "C43") (pin "1") (pinfunction "1_1") (pintype "passive"))
      (node (ref "R111") (pin "2") (pinfunction "2_2") (pintype "passive"))
      (node (ref "SIP") (pin "B9") (pinfunction "ADC_VREFP_B9") (pintype "bidirectional"))
    )
    (net (code "166") (name "Net-(SIPC-AIN7)") (class "Default")
      (node (ref "R109") (pin "2") (pinfunction "2_2") (pintype "passive"))
      (node (ref "R110") (pin "1") (pinfunction "1_1") (pintype "passive"))
      (node (ref "SIP") (pin "C9") (pinfunction "AIN7_C9") (pintype "bidirectional"))
    )
    (net (code "167") (name "Net-(SIPC-LCD_DATA11_U4)") (class "Default")
      (node (ref "R135") (pin "2") (pinfunction "2_2") (pintype "passive"))
      (node (ref "SIP") (pin "U4") (pinfunction "LCD_DATA11_U4_U4") (pintype "bidirectional"))
    )
    (net (code "168") (name "Net-(SIPC-USB0_VBUS)") (class "Default")
      (node (ref "R149") (pin "1") (pinfunction "1_1") (pintype "passive"))
      (node (ref "SIP") (pin "P15") (pinfunction "USB0_VBUS_P15") (pintype "bidirectional"))
    )
    (net (code "169") (name "Net-(SIPC-USB1_ID)") (class "Default")
      (node (ref "R150") (pin "1") (pinfunction "1_1") (pintype "passive"))
      (node (ref "SIP") (pin "P17") (pinfunction "USB1_ID_P17") (pintype "bidirectional"))
    )
    (net (code "170") (name "Net-(SIPC-USB1_VBUS)") (class "Default")
      (node (ref "R156") (pin "1") (pinfunction "1_1") (pintype "passive"))
      (node (ref "SIP") (pin "T18") (pinfunction "USB1_VBUS_T18") (pintype "bidirectional"))
    )
    (net (code "171") (name "Net-(SIPE-RTC_KALDO_ENN)") (class "Default")
      (node (ref "R158") (pin "1") (pinfunction "1_1") (pintype "passive"))
      (node (ref "SIP") (pin "B4") (pinfunction "RTC_KALDO_ENN_B4") (pintype "bidirectional"))
    )
    (net (code "172") (name "Net-(U5-WP)") (class "Default")
      (node (ref "R58") (pin "1") (pinfunction "1_1") (pintype "passive"))
      (node (ref "U5") (pin "5") (pinfunction "WP_5") (pintype "input"))
      (node (ref "WP") (pin "P$1") (pinfunction "TP_P$1") (pintype "bidirectional"))
    )
    (net (code "173") (name "Net-(U7-BT_AUD_CLK)") (class "Default")
      (node (ref "R124") (pin "2") (pinfunction "2_2") (pintype "passive"))
      (node (ref "U7") (pin "60") (pinfunction "BT_AUD_CLK_60") (pintype "bidirectional"))
    )
    (net (code "174") (name "Net-(U7-BT_AUD_FSYNC)") (class "Default")
      (node (ref "R123") (pin "2") (pinfunction "2_2") (pintype "passive"))
      (node (ref "U7") (pin "58") (pinfunction "BT_AUD_FSYNC_58") (pintype "bidirectional"))
    )
    (net (code "175") (name "Net-(U7-BT_AUD_IN)") (class "Default")
      (node (ref "R97") (pin "2") (pinfunction "2_2") (pintype "passive"))
      (node (ref "U7") (pin "56") (pinfunction "BT_AUD_IN_56") (pintype "bidirectional"))
    )
    (net (code "176") (name "Net-(U7-BT_AUD_OUT)") (class "Default")
      (node (ref "R100") (pin "2") (pinfunction "2_2") (pintype "passive"))
      (node (ref "U7") (pin "57") (pinfunction "BT_AUD_OUT_57") (pintype "bidirectional"))
    )
    (net (code "177") (name "Net-(U7-BT_HCI_CTS)") (class "Default")
      (node (ref "R86") (pin "2") (pinfunction "2_2") (pintype "passive"))
      (node (ref "U7") (pin "51") (pinfunction "BT_HCI_CTS_51") (pintype "bidirectional"))
    )
    (net (code "178") (name "Net-(U7-BT_HCI_RTS)") (class "Default")
      (node (ref "R85") (pin "2") (pinfunction "2_2") (pintype "passive"))
      (node (ref "U7") (pin "50") (pinfunction "BT_HCI_RTS_50") (pintype "bidirectional"))
    )
    (net (code "179") (name "Net-(U7-BT_HCI_RX)") (class "Default")
      (node (ref "R96") (pin "2") (pinfunction "2_2") (pintype "passive"))
      (node (ref "U7") (pin "53") (pinfunction "BT_HCI_RX_53") (pintype "bidirectional"))
    )
    (net (code "180") (name "Net-(U7-BT_HCI_TX)") (class "Default")
      (node (ref "R92") (pin "2") (pinfunction "2_2") (pintype "passive"))
      (node (ref "U7") (pin "52") (pinfunction "BT_HCI_TX_52") (pintype "bidirectional"))
    )
    (net (code "181") (name "Net-(U7-RF_ANT1)") (class "Default")
      (node (ref "C48") (pin "2") (pinfunction "2_2") (pintype "passive"))
      (node (ref "U7") (pin "32") (pinfunction "RF_ANT1_32") (pintype "bidirectional"))
    )
    (net (code "182") (name "Net-(U7-RF_ANT2)") (class "Default")
      (node (ref "C58") (pin "2") (pinfunction "2_2") (pintype "passive"))
      (node (ref "U7") (pin "18") (pinfunction "RF_ANT2_18") (pintype "bidirectional"))
    )
    (net (code "183") (name "Net-(U7-WLAN_IRQ)") (class "Default")
      (node (ref "R84") (pin "2") (pinfunction "2_2") (pintype "passive"))
      (node (ref "R9") (pin "2") (pinfunction "2_2") (pintype "passive"))
      (node (ref "U7") (pin "14") (pinfunction "WLAN_IRQ_14") (pintype "bidirectional"))
    )
    (net (code "184") (name "Net-(U7-WL_SDIO_CLK)") (class "Default")
      (node (ref "R78") (pin "2") (pinfunction "2_2") (pintype "passive"))
      (node (ref "U7") (pin "8") (pinfunction "WL_SDIO_CLK_8") (pintype "bidirectional"))
    )
    (net (code "185") (name "Net-(U7-WL_SDIO_CMD)") (class "Default")
      (node (ref "R79") (pin "2") (pinfunction "2_2") (pintype "passive"))
      (node (ref "U7") (pin "6") (pinfunction "WL_SDIO_CMD_6") (pintype "bidirectional"))
    )
    (net (code "186") (name "Net-(U7-WL_SDIO_D0)") (class "Default")
      (node (ref "R80") (pin "2") (pinfunction "2_2") (pintype "passive"))
      (node (ref "U7") (pin "10") (pinfunction "WL_SDIO_D0_10") (pintype "bidirectional"))
    )
    (net (code "187") (name "Net-(U7-WL_SDIO_D1)") (class "Default")
      (node (ref "R81") (pin "2") (pinfunction "2_2") (pintype "passive"))
      (node (ref "U7") (pin "11") (pinfunction "WL_SDIO_D1_11") (pintype "bidirectional"))
    )
    (net (code "188") (name "Net-(U7-WL_SDIO_D2)") (class "Default")
      (node (ref "R82") (pin "2") (pinfunction "2_2") (pintype "passive"))
      (node (ref "U7") (pin "12") (pinfunction "WL_SDIO_D2_12") (pintype "bidirectional"))
    )
    (net (code "189") (name "Net-(U7-WL_SDIO_D3)") (class "Default")
      (node (ref "R83") (pin "2") (pinfunction "2_2") (pintype "passive"))
      (node (ref "U7") (pin "13") (pinfunction "WL_SDIO_D3_13") (pintype "bidirectional"))
    )
    (net (code "190") (name "Net-(U10-OE)") (class "Default")
      (node (ref "R106") (pin "2") (pinfunction "2_2") (pintype "passive"))
      (node (ref "R93") (pin "2") (pinfunction "2_2") (pintype "passive"))
      (node (ref "U10") (pin "10") (pinfunction "OE_10") (pintype "bidirectional"))
      (node (ref "U2") (pin "1") (pinfunction "OE_1") (pintype "input"))
      (node (ref "U9") (pin "10") (pinfunction "OE_10") (pintype "bidirectional"))
    )
    (net (code "191") (name "Net-(U13-VDDI)") (class "Default")
      (node (ref "C36") (pin "1") (pinfunction "1_1") (pintype "passive"))
      (node (ref "U13") (pin "C2") (pinfunction "VDDI_C2") (pintype "bidirectional"))
    )
    (net (code "192") (name "Net-(X3-GND)") (class "Default")
      (node (ref "L4") (pin "2") (pinfunction "2_2") (pintype "passive"))
      (node (ref "X3") (pin "4") (pinfunction "GND_4") (pintype "bidirectional"))
    )
    (net (code "193") (name "Net-(X3-VBUS)") (class "Default")
      (node (ref "L5") (pin "2") (pinfunction "2_2") (pintype "passive"))
      (node (ref "X3") (pin "1") (pinfunction "VBUS_1") (pintype "bidirectional"))
    )
    (net (code "194") (name "PAUSE_BTN") (class "Default")
      (node (ref "PAU") (pin "2") (pinfunction "2_2") (pintype "passive"))
      (node (ref "SIP") (pin "T6") (pinfunction "TIMER5_T6_T6") (pintype "bidirectional"))
    )
    (net (code "195") (name "PMIC_INT") (class "Default")
      (node (ref "SIP") (pin "B18") (pinfunction "EXTINTN_B18") (pintype "bidirectional"))
      (node (ref "SIP") (pin "B19") (pinfunction "PMIC_OUT_NINT_B19") (pintype "output"))
    )
    (net (code "196") (name "PMIC_NWAKEUP") (class "Default")
      (node (ref "SIP") (pin "A19") (pinfunction "PMIC_OUT_NWAKEUP_A19") (pintype "output"))
      (node (ref "SIP") (pin "C5") (pinfunction "EXT_WAKEUP_C5") (pintype "bidirectional"))
    )
    (net (code "197") (name "PMIC_PGOOD") (class "Default")
      (node (ref "SIP") (pin "A20") (pinfunction "PMIC_OUT_PGOOD_A20") (pintype "output"))
      (node (ref "SIP") (pin "B15") (pinfunction "PWRONRSTN_B15") (pintype "bidirectional"))
      (node (ref "U6") (pin "2") (pinfunction "A_2") (pintype "input"))
    )
    (net (code "198") (name "POWER_BTN") (class "Default")
      (node (ref "POW") (pin "2") (pinfunction "2_2") (pintype "passive"))
      (node (ref "SIP") (pin "D20") (pinfunction "PMIC_IN_PB_IN_D20") (pintype "bidirectional"))
    )
    (net (code "199") (name "PRU_E_A") (class "Default")
      (node (ref "E4") (pin "3") (pinfunction "3_3") (pintype "bidirectional"))
      (node (ref "SIP") (pin "V13") (pinfunction "GPIO1_14_V13_V13") (pintype "bidirectional"))
    )
    (net (code "200") (name "PRU_E_B") (class "Default")
      (node (ref "E4") (pin "4") (pinfunction "4_4") (pintype "bidirectional"))
      (node (ref "SIP") (pin "U13") (pinfunction "GPIO1_15_U13_U13") (pintype "bidirectional"))
    )
    (net (code "201") (name "PWM_1A") (class "Default")
      (node (ref "H1") (pin "23") (pinfunction "PWMA_23") (pintype "bidirectional"))
      (node (ref "SIP") (pin "U14") (pinfunction "EHRPWM1A_U14_U14") (pintype "bidirectional"))
    )
    (net (code "202") (name "PWM_1B") (class "Default")
      (node (ref "H1") (pin "15") (pinfunction "PWMB_15") (pintype "bidirectional"))
      (node (ref "SIP") (pin "T14") (pinfunction "EHRPWM1B_T14_T14") (pintype "bidirectional"))
    )
    (net (code "203") (name "PWM_2A") (class "Default")
      (node (ref "H2") (pin "23") (pinfunction "PWMA_23") (pintype "bidirectional"))
      (node (ref "SIP") (pin "U10") (pinfunction "EHRPWM2A_U10_U10") (pintype "bidirectional"))
    )
    (net (code "204") (name "PWM_2B") (class "Default")
      (node (ref "H2") (pin "15") (pinfunction "PWMB_15") (pintype "bidirectional"))
      (node (ref "SIP") (pin "T10") (pinfunction "EHRPWM2B_T10_T10") (pintype "bidirectional"))
    )
    (net (code "205") (name "PWR_LED") (class "Default")
      (node (ref "ON") (pin "C") (pinfunction "C_C") (pintype "passive"))
      (node (ref "R24") (pin "1") (pinfunction "1_1") (pintype "passive"))
    )
    (net (code "206") (name "RESET") (class "Default")
      (node (ref "C33") (pin "1") (pinfunction "1_1") (pintype "passive"))
      (node (ref "R60") (pin "1") (pinfunction "1_1") (pintype "passive"))
      (node (ref "RST") (pin "2") (pinfunction "2_2") (pintype "passive"))
      (node (ref "SIP") (pin "A10") (pinfunction "WARMRSTN_A10") (pintype "bidirectional"))
      (node (ref "U6") (pin "4") (pinfunction "Y_4") (pintype "output"))
    )
    (net (code "207") (name "SD_BOOT") (class "Default")
      (node (ref "R77") (pin "2") (pinfunction "2_2") (pintype "passive"))
      (node (ref "SD") (pin "2") (pinfunction "2_2") (pintype "passive"))
    )
    (net (code "208") (name "SERVO_EN") (class "Default")
      (node (ref "6VREG") (pin "8") (pinfunction "EN_8") (pintype "bidirectional"))
      (node (ref "R46") (pin "2") (pinfunction "2_2") (pintype "passive"))
      (node (ref "SIP") (pin "U3") (pinfunction "LCD_DATA10_U3_U3") (pintype "bidirectional"))
    )
    (net (code "209") (name "SPI1_MISO") (class "Default")
      (node (ref "S1.1") (pin "4") (pinfunction "4_4") (pintype "bidirectional"))
      (node (ref "S1.2") (pin "4") (pinfunction "4_4") (pintype "bidirectional"))
      (node (ref "SIP") (pin "B13") (pinfunction "SPI1_D0_B13_B13") (pintype "bidirectional"))
    )
    (net (code "210") (name "SPI1_MOSI") (class "Default")
      (node (ref "S1.1") (pin "3") (pinfunction "3_3") (pintype "bidirectional"))
      (node (ref "S1.2") (pin "3") (pinfunction "3_3") (pintype "bidirectional"))
      (node (ref "SIP") (pin "D12") (pinfunction "SPI1_D1_D12_D12") (pintype "bidirectional"))
    )
    (net (code "211") (name "SPI1_SCK") (class "Default")
      (node (ref "S1.1") (pin "5") (pinfunction "5_5") (pintype "bidirectional"))
      (node (ref "S1.2") (pin "5") (pinfunction "5_5") (pintype "bidirectional"))
      (node (ref "SIP") (pin "A13") (pinfunction "SPI1_CLK_A13_A13") (pintype "bidirectional"))
    )
    (net (code "212") (name "SPI1_SS1") (class "Default")
      (node (ref "S1.1") (pin "6") (pinfunction "6_6") (pintype "bidirectional"))
      (node (ref "SIP") (pin "H18") (pinfunction "H18_H18") (pintype "bidirectional"))
    )
    (net (code "213") (name "SPI1_SS2") (class "Default")
      (node (ref "S1.2") (pin "6") (pinfunction "6_6") (pintype "bidirectional"))
      (node (ref "SIP") (pin "C18") (pinfunction "GPIO0_7_C18_C18") (pintype "bidirectional"))
    )
    (net (code "214") (name "SVO1") (class "Default")
      (node (ref "R36") (pin "1") (pinfunction "1_1") (pintype "passive"))
      (node (ref "R50") (pin "1") (pinfunction "1_1") (pintype "passive"))
      (node (ref "SIP") (pin "U5") (pinfunction "LCD_VSYNC_U5_U5") (pintype "bidirectional"))
    )
    (net (code "215") (name "SVO2") (class "Default")
      (node (ref "R37") (pin "1") (pinfunction "1_1") (pintype "passive"))
      (node (ref "R51") (pin "1") (pinfunction "1_1") (pintype "passive"))
      (node (ref "SIP") (pin "V5") (pinfunction "LCD_PCLK_V5_V5") (pintype "bidirectional"))
    )
    (net (code "216") (name "SVO3") (class "Default")
      (node (ref "R38") (pin "1") (pinfunction "1_1") (pintype "passive"))
      (node (ref "R52") (pin "1") (pinfunction "1_1") (pintype "passive"))
      (node (ref "SIP") (pin "R5") (pinfunction "LCD_HSYNC_R5_R5") (pintype "bidirectional"))
    )
    (net (code "217") (name "SVO4") (class "Default")
      (node (ref "R39") (pin "1") (pinfunction "1_1") (pintype "passive"))
      (node (ref "R53") (pin "1") (pinfunction "1_1") (pintype "passive"))
      (node (ref "SIP") (pin "R6") (pinfunction "LCD_DE_R6_R6") (pintype "bidirectional"))
    )
    (net (code "218") (name "SVO5") (class "Default")
      (node (ref "R125") (pin "2") (pinfunction "2_2") (pintype "passive"))
      (node (ref "R40") (pin "1") (pinfunction "1_1") (pintype "passive"))
      (node (ref "SIP") (pin "T3") (pinfunction "LCD_DATA6_T3_T3") (pintype "bidirectional"))
    )
    (net (code "219") (name "SVO6") (class "Default")
      (node (ref "R127") (pin "2") (pinfunction "2_2") (pintype "passive"))
      (node (ref "R41") (pin "1") (pinfunction "1_1") (pintype "passive"))
      (node (ref "SIP") (pin "T4") (pinfunction "LCD_DATA7_T4_T4") (pintype "bidirectional"))
    )
    (net (code "220") (name "SVO7") (class "Default")
      (node (ref "R120") (pin "1") (pinfunction "1_1") (pintype "passive"))
      (node (ref "R42") (pin "1") (pinfunction "1_1") (pintype "passive"))
      (node (ref "SIP") (pin "T1") (pinfunction "LCD_DATA4_T1_T1") (pintype "bidirectional"))
    )
    (net (code "221") (name "SVO8") (class "Default")
      (node (ref "R122") (pin "1") (pinfunction "1_1") (pintype "passive"))
      (node (ref "R43") (pin "1") (pinfunction "1_1") (pintype "passive"))
      (node (ref "SIP") (pin "T2") (pinfunction "LCD_DATA5_T2_T2") (pintype "bidirectional"))
    )
    (net (code "222") (name "SYS_5V") (class "Default")
      (node (ref "C62") (pin "1") (pinfunction "1_1") (pintype "passive"))
      (node (ref "R121") (pin "2") (pinfunction "2_2") (pintype "passive"))
      (node (ref "SIP") (pin "W4") (pinfunction "VOUT_SYS_5V_0_W4") (pintype "power_in"))
      (node (ref "SIP") (pin "Y4") (pinfunction "VOUT_SYS_5V_1_Y4") (pintype "power_in"))
      (node (ref "TP1") (pin "TP") (pinfunction "TP_TP") (pintype "input"))
      (node (ref "U1") (pin "3") (pinfunction "VCC_3") (pintype "power_in"))
      (node (ref "U8") (pin "3") (pinfunction "IN2_3") (pintype "input"))
    )
    (net (code "223") (name "UART0_RX") (class "Default")
      (node (ref "SIP") (pin "E15") (pinfunction "UART0_RXD_E15_E15") (pintype "bidirectional"))
      (node (ref "UT0") (pin "3") (pinfunction "3_3") (pintype "bidirectional"))
    )
    (net (code "224") (name "UART0_TX") (class "Default")
      (node (ref "SIP") (pin "E16") (pinfunction "UART0_TXD_E16_E16") (pintype "bidirectional"))
      (node (ref "UT0") (pin "4") (pinfunction "4_4") (pintype "bidirectional"))
    )
    (net (code "225") (name "UART1_RX") (class "Default")
      (node (ref "SIP") (pin "D16") (pinfunction "UART1_RXD_D16_D16") (pintype "bidirectional"))
      (node (ref "UT1") (pin "3") (pinfunction "3_3") (pintype "bidirectional"))
    )
    (net (code "226") (name "UART1_TX") (class "Default")
      (node (ref "SIP") (pin "D15") (pinfunction "UART1_TXD_D15_D15") (pintype "bidirectional"))
      (node (ref "UT1") (pin "4") (pinfunction "4_4") (pintype "bidirectional"))
    )
    (net (code "227") (name "UART2_RX") (class "Default")
      (node (ref "GPS") (pin "3") (pinfunction "3_3") (pintype "bidirectional"))
      (node (ref "SIP") (pin "A17") (pinfunction "UART2_RXD_A17_A17") (pintype "bidirectional"))
    )
    (net (code "228") (name "UART2_TX") (class "Default")
      (node (ref "GPS") (pin "4") (pinfunction "4_4") (pintype "bidirectional"))
      (node (ref "SIP") (pin "B17") (pinfunction "UART2_TXD_B17_B17") (pintype "bidirectional"))
    )
    (net (code "229") (name "UART3_CTSN") (class "Default")
      (node (ref "R89") (pin "1") (pinfunction "1_1") (pintype "passive"))
      (node (ref "SIP") (pin "M17") (pinfunction "M17_M17") (pintype "bidirectional"))
      (node (ref "U10") (pin "12") (pinfunction "B8_12") (pintype "bidirectional"))
    )
    (net (code "230") (name "UART3_RTSN") (class "Default")
      (node (ref "R108") (pin "1") (pinfunction "1_1") (pintype "passive"))
      (node (ref "SIP") (pin "M18") (pinfunction "M18_M18") (pintype "bidirectional"))
      (node (ref "U10") (pin "13") (pinfunction "B7_13") (pintype "bidirectional"))
    )
    (net (code "231") (name "UART3_RX") (class "Default")
      (node (ref "SIP") (pin "L17") (pinfunction "L17_L17") (pintype "bidirectional"))
      (node (ref "U10") (pin "14") (pinfunction "B6_14") (pintype "bidirectional"))
    )
    (net (code "232") (name "UART3_TX") (class "Default")
      (node (ref "SIP") (pin "L16") (pinfunction "L16_L16") (pintype "bidirectional"))
      (node (ref "U10") (pin "15") (pinfunction "B5_15") (pintype "bidirectional"))
    )
    (net (code "233") (name "UART4_RX") (class "Default")
      (node (ref "DSM2") (pin "P$3") (pinfunction "3_P$3") (pintype "bidirectional"))
      (node (ref "SIP") (pin "T17") (pinfunction "UART4_RXD_T17_T17") (pintype "bidirectional"))
    )
    (net (code "234") (name "UART5_RX") (class "Default")
      (node (ref "R131") (pin "2") (pinfunction "2_2") (pintype "passive"))
      (node (ref "SIP") (pin "U2") (pinfunction "LCD_DATA9_U2_U2") (pintype "bidirectional"))
      (node (ref "UT5") (pin "3") (pinfunction "3_3") (pintype "bidirectional"))
    )
    (net (code "235") (name "UART5_TX") (class "Default")
      (node (ref "R129") (pin "2") (pinfunction "2_2") (pintype "passive"))
      (node (ref "SIP") (pin "U1") (pinfunction "LCD_DATA8_U1_U1") (pintype "bidirectional"))
      (node (ref "UT5") (pin "4") (pinfunction "4_4") (pintype "bidirectional"))
    )
    (net (code "236") (name "USB0_D_N") (class "Default")
      (node (ref "SIP") (pin "N18") (pinfunction "USB0_DM_N18") (pintype "bidirectional"))
      (node (ref "U3") (pin "2") (pinfunction "D-_2") (pintype "bidirectional"))
      (node (ref "X4") (pin "D-") (pinfunction "D-_D-") (pintype "input"))
    )
    (net (code "237") (name "USB0_D_P") (class "Default")
      (node (ref "SIP") (pin "N17") (pinfunction "USB0_DP_N17") (pintype "bidirectional"))
      (node (ref "U3") (pin "1") (pinfunction "D+_1") (pintype "bidirectional"))
      (node (ref "X4") (pin "D+") (pinfunction "D+_D+") (pintype "input"))
    )
    (net (code "238") (name "USB0_ID") (class "Default")
      (node (ref "SIP") (pin "P16") (pinfunction "USB0_ID_P16") (pintype "bidirectional"))
      (node (ref "U3") (pin "3") (pinfunction "ID_3") (pintype "bidirectional"))
      (node (ref "X4") (pin "ID") (pinfunction "ID_ID") (pintype "input"))
    )
    (net (code "239") (name "USB0_VBUS") (class "Default")
      (node (ref "C54") (pin "1") (pinfunction "1_1") (pintype "passive"))
      (node (ref "R112") (pin "2") (pinfunction "2_2") (pintype "passive"))
      (node (ref "R149") (pin "2") (pinfunction "2_2") (pintype "passive"))
      (node (ref "U3") (pin "6") (pinfunction "VBUS_6") (pintype "bidirectional"))
      (node (ref "X4") (pin "VBUS") (pinfunction "VBUS_VBUS") (pintype "input"))
    )
    (net (code "240") (name "USB1_D_N") (class "Default")
      (node (ref "SIP") (pin "R18") (pinfunction "USB1_DM_R18") (pintype "bidirectional"))
      (node (ref "U4") (pin "2") (pinfunction "D-_2") (pintype "bidirectional"))
      (node (ref "X3") (pin "2") (pinfunction "D-_2") (pintype "bidirectional"))
    )
    (net (code "241") (name "USB1_D_P") (class "Default")
      (node (ref "SIP") (pin "R17") (pinfunction "USB1_DP_R17") (pintype "bidirectional"))
      (node (ref "U4") (pin "1") (pinfunction "D+_1") (pintype "bidirectional"))
      (node (ref "X3") (pin "3") (pinfunction "D+_3") (pintype "bidirectional"))
    )
    (net (code "242") (name "USB1_VBUS") (class "Default")
      (node (ref "C45") (pin "1") (pinfunction "1_1") (pintype "passive"))
      (node (ref "C46") (pin "1") (pinfunction "1_1") (pintype "passive"))
      (node (ref "C55") (pin "1") (pinfunction "1_1") (pintype "passive"))
      (node (ref "C61") (pin "2") (pinfunction "2_2") (pintype "passive"))
      (node (ref "L5") (pin "1") (pinfunction "1_1") (pintype "passive"))
      (node (ref "R119") (pin "1") (pinfunction "1_1") (pintype "passive"))
      (node (ref "R121") (pin "1") (pinfunction "1_1") (pintype "passive"))
      (node (ref "R156") (pin "2") (pinfunction "2_2") (pintype "passive"))
      (node (ref "U4") (pin "6") (pinfunction "VBUS_6") (pintype "bidirectional"))
      (node (ref "U8") (pin "4") (pinfunction "OUT_4") (pintype "output"))
    )
    (net (code "243") (name "USB_DC") (class "Default")
      (node (ref "R112") (pin "1") (pinfunction "1_1") (pintype "passive"))
      (node (ref "SIP") (pin "Y8") (pinfunction "VIN_USB_0_Y8") (pintype "power_in"))
      (node (ref "SIP") (pin "Y9") (pinfunction "VIN_USB_1_Y9") (pintype "power_in"))
    )
    (net (code "244") (name "USR_LED0") (class "Default")
      (node (ref "0") (pin "A") (pinfunction "A_A") (pintype "passive"))
      (node (ref "SIP") (pin "V15") (pinfunction "USR0_V15_V15") (pintype "bidirectional"))
    )
    (net (code "245") (name "USR_LED1") (class "Default")
      (node (ref "1") (pin "A") (pinfunction "A_A") (pintype "passive"))
      (node (ref "SIP") (pin "U15") (pinfunction "USR1_U15_U15") (pintype "bidirectional"))
    )
    (net (code "246") (name "USR_LED2") (class "Default")
      (node (ref "2") (pin "A") (pinfunction "A_A") (pintype "passive"))
      (node (ref "SIP") (pin "T15") (pinfunction "USR2_T15_T15") (pintype "bidirectional"))
    )
    (net (code "247") (name "USR_LED3") (class "Default")
      (node (ref "3") (pin "A") (pinfunction "A_A") (pintype "passive"))
      (node (ref "SIP") (pin "V16") (pinfunction "USR3_V16_V16") (pintype "bidirectional"))
    )
    (net (code "248") (name "VCC") (class "Default")
      (node (ref "12V") (pin "IN") (pinfunction "IN_IN") (pintype "bidirectional"))
      (node (ref "C12") (pin "1") (pinfunction "1_1") (pintype "passive"))
      (node (ref "C7") (pin "1") (pinfunction "1_1") (pintype "passive"))
      (node (ref "CHG") (pin "A") (pinfunction "A_A") (pintype "passive"))
      (node (ref "CHGIC") (pin "2") (pinfunction "VIN_2") (pintype "bidirectional"))
      (node (ref "D3") (pin "A") (pinfunction "A_A") (pintype "passive"))
      (node (ref "R1") (pin "1") (pinfunction "1_1") (pintype "passive"))
    )
    (net (code "249") (name "VCC_CHG") (class "Default")
      (node (ref "C4") (pin "2") (pinfunction "2_2") (pintype "passive"))
      (node (ref "CHGIC") (pin "3") (pinfunction "VCC_3") (pintype "bidirectional"))
      (node (ref "R5") (pin "2") (pinfunction "2_2") (pintype "passive"))
    )
    (net (code "250") (name "VDD_1V8") (class "Default")
      (node (ref "C47") (pin "1") (pinfunction "1_1") (pintype "passive"))
      (node (ref "C50") (pin "1") (pinfunction "1_1") (pintype "passive"))
      (node (ref "C52") (pin "1") (pinfunction "1_1") (pintype "passive"))
      (node (ref "C57") (pin "2") (pinfunction "2_2") (pintype "passive"))
      (node (ref "C60") (pin "2") (pinfunction "2_2") (pintype "passive"))
      (node (ref "OSC1") (pin "4") (pinfunction "VCC_4") (pintype "bidirectional"))
      (node (ref "R101") (pin "1") (pinfunction "1_1") (pintype "passive"))
      (node (ref "R102") (pin "1") (pinfunction "1_1") (pintype "passive"))
      (node (ref "R103") (pin "1") (pinfunction "1_1") (pintype "passive"))
      (node (ref "R105") (pin "1") (pinfunction "1_1") (pintype "passive"))
      (node (ref "R9") (pin "1") (pinfunction "1_1") (pintype "passive"))
      (node (ref "R90") (pin "2") (pinfunction "2_2") (pintype "passive"))
      (node (ref "R98") (pin "1") (pinfunction "1_1") (pintype "passive"))
      (node (ref "R99") (pin "1") (pinfunction "1_1") (pintype "passive"))
      (node (ref "SIP") (pin "D10") (pinfunction "VDD_1V84_D10") (pintype "bidirectional"))
      (node (ref "SIP") (pin "E9") (pinfunction "VDD_1V83_E9") (pintype "bidirectional"))
      (node (ref "SIP") (pin "N16") (pinfunction "VOUT_LDO3_1P8V_0_N16") (pintype "power_in"))
      (node (ref "SIP") (pin "R16") (pinfunction "VOUT_LDO3_1P8V_1_R16") (pintype "power_in"))
      (node (ref "U10") (pin "2") (pinfunction "VCCA_2") (pintype "bidirectional"))
      (node (ref "U2") (pin "5") (pinfunction "VCC_5") (pintype "power_in"))
      (node (ref "U7") (pin "38") (pinfunction "VIO_38") (pintype "bidirectional"))
      (node (ref "U9") (pin "2") (pinfunction "VCCA_2") (pintype "bidirectional"))
    )
    (net (code "251") (name "VDD_3V3AUX") (class "Default")
      (node (ref "ON") (pin "A") (pinfunction "A_A") (pintype "passive"))
      (node (ref "SIP") (pin "Y11") (pinfunction "VOUT_LDO2_3P3V_Y11") (pintype "power_in"))
    )
    (net (code "252") (name "VDD_ADC") (class "Default")
      (node (ref "ADC") (pin "2") (pinfunction "2_2") (pintype "bidirectional"))
      (node (ref "C44") (pin "1") (pinfunction "1_1") (pintype "passive"))
      (node (ref "R111") (pin "1") (pinfunction "1_1") (pintype "passive"))
      (node (ref "SIP") (pin "A4") (pinfunction "VOUT_ADC_1P8V_0_A4") (pintype "bidirectional"))
      (node (ref "SIP") (pin "A5") (pinfunction "VOUT_ADC_1P8V_1_A5") (pintype "bidirectional"))
      (node (ref "SIP") (pin "D8") (pinfunction "VDDA_ADC_D8") (pintype "bidirectional"))
    )
    (net (code "253") (name "VDD_RTC") (class "Default")
      (node (ref "SIP") (pin "E14") (pinfunction "VDD_RTC3_E14") (pintype "bidirectional"))
      (node (ref "U6") (pin "5") (pinfunction "VCC_5") (pintype "power_in"))
    )
    (net (code "254") (name "VIN_BAT_0") (class "Default")
      (node (ref "SIP") (pin "Y2") (pinfunction "VIN_BAT_0_Y2") (pintype "power_in"))
    )
    (net (code "255") (name "VIN_BAT_1") (class "Default")
      (node (ref "SIP") (pin "Y3") (pinfunction "VIN_BAT_1_Y3") (pintype "power_in"))
    )
    (net (code "256") (name "V_BATT") (class "Default")
      (node (ref "6VREG") (pin "9") (pinfunction "VIN_9") (pintype "bidirectional"))
      (node (ref "C11") (pin "+") (pinfunction "+_+") (pintype "passive"))
      (node (ref "C20") (pin "2") (pinfunction "2_2") (pintype "passive"))
      (node (ref "C25") (pin "1") (pinfunction "1_1") (pintype "passive"))
      (node (ref "C26") (pin "1") (pinfunction "1_1") (pintype "passive"))
      (node (ref "CHGIC") (pin "9") (pinfunction "BATT_9") (pintype "bidirectional"))
      (node (ref "D2") (pin "A") (pinfunction "A_A") (pintype "passive"))
      (node (ref "H1") (pin "13") (pinfunction "VM2_13") (pintype "bidirectional"))
      (node (ref "H1") (pin "14") (pinfunction "VM3_14") (pintype "bidirectional"))
      (node (ref "H1") (pin "24") (pinfunction "VM1_24") (pintype "bidirectional"))
      (node (ref "H2") (pin "13") (pinfunction "VM2_13") (pintype "bidirectional"))
      (node (ref "H2") (pin "14") (pinfunction "VM3_14") (pintype "bidirectional"))
      (node (ref "H2") (pin "24") (pinfunction "VM1_24") (pintype "bidirectional"))
      (node (ref "LIPO") (pin "P$1") (pinfunction "1_P$1") (pintype "passive"))
      (node (ref "R19") (pin "1") (pinfunction "1_1") (pintype "passive"))
      (node (ref "R28") (pin "1") (pinfunction "1_1") (pintype "passive"))
      (node (ref "R34") (pin "1") (pinfunction "1_1") (pintype "passive"))
      (node (ref "R4") (pin "1") (pinfunction "1_1") (pintype "passive"))
    )
    (net (code "257") (name "V_DIV_BAT") (class "Default")
      (node (ref "R19") (pin "2") (pinfunction "2_2") (pintype "passive"))
      (node (ref "R25") (pin "1") (pinfunction "1_1") (pintype "passive"))
      (node (ref "SIP") (pin "A8") (pinfunction "AIN6_A8") (pintype "bidirectional"))
    )
    (net (code "258") (name "V_DIV_DC") (class "Default")
      (node (ref "R1") (pin "2") (pinfunction "2_2") (pintype "passive"))
      (node (ref "R14") (pin "1") (pinfunction "1_1") (pintype "passive"))
      (node (ref "SIP") (pin "B8") (pinfunction "AIN5_B8") (pintype "bidirectional"))
    )
    (net (code "259") (name "WIFI_LED") (class "Default")
      (node (ref "SIP") (pin "A15") (pinfunction "GPIO0_19_A15_A15") (pintype "bidirectional"))
      (node (ref "WIFI") (pin "A") (pinfunction "A_A") (pintype "passive"))
    )
    (net (code "260") (name "WLAN_IRQ") (class "Default")
      (node (ref "SIP") (pin "K16") (pinfunction "K16_K16") (pintype "bidirectional"))
      (node (ref "U2") (pin "4") (pinfunction "Y_4") (pintype "output"))
    )
    (net (code "261") (name "WL_BT_OE") (class "Default")
      (node (ref "R93") (pin "1") (pinfunction "1_1") (pintype "passive"))
      (node (ref "SIP") (pin "L18") (pinfunction "L18_L18") (pintype "bidirectional"))
    )
    (net (code "262") (name "WL_EN") (class "Default")
      (node (ref "SIP") (pin "K18") (pinfunction "K18_K18") (pintype "bidirectional"))
      (node (ref "U9") (pin "20") (pinfunction "B1_20") (pintype "bidirectional"))
    )
    (net (code "263") (name "WL_EN_1V8") (class "Default")
      (node (ref "R87") (pin "1") (pinfunction "1_1") (pintype "passive"))
      (node (ref "U7") (pin "40") (pinfunction "WLAN_EN_40") (pintype "bidirectional"))
      (node (ref "U9") (pin "1") (pinfunction "A1_1") (pintype "bidirectional"))
    )
    (net (code "264") (name "WL_IRQ") (class "Default")
      (node (ref "R84") (pin "1") (pinfunction "1_1") (pintype "passive"))
      (node (ref "U2") (pin "2") (pinfunction "A_2") (pintype "input"))
    )
    (net (code "265") (name "WL_SDIO_CLK") (class "Default")
      (node (ref "R103") (pin "2") (pinfunction "2_2") (pintype "passive"))
      (node (ref "R78") (pin "1") (pinfunction "1_1") (pintype "passive"))
      (node (ref "U9") (pin "8") (pinfunction "A7_8") (pintype "bidirectional"))
    )
    (net (code "266") (name "WL_SDIO_CMD") (class "Default")
      (node (ref "R105") (pin "2") (pinfunction "2_2") (pintype "passive"))
      (node (ref "R79") (pin "1") (pinfunction "1_1") (pintype "passive"))
      (node (ref "U9") (pin "9") (pinfunction "A8_9") (pintype "bidirectional"))
    )
    (net (code "267") (name "WL_SDIO_D0") (class "Default")
      (node (ref "R80") (pin "1") (pinfunction "1_1") (pintype "passive"))
      (node (ref "R98") (pin "2") (pinfunction "2_2") (pintype "passive"))
      (node (ref "U9") (pin "7") (pinfunction "A6_7") (pintype "bidirectional"))
    )
    (net (code "268") (name "WL_SDIO_D1") (class "Default")
      (node (ref "R81") (pin "1") (pinfunction "1_1") (pintype "passive"))
      (node (ref "R99") (pin "2") (pinfunction "2_2") (pintype "passive"))
      (node (ref "U9") (pin "6") (pinfunction "A5_6") (pintype "bidirectional"))
    )
    (net (code "269") (name "WL_SDIO_D2") (class "Default")
      (node (ref "R101") (pin "2") (pinfunction "2_2") (pintype "passive"))
      (node (ref "R82") (pin "1") (pinfunction "1_1") (pintype "passive"))
      (node (ref "U9") (pin "5") (pinfunction "A4_5") (pintype "bidirectional"))
    )
    (net (code "270") (name "WL_SDIO_D3") (class "Default")
      (node (ref "R102") (pin "2") (pinfunction "2_2") (pintype "passive"))
      (node (ref "R83") (pin "1") (pinfunction "1_1") (pintype "passive"))
      (node (ref "U9") (pin "4") (pinfunction "A3_4") (pintype "bidirectional"))
    )
    (net (code "271") (name "unconnected-(12V-PadOUT_CON)") (class "Default")
      (node (ref "12V") (pin "OUT_CON") (pinfunction "OUT_CON_OUT_CON") (pintype "bidirectional"))
    )
    (net (code "272") (name "unconnected-(CHGIC-ACOK-Pad12)") (class "Default")
      (node (ref "CHGIC") (pin "12") (pinfunction "ACOK_12") (pintype "bidirectional"))
    )
    (net (code "273") (name "unconnected-(CHGIC-CELL-Pad4)") (class "Default")
      (node (ref "CHGIC") (pin "4") (pinfunction "CELL_4") (pintype "bidirectional"))
    )
    (net (code "274") (name "unconnected-(CHGIC-SEL-Pad5)") (class "Default")
      (node (ref "CHGIC") (pin "5") (pinfunction "SEL_5") (pintype "bidirectional"))
    )
    (net (code "275") (name "unconnected-(FUD1-PadP$1)") (class "Default")
      (node (ref "FUD1") (pin "P$1") (pinfunction "P$1_P$1") (pintype "no_connect"))
    )
    (net (code "276") (name "unconnected-(FUD2-PadP$1)") (class "Default")
      (node (ref "FUD2") (pin "P$1") (pinfunction "P$1_P$1") (pintype "no_connect"))
    )
    (net (code "277") (name "unconnected-(FUD3-PadP$1)") (class "Default")
      (node (ref "FUD3") (pin "P$1") (pinfunction "P$1_P$1") (pintype "no_connect"))
    )
    (net (code "278") (name "unconnected-(FUD4-PadP$1)") (class "Default")
      (node (ref "FUD4") (pin "P$1") (pinfunction "P$1_P$1") (pintype "no_connect"))
    )
    (net (code "279") (name "unconnected-(FUD5-PadP$1)") (class "Default")
      (node (ref "FUD5") (pin "P$1") (pinfunction "P$1_P$1") (pintype "no_connect"))
    )
    (net (code "280") (name "unconnected-(FUD6-PadP$1)") (class "Default")
      (node (ref "FUD6") (pin "P$1") (pinfunction "P$1_P$1") (pintype "no_connect"))
    )
    (net (code "281") (name "unconnected-(GPS-Pad1)") (class "Default")
      (node (ref "GPS") (pin "1") (pinfunction "1_1") (pintype "bidirectional"))
    )
    (net (code "282") (name "unconnected-(IMU-AUX_CL-Pad7)") (class "Default")
      (node (ref "IMU") (pin "7") (pinfunction "AUX_CL_7") (pintype "bidirectional"))
    )
    (net (code "283") (name "unconnected-(IMU-AUX_DA-Pad21)") (class "Default")
      (node (ref "IMU") (pin "21") (pinfunction "AUX_DA_21") (pintype "bidirectional"))
    )
    (net (code "284") (name "unconnected-(IMU-FSYNC-Pad11)") (class "Default")
      (node (ref "IMU") (pin "11") (pinfunction "FSYNC_11") (pintype "bidirectional"))
    )
    (net (code "285") (name "unconnected-(IMU-NC-Pad2)") (class "Default")
      (node (ref "IMU") (pin "2") (pinfunction "NC_2") (pintype "bidirectional"))
    )
    (net (code "286") (name "unconnected-(IMU-NC-Pad3)") (class "Default")
      (node (ref "IMU") (pin "3") (pinfunction "NC_3") (pintype "bidirectional"))
    )
    (net (code "287") (name "unconnected-(IMU-NC-Pad4)") (class "Default")
      (node (ref "IMU") (pin "4") (pinfunction "NC_4") (pintype "bidirectional"))
    )
    (net (code "288") (name "unconnected-(IMU-NC-Pad5)") (class "Default")
      (node (ref "IMU") (pin "5") (pinfunction "NC_5") (pintype "bidirectional"))
    )
    (net (code "289") (name "unconnected-(IMU-NC-Pad6)") (class "Default")
      (node (ref "IMU") (pin "6") (pinfunction "NC_6") (pintype "bidirectional"))
    )
    (net (code "290") (name "unconnected-(IMU-NC-Pad14)") (class "Default")
      (node (ref "IMU") (pin "14") (pinfunction "NC_14") (pintype "bidirectional"))
    )
    (net (code "291") (name "unconnected-(IMU-NC-Pad15)") (class "Default")
      (node (ref "IMU") (pin "15") (pinfunction "NC_15") (pintype "bidirectional"))
    )
    (net (code "292") (name "unconnected-(IMU-NC-Pad16)") (class "Default")
      (node (ref "IMU") (pin "16") (pinfunction "NC_16") (pintype "bidirectional"))
    )
    (net (code "293") (name "unconnected-(IMU-NC-Pad17)") (class "Default")
      (node (ref "IMU") (pin "17") (pinfunction "NC_17") (pintype "bidirectional"))
    )
    (net (code "294") (name "unconnected-(IMU-RESV-Pad19)") (class "Default")
      (node (ref "IMU") (pin "19") (pinfunction "RESV_19") (pintype "bidirectional"))
    )
    (net (code "295") (name "unconnected-(PROT-CO-Pad3)") (class "Default")
      (node (ref "PROT") (pin "3") (pinfunction "CO_3") (pintype "bidirectional"))
    )
    (net (code "296") (name "unconnected-(PROT-DP-Pad4)") (class "Default")
      (node (ref "PROT") (pin "4") (pinfunction "DP_4") (pintype "bidirectional"))
    )
    (net (code "297") (name "unconnected-(SIPA-BAT_TEMP-PadW1)") (class "Default")
      (node (ref "SIP") (pin "W1") (pinfunction "BAT_TEMP_W1") (pintype "bidirectional"))
    )
    (net (code "298") (name "unconnected-(SIPA-BAT_VOLT-PadY1)") (class "Default")
      (node (ref "SIP") (pin "Y1") (pinfunction "BAT_VOLT_Y1") (pintype "bidirectional"))
    )
    (net (code "299") (name "unconnected-(SIPA-L1_IN-PadY14)") (class "Default")
      (node (ref "SIP") (pin "Y14") (pinfunction "L1_IN_Y14") (pintype "bidirectional"))
    )
    (net (code "300") (name "unconnected-(SIPA-L1_OUT-PadY13)") (class "Default")
      (node (ref "SIP") (pin "Y13") (pinfunction "L1_OUT_Y13") (pintype "bidirectional"))
    )
    (net (code "301") (name "unconnected-(SIPA-L2_IN-PadY17)") (class "Default")
      (node (ref "SIP") (pin "Y17") (pinfunction "L2_IN_Y17") (pintype "bidirectional"))
    )
    (net (code "302") (name "unconnected-(SIPA-L2_OUT-PadY16)") (class "Default")
      (node (ref "SIP") (pin "Y16") (pinfunction "L2_OUT_Y16") (pintype "bidirectional"))
    )
    (net (code "303") (name "unconnected-(SIPA-L3_IN-PadY20)") (class "Default")
      (node (ref "SIP") (pin "Y20") (pinfunction "L3_IN_Y20") (pintype "bidirectional"))
    )
    (net (code "304") (name "unconnected-(SIPA-L3_OUT-PadY19)") (class "Default")
      (node (ref "SIP") (pin "Y19") (pinfunction "L3_OUT_Y19") (pintype "bidirectional"))
    )
    (net (code "305") (name "unconnected-(SIPC-AIN4-PadC8)") (class "Default")
      (node (ref "SIP") (pin "C8") (pinfunction "AIN4_C8") (pintype "bidirectional"))
    )
    (net (code "306") (name "unconnected-(SIPC-USB0_CE-PadM15)") (class "Default")
      (node (ref "SIP") (pin "M15") (pinfunction "USB0_CE_M15") (pintype "bidirectional"))
    )
    (net (code "307") (name "unconnected-(SIPC-USB0_DRVVBUS-PadF16)") (class "Default")
      (node (ref "SIP") (pin "F16") (pinfunction "USB0_DRVVBUS_F16") (pintype "bidirectional"))
    )
    (net (code "308") (name "unconnected-(SIPC-USB1_CE-PadP18)") (class "Default")
      (node (ref "SIP") (pin "P18") (pinfunction "USB1_CE_P18") (pintype "bidirectional"))
    )
    (net (code "309") (name "unconnected-(SIPC-USB1_DRVVBUS-PadF15)") (class "Default")
      (node (ref "SIP") (pin "F15") (pinfunction "USB1_DRVVBUS_F15") (pintype "bidirectional"))
    )
    (net (code "310") (name "unconnected-(SIPD-NC1-PadV11)") (class "Default")
      (node (ref "SIP") (pin "V11") (pinfunction "NC1_V11") (pintype "bidirectional"))
    )
    (net (code "311") (name "unconnected-(SIPD-NC2-PadU11)") (class "Default")
      (node (ref "SIP") (pin "U11") (pinfunction "NC2_U11") (pintype "bidirectional"))
    )
    (net (code "312") (name "unconnected-(SIPD-NC3-PadV10)") (class "Default")
      (node (ref "SIP") (pin "V10") (pinfunction "NC3_V10") (pintype "bidirectional"))
    )
    (net (code "313") (name "unconnected-(SIPD-NC4-PadB1)") (class "Default")
      (node (ref "SIP") (pin "B1") (pinfunction "NC4_B1") (pintype "bidirectional"))
    )
    (net (code "314") (name "unconnected-(SIPD-NC5-PadB2)") (class "Default")
      (node (ref "SIP") (pin "B2") (pinfunction "NC5_B2") (pintype "bidirectional"))
    )
    (net (code "315") (name "unconnected-(SIPD-NC6-PadB3)") (class "Default")
      (node (ref "SIP") (pin "B3") (pinfunction "NC6_B3") (pintype "bidirectional"))
    )
    (net (code "316") (name "unconnected-(SIPD-NC12-PadC1)") (class "Default")
      (node (ref "SIP") (pin "C1") (pinfunction "NC12_C1") (pintype "bidirectional"))
    )
    (net (code "317") (name "unconnected-(SIPD-NC20-PadC2)") (class "Default")
      (node (ref "SIP") (pin "C2") (pinfunction "NC20_C2") (pintype "bidirectional"))
    )
    (net (code "318") (name "unconnected-(SIPD-NC21-PadC3)") (class "Default")
      (node (ref "SIP") (pin "C3") (pinfunction "NC21_C3") (pintype "bidirectional"))
    )
    (net (code "319") (name "unconnected-(SIPD-NC22-PadC4)") (class "Default")
      (node (ref "SIP") (pin "C4") (pinfunction "NC22_C4") (pintype "bidirectional"))
    )
    (net (code "320") (name "unconnected-(SIPD-NC23-PadP2)") (class "Default")
      (node (ref "SIP") (pin "P2") (pinfunction "NC23_P2") (pintype "bidirectional"))
    )
    (net (code "321") (name "unconnected-(SIPD-NC24-PadD1)") (class "Default")
      (node (ref "SIP") (pin "D1") (pinfunction "NC24_D1") (pintype "bidirectional"))
    )
    (net (code "322") (name "unconnected-(SIPD-NC31-PadD2)") (class "Default")
      (node (ref "SIP") (pin "D2") (pinfunction "NC31_D2") (pintype "bidirectional"))
    )
    (net (code "323") (name "unconnected-(SIPD-NC32-PadD3)") (class "Default")
      (node (ref "SIP") (pin "D3") (pinfunction "NC32_D3") (pintype "bidirectional"))
    )
    (net (code "324") (name "unconnected-(SIPD-NC33-PadD4)") (class "Default")
      (node (ref "SIP") (pin "D4") (pinfunction "NC33_D4") (pintype "bidirectional"))
    )
    (net (code "325") (name "unconnected-(SIPD-NC34-PadD5)") (class "Default")
      (node (ref "SIP") (pin "D5") (pinfunction "NC34_D5") (pintype "bidirectional"))
    )
    (net (code "326") (name "unconnected-(SIPD-NC45-PadP3)") (class "Default")
      (node (ref "SIP") (pin "P3") (pinfunction "NC45_P3") (pintype "bidirectional"))
    )
    (net (code "327") (name "unconnected-(SIPD-NC46-PadE1)") (class "Default")
      (node (ref "SIP") (pin "E1") (pinfunction "NC46_E1") (pintype "bidirectional"))
    )
    (net (code "328") (name "unconnected-(SIPD-NC47-PadE2)") (class "Default")
      (node (ref "SIP") (pin "E2") (pinfunction "NC47_E2") (pintype "bidirectional"))
    )
    (net (code "329") (name "unconnected-(SIPD-NC48-PadE3)") (class "Default")
      (node (ref "SIP") (pin "E3") (pinfunction "NC48_E3") (pintype "bidirectional"))
    )
    (net (code "330") (name "unconnected-(SIPD-NC58-PadE4)") (class "Default")
      (node (ref "SIP") (pin "E4") (pinfunction "NC58_E4") (pintype "bidirectional"))
    )
    (net (code "331") (name "unconnected-(SIPD-NC59-PadF1)") (class "Default")
      (node (ref "SIP") (pin "F1") (pinfunction "NC59_F1") (pintype "bidirectional"))
    )
    (net (code "332") (name "unconnected-(SIPD-NC60-PadF2)") (class "Default")
      (node (ref "SIP") (pin "F2") (pinfunction "NC60_F2") (pintype "bidirectional"))
    )
    (net (code "333") (name "unconnected-(SIPD-NC61-PadF3)") (class "Default")
      (node (ref "SIP") (pin "F3") (pinfunction "NC61_F3") (pintype "bidirectional"))
    )
    (net (code "334") (name "unconnected-(SIPD-NC68-PadF4)") (class "Default")
      (node (ref "SIP") (pin "F4") (pinfunction "NC68_F4") (pintype "bidirectional"))
    )
    (net (code "335") (name "unconnected-(SIPD-NC69-PadG1)") (class "Default")
      (node (ref "SIP") (pin "G1") (pinfunction "NC69_G1") (pintype "bidirectional"))
    )
    (net (code "336") (name "unconnected-(SIPD-NC70-PadG2)") (class "Default")
      (node (ref "SIP") (pin "G2") (pinfunction "NC70_G2") (pintype "bidirectional"))
    )
    (net (code "337") (name "unconnected-(SIPD-NC71-PadG3)") (class "Default")
      (node (ref "SIP") (pin "G3") (pinfunction "NC71_G3") (pintype "bidirectional"))
    )
    (net (code "338") (name "unconnected-(SIPD-NC76-PadG4)") (class "Default")
      (node (ref "SIP") (pin "G4") (pinfunction "NC76_G4") (pintype "bidirectional"))
    )
    (net (code "339") (name "unconnected-(SIPD-NC77-PadH1)") (class "Default")
      (node (ref "SIP") (pin "H1") (pinfunction "NC77_H1") (pintype "bidirectional"))
    )
    (net (code "340") (name "unconnected-(SIPD-NC78-PadH2)") (class "Default")
      (node (ref "SIP") (pin "H2") (pinfunction "NC78_H2") (pintype "bidirectional"))
    )
    (net (code "341") (name "unconnected-(SIPD-NC79-PadH3)") (class "Default")
      (node (ref "SIP") (pin "H3") (pinfunction "NC79_H3") (pintype "bidirectional"))
    )
    (net (code "342") (name "unconnected-(SIPD-NC84-PadH4)") (class "Default")
      (node (ref "SIP") (pin "H4") (pinfunction "NC84_H4") (pintype "bidirectional"))
    )
    (net (code "343") (name "unconnected-(SIPD-NC85-PadJ1)") (class "Default")
      (node (ref "SIP") (pin "J1") (pinfunction "NC85_J1") (pintype "bidirectional"))
    )
    (net (code "344") (name "unconnected-(SIPD-NC86-PadJ2)") (class "Default")
      (node (ref "SIP") (pin "J2") (pinfunction "NC86_J2") (pintype "bidirectional"))
    )
    (net (code "345") (name "unconnected-(SIPD-NC87-PadJ3)") (class "Default")
      (node (ref "SIP") (pin "J3") (pinfunction "NC87_J3") (pintype "bidirectional"))
    )
    (net (code "346") (name "unconnected-(SIPD-NC94-PadJ4)") (class "Default")
      (node (ref "SIP") (pin "J4") (pinfunction "NC94_J4") (pintype "bidirectional"))
    )
    (net (code "347") (name "unconnected-(SIPD-NC95-PadK1)") (class "Default")
      (node (ref "SIP") (pin "K1") (pinfunction "NC95_K1") (pintype "bidirectional"))
    )
    (net (code "348") (name "unconnected-(SIPD-NC96-PadK2)") (class "Default")
      (node (ref "SIP") (pin "K2") (pinfunction "NC96_K2") (pintype "bidirectional"))
    )
    (net (code "349") (name "unconnected-(SIPD-NC97-PadK3)") (class "Default")
      (node (ref "SIP") (pin "K3") (pinfunction "NC97_K3") (pintype "bidirectional"))
    )
    (net (code "350") (name "unconnected-(SIPD-NC104-PadK4)") (class "Default")
      (node (ref "SIP") (pin "K4") (pinfunction "NC104_K4") (pintype "bidirectional"))
    )
    (net (code "351") (name "unconnected-(SIPD-NC105-PadL1)") (class "Default")
      (node (ref "SIP") (pin "L1") (pinfunction "NC105_L1") (pintype "bidirectional"))
    )
    (net (code "352") (name "unconnected-(SIPD-NC106-PadL2)") (class "Default")
      (node (ref "SIP") (pin "L2") (pinfunction "NC106_L2") (pintype "bidirectional"))
    )
    (net (code "353") (name "unconnected-(SIPD-NC107-PadL3)") (class "Default")
      (node (ref "SIP") (pin "L3") (pinfunction "NC107_L3") (pintype "bidirectional"))
    )
    (net (code "354") (name "unconnected-(SIPD-NC111-PadL4)") (class "Default")
      (node (ref "SIP") (pin "L4") (pinfunction "NC111_L4") (pintype "bidirectional"))
    )
    (net (code "355") (name "unconnected-(SIPD-NC112-PadM1)") (class "Default")
      (node (ref "SIP") (pin "M1") (pinfunction "NC112_M1") (pintype "bidirectional"))
    )
    (net (code "356") (name "unconnected-(SIPD-NC113-PadM2)") (class "Default")
      (node (ref "SIP") (pin "M2") (pinfunction "NC113_M2") (pintype "bidirectional"))
    )
    (net (code "357") (name "unconnected-(SIPD-NC114-PadM3)") (class "Default")
      (node (ref "SIP") (pin "M3") (pinfunction "NC114_M3") (pintype "bidirectional"))
    )
    (net (code "358") (name "unconnected-(SIPD-NC121-PadM4)") (class "Default")
      (node (ref "SIP") (pin "M4") (pinfunction "NC121_M4") (pintype "bidirectional"))
    )
    (net (code "359") (name "unconnected-(SIPD-NC122-PadP4)") (class "Default")
      (node (ref "SIP") (pin "P4") (pinfunction "NC122_P4") (pintype "bidirectional"))
    )
    (net (code "360") (name "unconnected-(SIPD-NC123-PadN1)") (class "Default")
      (node (ref "SIP") (pin "N1") (pinfunction "NC123_N1") (pintype "bidirectional"))
    )
    (net (code "361") (name "unconnected-(SIPD-NC124-PadN2)") (class "Default")
      (node (ref "SIP") (pin "N2") (pinfunction "NC124_N2") (pintype "bidirectional"))
    )
    (net (code "362") (name "unconnected-(SIPD-NC136-PadN3)") (class "Default")
      (node (ref "SIP") (pin "N3") (pinfunction "NC136_N3") (pintype "bidirectional"))
    )
    (net (code "363") (name "unconnected-(SIPD-NC137-PadN4)") (class "Default")
      (node (ref "SIP") (pin "N4") (pinfunction "NC137_N4") (pintype "bidirectional"))
    )
    (net (code "364") (name "unconnected-(SIPD-NC138-PadP1)") (class "Default")
      (node (ref "SIP") (pin "P1") (pinfunction "NC138_P1") (pintype "bidirectional"))
    )
    (net (code "365") (name "unconnected-(SIPE-CAP_VBB_MPU-PadC10)") (class "Default")
      (node (ref "SIP") (pin "C10") (pinfunction "CAP_VBB_MPU_C10") (pintype "bidirectional"))
    )
    (net (code "366") (name "unconnected-(SIPE-CAP_VDD_RTC-PadD6)") (class "Default")
      (node (ref "SIP") (pin "D6") (pinfunction "CAP_VDD_RTC_D6") (pintype "bidirectional"))
    )
    (net (code "367") (name "unconnected-(SIPE-CAP_VDD_SRAM_COR-PadD9)") (class "Default")
      (node (ref "SIP") (pin "D9") (pinfunction "CAP_VDD_SRAM_COR_D9") (pintype "bidirectional"))
    )
    (net (code "368") (name "unconnected-(SIPE-CAP_VDD_SRAM_MPU-PadD11)") (class "Default")
      (node (ref "SIP") (pin "D11") (pinfunction "CAP_VDD_SRAM_MPU_D11") (pintype "bidirectional"))
    )
    (net (code "369") (name "unconnected-(SIPE-TESTOUT-PadA3)") (class "Default")
      (node (ref "SIP") (pin "A3") (pinfunction "TESTOUT_A3") (pintype "bidirectional"))
    )
    (net (code "370") (name "unconnected-(SIPE-VDDS_DDR1-PadE5)") (class "Default")
      (node (ref "SIP") (pin "E5") (pinfunction "VDDS_DDR1_E5") (pintype "bidirectional"))
    )
    (net (code "371") (name "unconnected-(SIPE-VDDS_DDR2-PadF5)") (class "Default")
      (node (ref "SIP") (pin "F5") (pinfunction "VDDS_DDR2_F5") (pintype "bidirectional"))
    )
    (net (code "372") (name "unconnected-(SIPE-VDDS_DDR3-PadG5)") (class "Default")
      (node (ref "SIP") (pin "G5") (pinfunction "VDDS_DDR3_G5") (pintype "bidirectional"))
    )
    (net (code "373") (name "unconnected-(SIPE-VDDS_DDR4-PadH5)") (class "Default")
      (node (ref "SIP") (pin "H5") (pinfunction "VDDS_DDR4_H5") (pintype "bidirectional"))
    )
    (net (code "374") (name "unconnected-(SIPE-VDDS_DDR5-PadJ5)") (class "Default")
      (node (ref "SIP") (pin "J5") (pinfunction "VDDS_DDR5_J5") (pintype "bidirectional"))
    )
    (net (code "375") (name "unconnected-(SIPE-VDDS_DDR6-PadK5)") (class "Default")
      (node (ref "SIP") (pin "K5") (pinfunction "VDDS_DDR6_K5") (pintype "bidirectional"))
    )
    (net (code "376") (name "unconnected-(SIPE-VDDS_DDR7-PadL5)") (class "Default")
      (node (ref "SIP") (pin "L5") (pinfunction "VDDS_DDR7_L5") (pintype "bidirectional"))
    )
    (net (code "377") (name "unconnected-(SIPE-VDD_3V3A1-PadE10)") (class "Default")
      (node (ref "SIP") (pin "E10") (pinfunction "VDD_3V3A1_E10") (pintype "bidirectional"))
    )
    (net (code "378") (name "unconnected-(SIPE-VDD_3V3A2-PadE11)") (class "Default")
      (node (ref "SIP") (pin "E11") (pinfunction "VDD_3V3A2_E11") (pintype "bidirectional"))
    )
    (net (code "379") (name "unconnected-(SIPE-VDD_3V3A3-PadE12)") (class "Default")
      (node (ref "SIP") (pin "E12") (pinfunction "VDD_3V3A3_E12") (pintype "bidirectional"))
    )
    (net (code "380") (name "unconnected-(SIPE-VDD_3V3A4-PadE13)") (class "Default")
      (node (ref "SIP") (pin "E13") (pinfunction "VDD_3V3A4_E13") (pintype "bidirectional"))
    )
    (net (code "381") (name "unconnected-(SIPE-VDD_3V3A5-PadF14)") (class "Default")
      (node (ref "SIP") (pin "F14") (pinfunction "VDD_3V3A5_F14") (pintype "bidirectional"))
    )
    (net (code "382") (name "unconnected-(SIPE-VDD_3V3A6-PadG14)") (class "Default")
      (node (ref "SIP") (pin "G14") (pinfunction "VDD_3V3A6_G14") (pintype "bidirectional"))
    )
    (net (code "383") (name "unconnected-(SIPE-VDD_3V3A7-PadH14)") (class "Default")
      (node (ref "SIP") (pin "H14") (pinfunction "VDD_3V3A7_H14") (pintype "bidirectional"))
    )
    (net (code "384") (name "unconnected-(SIPE-VDD_3V3A8-PadJ14)") (class "Default")
      (node (ref "SIP") (pin "J14") (pinfunction "VDD_3V3A8_J14") (pintype "bidirectional"))
    )
    (net (code "385") (name "unconnected-(SIPE-VDD_3V3A9-PadK14)") (class "Default")
      (node (ref "SIP") (pin "K14") (pinfunction "VDD_3V3A9_K14") (pintype "bidirectional"))
    )
    (net (code "386") (name "unconnected-(SIPE-VDD_3V3A10-PadL14)") (class "Default")
      (node (ref "SIP") (pin "L14") (pinfunction "VDD_3V3A10_L14") (pintype "bidirectional"))
    )
    (net (code "387") (name "unconnected-(SIPE-VDD_3V3A11-PadN5)") (class "Default")
      (node (ref "SIP") (pin "N5") (pinfunction "VDD_3V3A11_N5") (pintype "bidirectional"))
    )
    (net (code "388") (name "unconnected-(SIPE-VDD_3V3A12-PadN15)") (class "Default")
      (node (ref "SIP") (pin "N15") (pinfunction "VDD_3V3A12_N15") (pintype "bidirectional"))
    )
    (net (code "389") (name "unconnected-(SIPE-VDD_3V3A13-PadP5)") (class "Default")
      (node (ref "SIP") (pin "P5") (pinfunction "VDD_3V3A13_P5") (pintype "bidirectional"))
    )
    (net (code "390") (name "unconnected-(SIPE-VDD_3V3A14-PadP6)") (class "Default")
      (node (ref "SIP") (pin "P6") (pinfunction "VDD_3V3A14_P6") (pintype "bidirectional"))
    )
    (net (code "391") (name "unconnected-(SIPE-VDD_3V3A15-PadP7)") (class "Default")
      (node (ref "SIP") (pin "P7") (pinfunction "VDD_3V3A15_P7") (pintype "bidirectional"))
    )
    (net (code "392") (name "unconnected-(SIPE-VDD_3V3A16-PadP8)") (class "Default")
      (node (ref "SIP") (pin "P8") (pinfunction "VDD_3V3A16_P8") (pintype "bidirectional"))
    )
    (net (code "393") (name "unconnected-(SIPE-VDD_3V3A17-PadP10)") (class "Default")
      (node (ref "SIP") (pin "P10") (pinfunction "VDD_3V3A17_P10") (pintype "bidirectional"))
    )
    (net (code "394") (name "unconnected-(SIPE-VDD_3V3A18-PadP11)") (class "Default")
      (node (ref "SIP") (pin "P11") (pinfunction "VDD_3V3A18_P11") (pintype "bidirectional"))
    )
    (net (code "395") (name "unconnected-(SIPE-VDD_3V3A19-PadP12)") (class "Default")
      (node (ref "SIP") (pin "P12") (pinfunction "VDD_3V3A19_P12") (pintype "bidirectional"))
    )
    (net (code "396") (name "unconnected-(SIPE-VDD_3V3A20-PadP13)") (class "Default")
      (node (ref "SIP") (pin "P13") (pinfunction "VDD_3V3A20_P13") (pintype "bidirectional"))
    )
    (net (code "397") (name "unconnected-(SIPE-VDD_3V3A21-PadR15)") (class "Default")
      (node (ref "SIP") (pin "R15") (pinfunction "VDD_3V3A21_R15") (pintype "bidirectional"))
    )
    (net (code "398") (name "unconnected-(SIPE-VDD_CORE1-PadF6)") (class "Default")
      (node (ref "SIP") (pin "F6") (pinfunction "VDD_CORE1_F6") (pintype "bidirectional"))
    )
    (net (code "399") (name "unconnected-(SIPE-VDD_CORE2-PadF7)") (class "Default")
      (node (ref "SIP") (pin "F7") (pinfunction "VDD_CORE2_F7") (pintype "bidirectional"))
    )
    (net (code "400") (name "unconnected-(SIPE-VDD_CORE3-PadG6)") (class "Default")
      (node (ref "SIP") (pin "G6") (pinfunction "VDD_CORE3_G6") (pintype "bidirectional"))
    )
    (net (code "401") (name "unconnected-(SIPE-VDD_CORE4-PadG7)") (class "Default")
      (node (ref "SIP") (pin "G7") (pinfunction "VDD_CORE4_G7") (pintype "bidirectional"))
    )
    (net (code "402") (name "unconnected-(SIPE-VDD_CORE5-PadG10)") (class "Default")
      (node (ref "SIP") (pin "G10") (pinfunction "VDD_CORE5_G10") (pintype "bidirectional"))
    )
    (net (code "403") (name "unconnected-(SIPE-VDD_CORE6-PadH11)") (class "Default")
      (node (ref "SIP") (pin "H11") (pinfunction "VDD_CORE6_H11") (pintype "bidirectional"))
    )
    (net (code "404") (name "unconnected-(SIPE-VDD_CORE7-PadJ12)") (class "Default")
      (node (ref "SIP") (pin "J12") (pinfunction "VDD_CORE7_J12") (pintype "bidirectional"))
    )
    (net (code "405") (name "unconnected-(SIPE-VDD_CORE8-PadK6)") (class "Default")
      (node (ref "SIP") (pin "K6") (pinfunction "VDD_CORE8_K6") (pintype "bidirectional"))
    )
    (net (code "406") (name "unconnected-(SIPE-VDD_CORE9-PadK8)") (class "Default")
      (node (ref "SIP") (pin "K8") (pinfunction "VDD_CORE9_K8") (pintype "bidirectional"))
    )
    (net (code "407") (name "unconnected-(SIPE-VDD_CORE10-PadK12)") (class "Default")
      (node (ref "SIP") (pin "K12") (pinfunction "VDD_CORE10_K12") (pintype "bidirectional"))
    )
    (net (code "408") (name "unconnected-(SIPE-VDD_CORE11-PadL6)") (class "Default")
      (node (ref "SIP") (pin "L6") (pinfunction "VDD_CORE11_L6") (pintype "bidirectional"))
    )
    (net (code "409") (name "unconnected-(SIPE-VDD_CORE12-PadL7)") (class "Default")
      (node (ref "SIP") (pin "L7") (pinfunction "VDD_CORE12_L7") (pintype "bidirectional"))
    )
    (net (code "410") (name "unconnected-(SIPE-VDD_CORE13-PadL8)") (class "Default")
      (node (ref "SIP") (pin "L8") (pinfunction "VDD_CORE13_L8") (pintype "bidirectional"))
    )
    (net (code "411") (name "unconnected-(SIPE-VDD_CORE14-PadL9)") (class "Default")
      (node (ref "SIP") (pin "L9") (pinfunction "VDD_CORE14_L9") (pintype "bidirectional"))
    )
    (net (code "412") (name "unconnected-(SIPE-VDD_CORE15-PadM11)") (class "Default")
      (node (ref "SIP") (pin "M11") (pinfunction "VDD_CORE15_M11") (pintype "bidirectional"))
    )
    (net (code "413") (name "unconnected-(SIPE-VDD_CORE16-PadM13)") (class "Default")
      (node (ref "SIP") (pin "M13") (pinfunction "VDD_CORE16_M13") (pintype "bidirectional"))
    )
    (net (code "414") (name "unconnected-(SIPE-VDD_CORE17-PadN8)") (class "Default")
      (node (ref "SIP") (pin "N8") (pinfunction "VDD_CORE17_N8") (pintype "bidirectional"))
    )
    (net (code "415") (name "unconnected-(SIPE-VDD_CORE18-PadN9)") (class "Default")
      (node (ref "SIP") (pin "N9") (pinfunction "VDD_CORE18_N9") (pintype "bidirectional"))
    )
    (net (code "416") (name "unconnected-(SIPE-VDD_CORE19-PadN12)") (class "Default")
      (node (ref "SIP") (pin "N12") (pinfunction "VDD_CORE19_N12") (pintype "bidirectional"))
    )
    (net (code "417") (name "unconnected-(SIPE-VDD_CORE20-PadN13)") (class "Default")
      (node (ref "SIP") (pin "N13") (pinfunction "VDD_CORE20_N13") (pintype "bidirectional"))
    )
    (net (code "418") (name "unconnected-(SIPE-VDD_MPU0-PadF10)") (class "Default")
      (node (ref "SIP") (pin "F10") (pinfunction "VDD_MPU0_F10") (pintype "bidirectional"))
    )
    (net (code "419") (name "unconnected-(SIPE-VDD_MPU1-PadF11)") (class "Default")
      (node (ref "SIP") (pin "F11") (pinfunction "VDD_MPU1_F11") (pintype "bidirectional"))
    )
    (net (code "420") (name "unconnected-(SIPE-VDD_MPU2-PadF12)") (class "Default")
      (node (ref "SIP") (pin "F12") (pinfunction "VDD_MPU2_F12") (pintype "bidirectional"))
    )
    (net (code "421") (name "unconnected-(SIPE-VDD_MPU3-PadF13)") (class "Default")
      (node (ref "SIP") (pin "F13") (pinfunction "VDD_MPU3_F13") (pintype "bidirectional"))
    )
    (net (code "422") (name "unconnected-(SIPE-VDD_MPU4-PadG13)") (class "Default")
      (node (ref "SIP") (pin "G13") (pinfunction "VDD_MPU4_G13") (pintype "bidirectional"))
    )
    (net (code "423") (name "unconnected-(SIPE-VDD_MPU5-PadH13)") (class "Default")
      (node (ref "SIP") (pin "H13") (pinfunction "VDD_MPU5_H13") (pintype "bidirectional"))
    )
    (net (code "424") (name "unconnected-(SIPE-VDD_MPU6-PadJ13)") (class "Default")
      (node (ref "SIP") (pin "J13") (pinfunction "VDD_MPU6_J13") (pintype "bidirectional"))
    )
    (net (code "425") (name "unconnected-(SIPE-VDD_MPU_MON-PadA2)") (class "Default")
      (node (ref "SIP") (pin "A2") (pinfunction "VDD_MPU_MON_A2") (pintype "bidirectional"))
    )
    (net (code "426") (name "unconnected-(SIPE-VDD_PLL1-PadE7)") (class "Default")
      (node (ref "SIP") (pin "E7") (pinfunction "VDD_PLL1_E7") (pintype "bidirectional"))
    )
    (net (code "427") (name "unconnected-(SIPE-VDD_PLL2-PadH15)") (class "Default")
      (node (ref "SIP") (pin "H15") (pinfunction "VDD_PLL2_H15") (pintype "bidirectional"))
    )
    (net (code "428") (name "unconnected-(SIPE-VDD_PLL3-PadR10)") (class "Default")
      (node (ref "SIP") (pin "R10") (pinfunction "VDD_PLL3_R10") (pintype "bidirectional"))
    )
    (net (code "429") (name "unconnected-(SIPE-VDD_PLL4-PadR11)") (class "Default")
      (node (ref "SIP") (pin "R11") (pinfunction "VDD_PLL4_R11") (pintype "bidirectional"))
    )
    (net (code "430") (name "unconnected-(SIPE-VDD_RTC1-PadD7)") (class "Default")
      (node (ref "SIP") (pin "D7") (pinfunction "VDD_RTC1_D7") (pintype "bidirectional"))
    )
    (net (code "431") (name "unconnected-(SIPE-VDD_RTC2-PadE6)") (class "Default")
      (node (ref "SIP") (pin "E6") (pinfunction "VDD_RTC2_E6") (pintype "bidirectional"))
    )
    (net (code "432") (name "unconnected-(SIPE-VDD_RTC4-PadF9)") (class "Default")
      (node (ref "SIP") (pin "F9") (pinfunction "VDD_RTC4_F9") (pintype "bidirectional"))
    )
    (net (code "433") (name "unconnected-(SIPE-VDD_RTC5-PadK13)") (class "Default")
      (node (ref "SIP") (pin "K13") (pinfunction "VDD_RTC5_K13") (pintype "bidirectional"))
    )
    (net (code "434") (name "unconnected-(SIPE-VDD_RTC6-PadN6)") (class "Default")
      (node (ref "SIP") (pin "N6") (pinfunction "VDD_RTC6_N6") (pintype "bidirectional"))
    )
    (net (code "435") (name "unconnected-(SIPE-VDD_RTC7-PadP9)") (class "Default")
      (node (ref "SIP") (pin "P9") (pinfunction "VDD_RTC7_P9") (pintype "bidirectional"))
    )
    (net (code "436") (name "unconnected-(SIPE-VDD_RTC8-PadP14)") (class "Default")
      (node (ref "SIP") (pin "P14") (pinfunction "VDD_RTC8_P14") (pintype "bidirectional"))
    )
    (net (code "437") (name "unconnected-(SIPE-VPP-PadM5)") (class "Default")
      (node (ref "SIP") (pin "M5") (pinfunction "VPP_M5") (pintype "bidirectional"))
    )
    (net (code "438") (name "unconnected-(U3-NC-Pad5)") (class "Default")
      (node (ref "U3") (pin "5") (pinfunction "NC_5") (pintype "bidirectional"))
    )
    (net (code "439") (name "unconnected-(U4-ID-Pad3)") (class "Default")
      (node (ref "U4") (pin "3") (pinfunction "ID_3") (pintype "bidirectional"))
    )
    (net (code "440") (name "unconnected-(U4-NC-Pad5)") (class "Default")
      (node (ref "U4") (pin "5") (pinfunction "NC_5") (pintype "bidirectional"))
    )
    (net (code "441") (name "unconnected-(U6-NC-Pad1)") (class "Default")
      (node (ref "U6") (pin "1") (pinfunction "NC_1") (pintype "passive"))
    )
    (net (code "442") (name "unconnected-(U7-BT_UART_DBG-Pad43)") (class "Default")
      (node (ref "U7") (pin "43") (pinfunction "BT_UART_DBG_43") (pintype "bidirectional"))
    )
    (net (code "443") (name "unconnected-(U7-GPIO1-Pad27)") (class "Default")
      (node (ref "U7") (pin "27") (pinfunction "GPIO1_27") (pintype "bidirectional"))
    )
    (net (code "444") (name "unconnected-(U7-GPIO2-Pad26)") (class "Default")
      (node (ref "U7") (pin "26") (pinfunction "GPIO2_26") (pintype "bidirectional"))
    )
    (net (code "445") (name "unconnected-(U7-GPIO4-Pad25)") (class "Default")
      (node (ref "U7") (pin "25") (pinfunction "GPIO4_25") (pintype "bidirectional"))
    )
    (net (code "446") (name "unconnected-(U7-GPIO9-Pad3)") (class "Default")
      (node (ref "U7") (pin "3") (pinfunction "GPIO9_3") (pintype "bidirectional"))
    )
    (net (code "447") (name "unconnected-(U7-GPIO10-Pad4)") (class "Default")
      (node (ref "U7") (pin "4") (pinfunction "GPIO10_4") (pintype "bidirectional"))
    )
    (net (code "448") (name "unconnected-(U7-GPIO11-Pad2)") (class "Default")
      (node (ref "U7") (pin "2") (pinfunction "GPIO11_2") (pintype "bidirectional"))
    )
    (net (code "449") (name "unconnected-(U7-GPIO12-Pad5)") (class "Default")
      (node (ref "U7") (pin "5") (pinfunction "GPIO12_5") (pintype "bidirectional"))
    )
    (net (code "450") (name "unconnected-(U7-RESERVED1-Pad21)") (class "Default")
      (node (ref "U7") (pin "21") (pinfunction "RESERVED1_21") (pintype "bidirectional"))
    )
    (net (code "451") (name "unconnected-(U7-RESERVED2-Pad22)") (class "Default")
      (node (ref "U7") (pin "22") (pinfunction "RESERVED2_22") (pintype "bidirectional"))
    )
    (net (code "452") (name "unconnected-(U7-RESERVED3-Pad62)") (class "Default")
      (node (ref "U7") (pin "62") (pinfunction "RESERVED3_62") (pintype "bidirectional"))
    )
    (net (code "453") (name "unconnected-(U7-WL_UART_DBG-Pad42)") (class "Default")
      (node (ref "U7") (pin "42") (pinfunction "WL_UART_DBG_42") (pintype "bidirectional"))
    )
  )
)
